# backplane.net
KiCad netlist of a schematic drawn in EAGLE
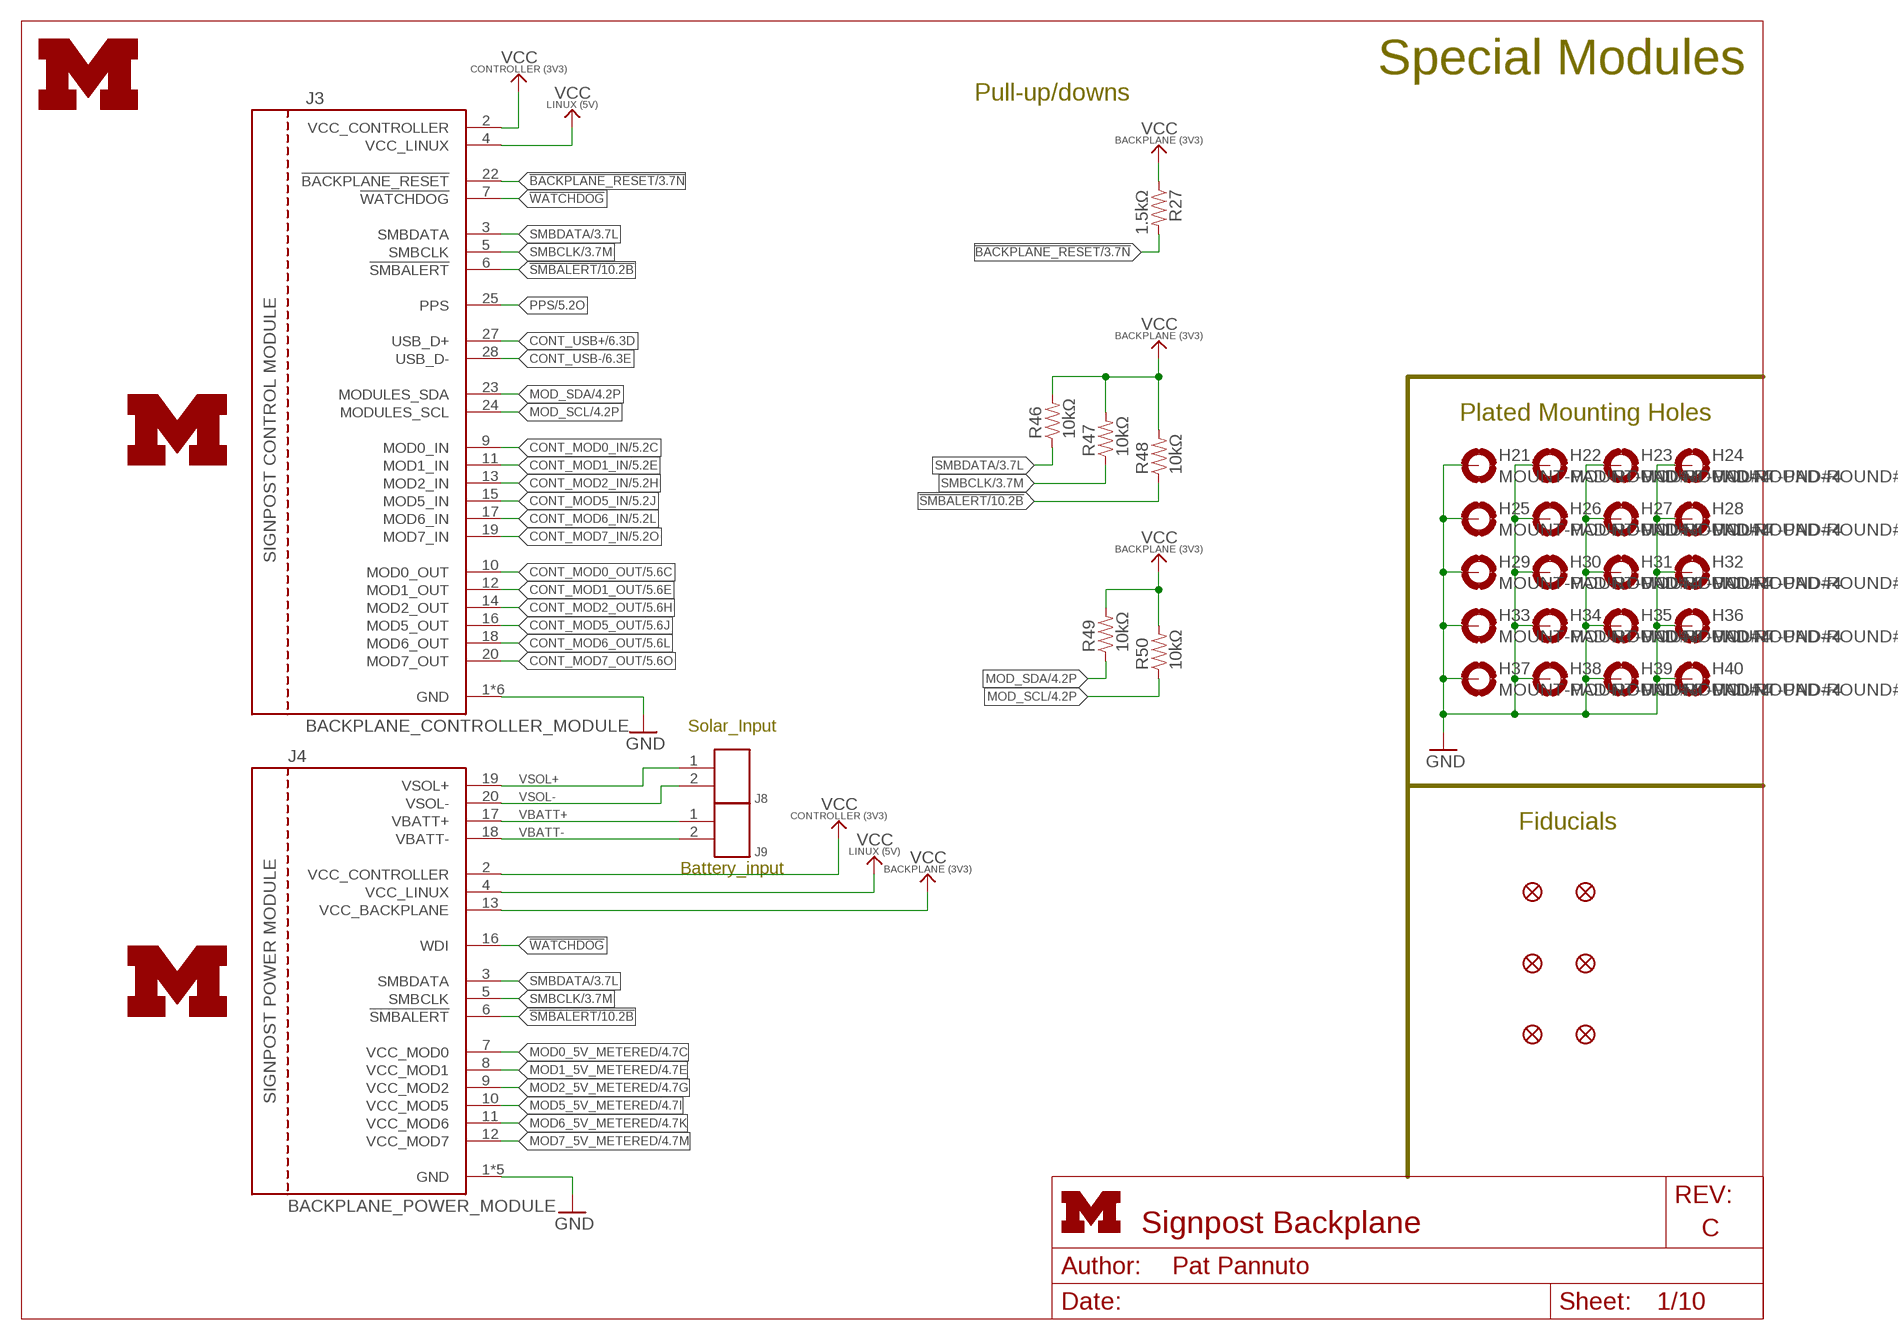
[diagram p0: schematic, sheet 1]
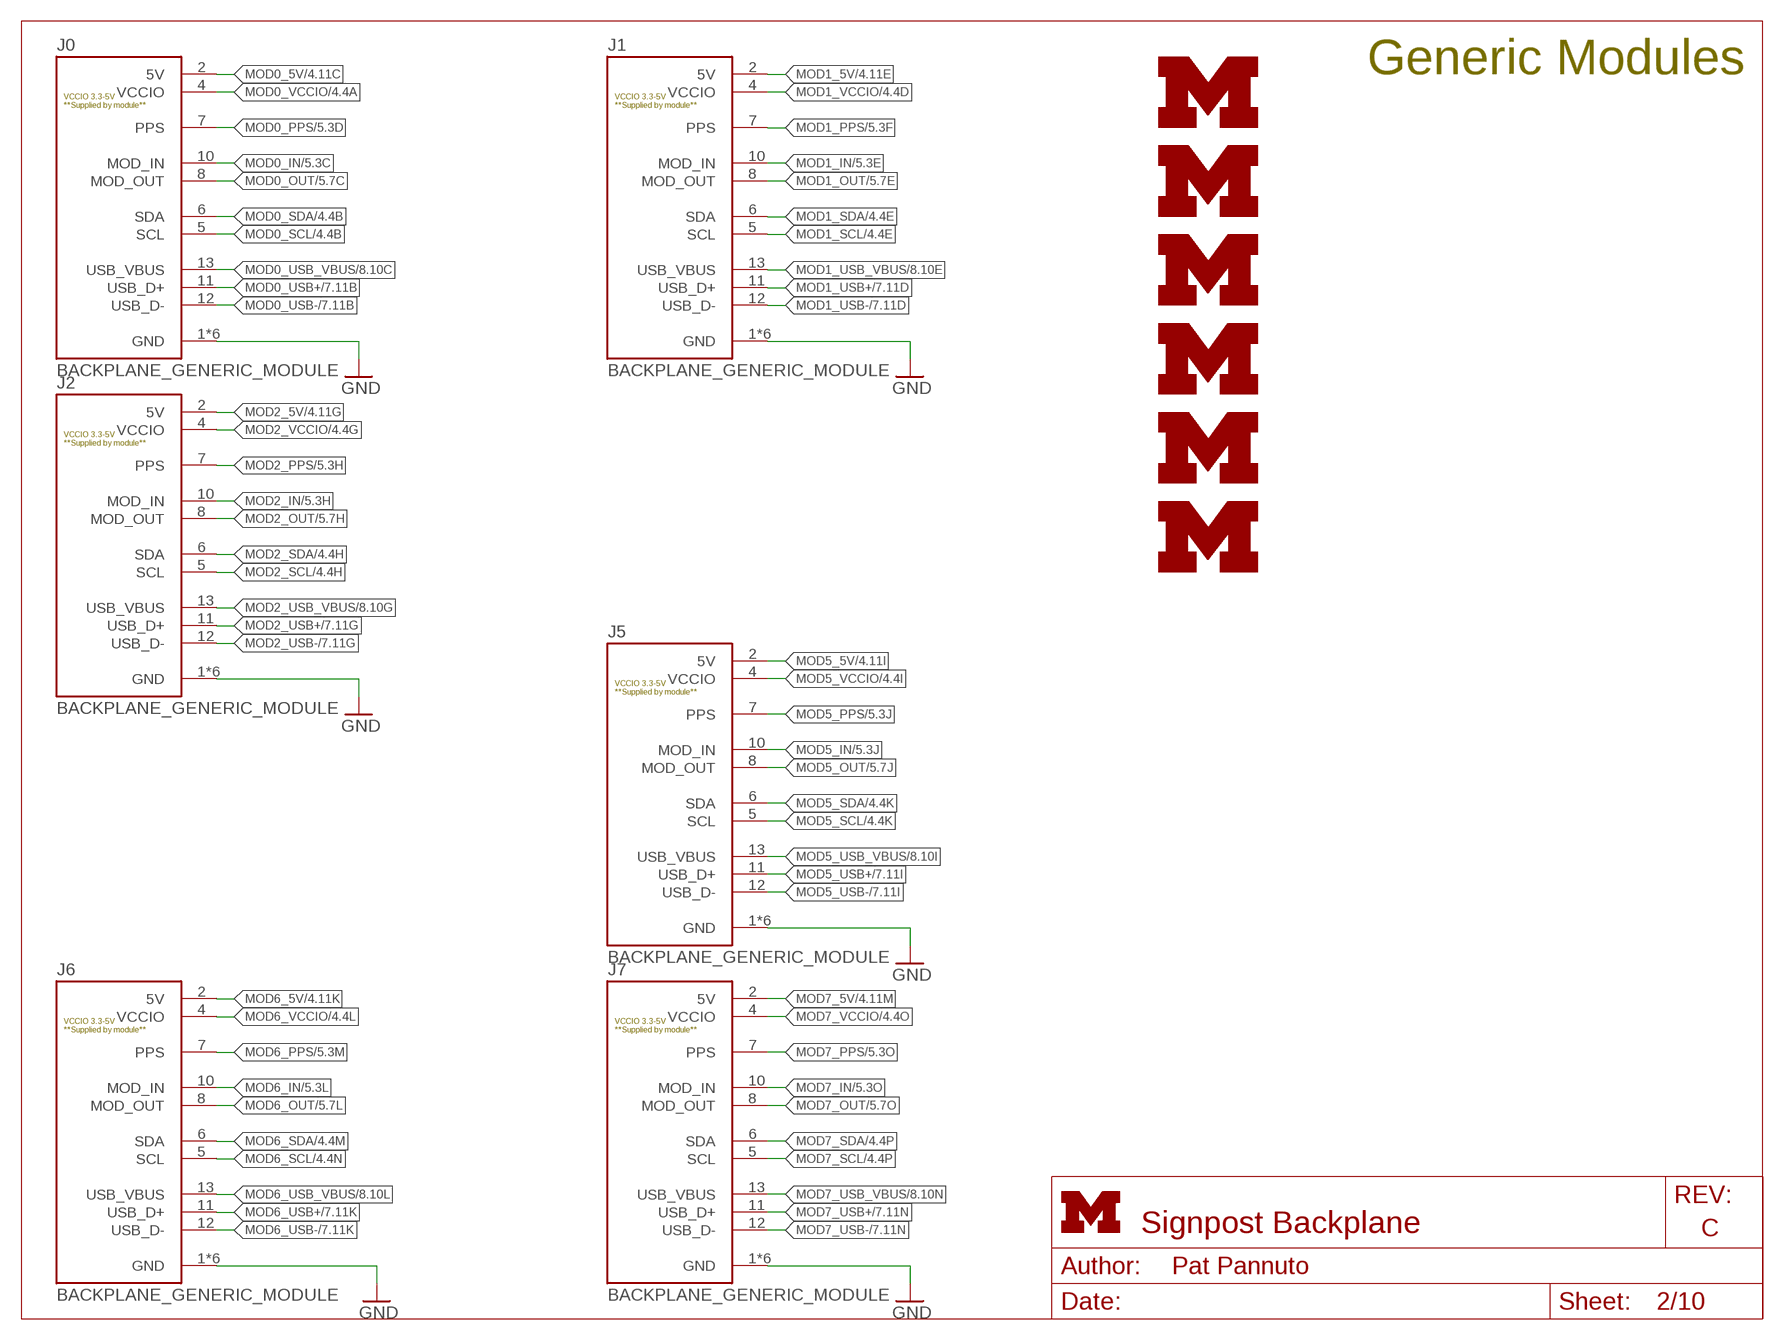
[diagram p1: schematic, sheet 2]
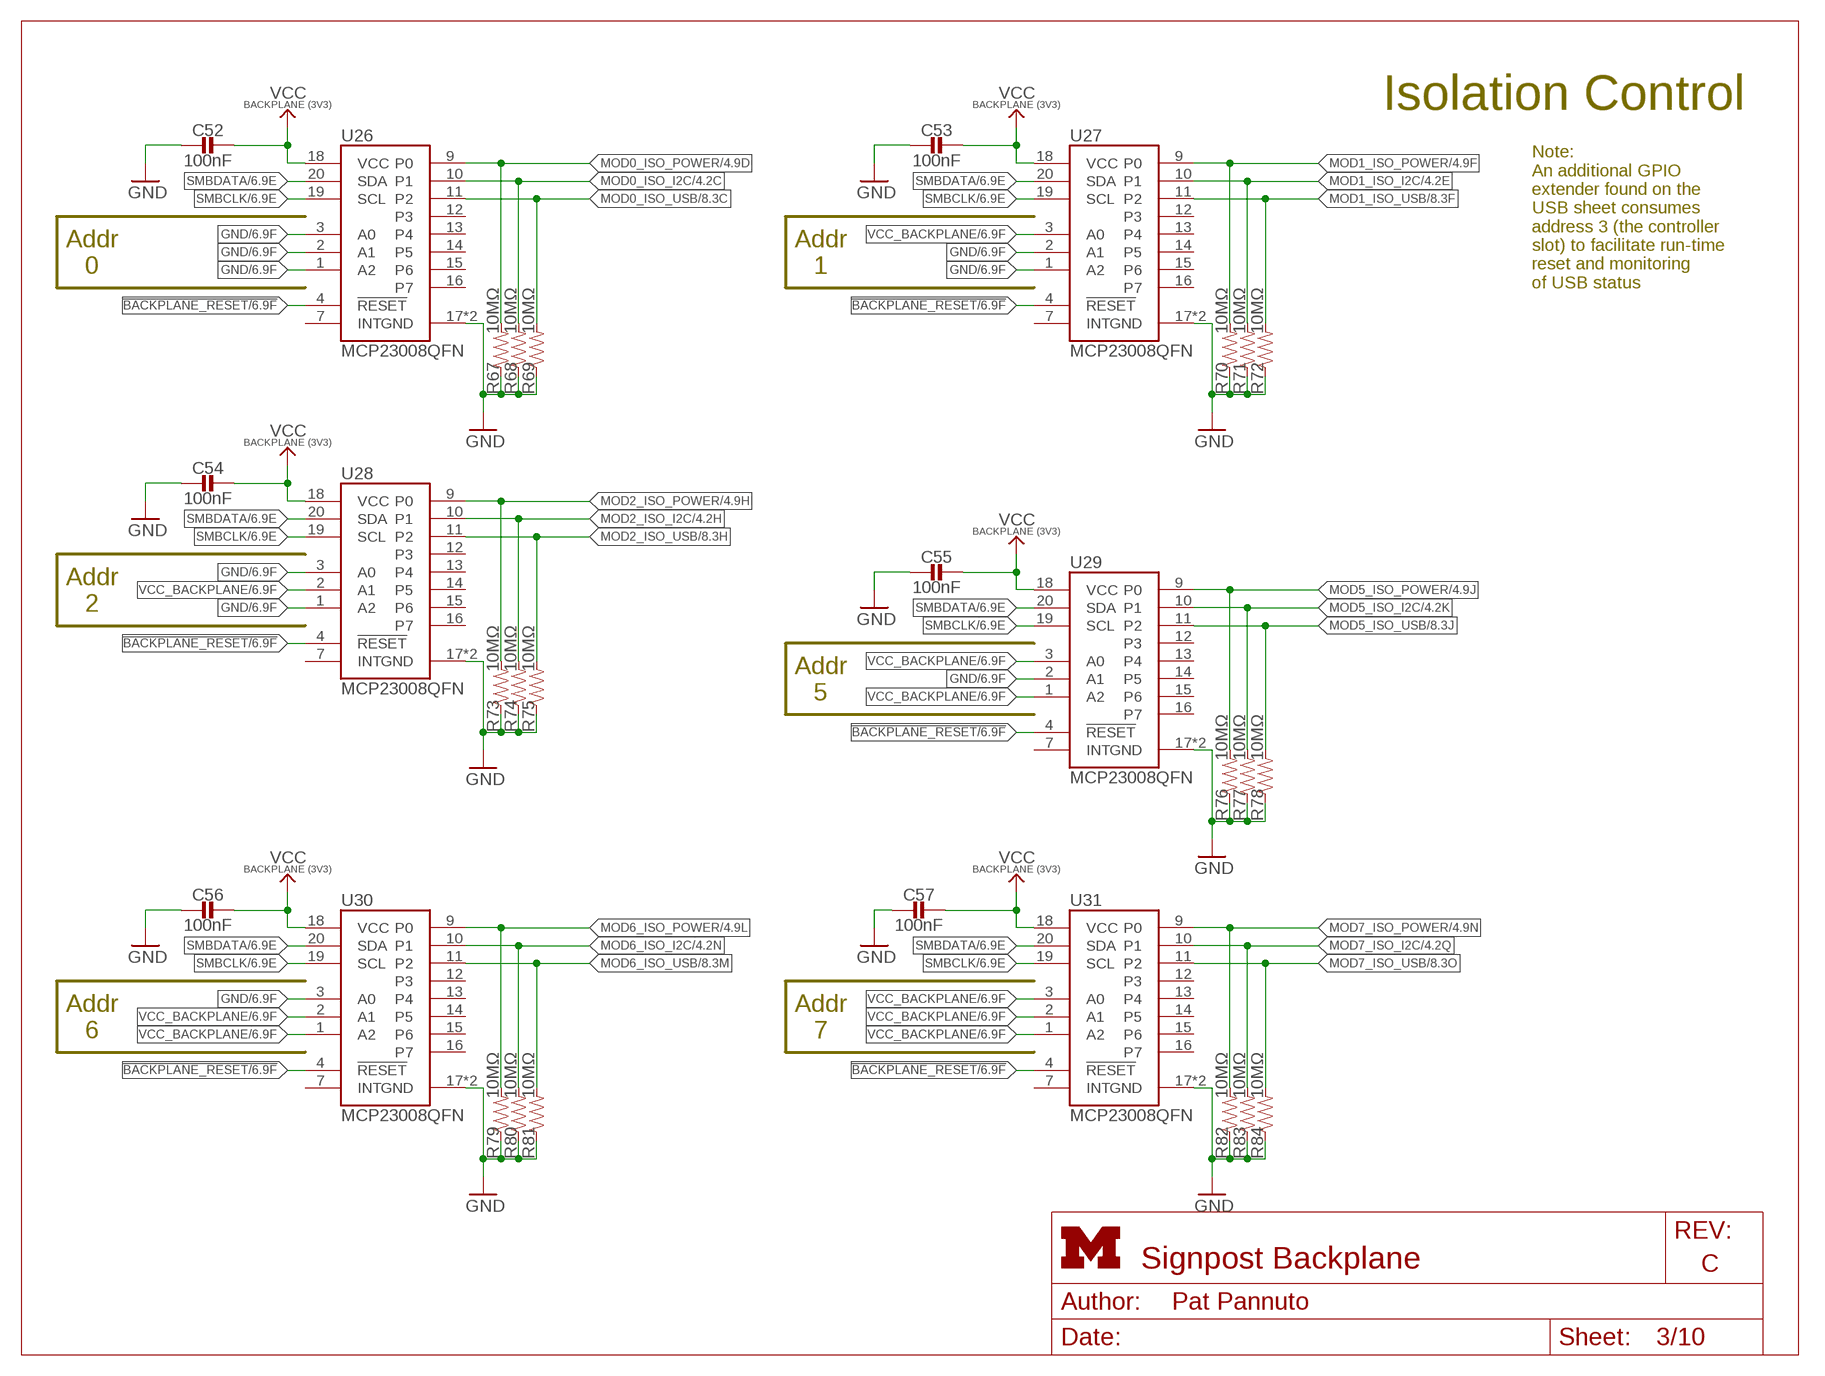
[diagram p2: schematic, sheet 3]
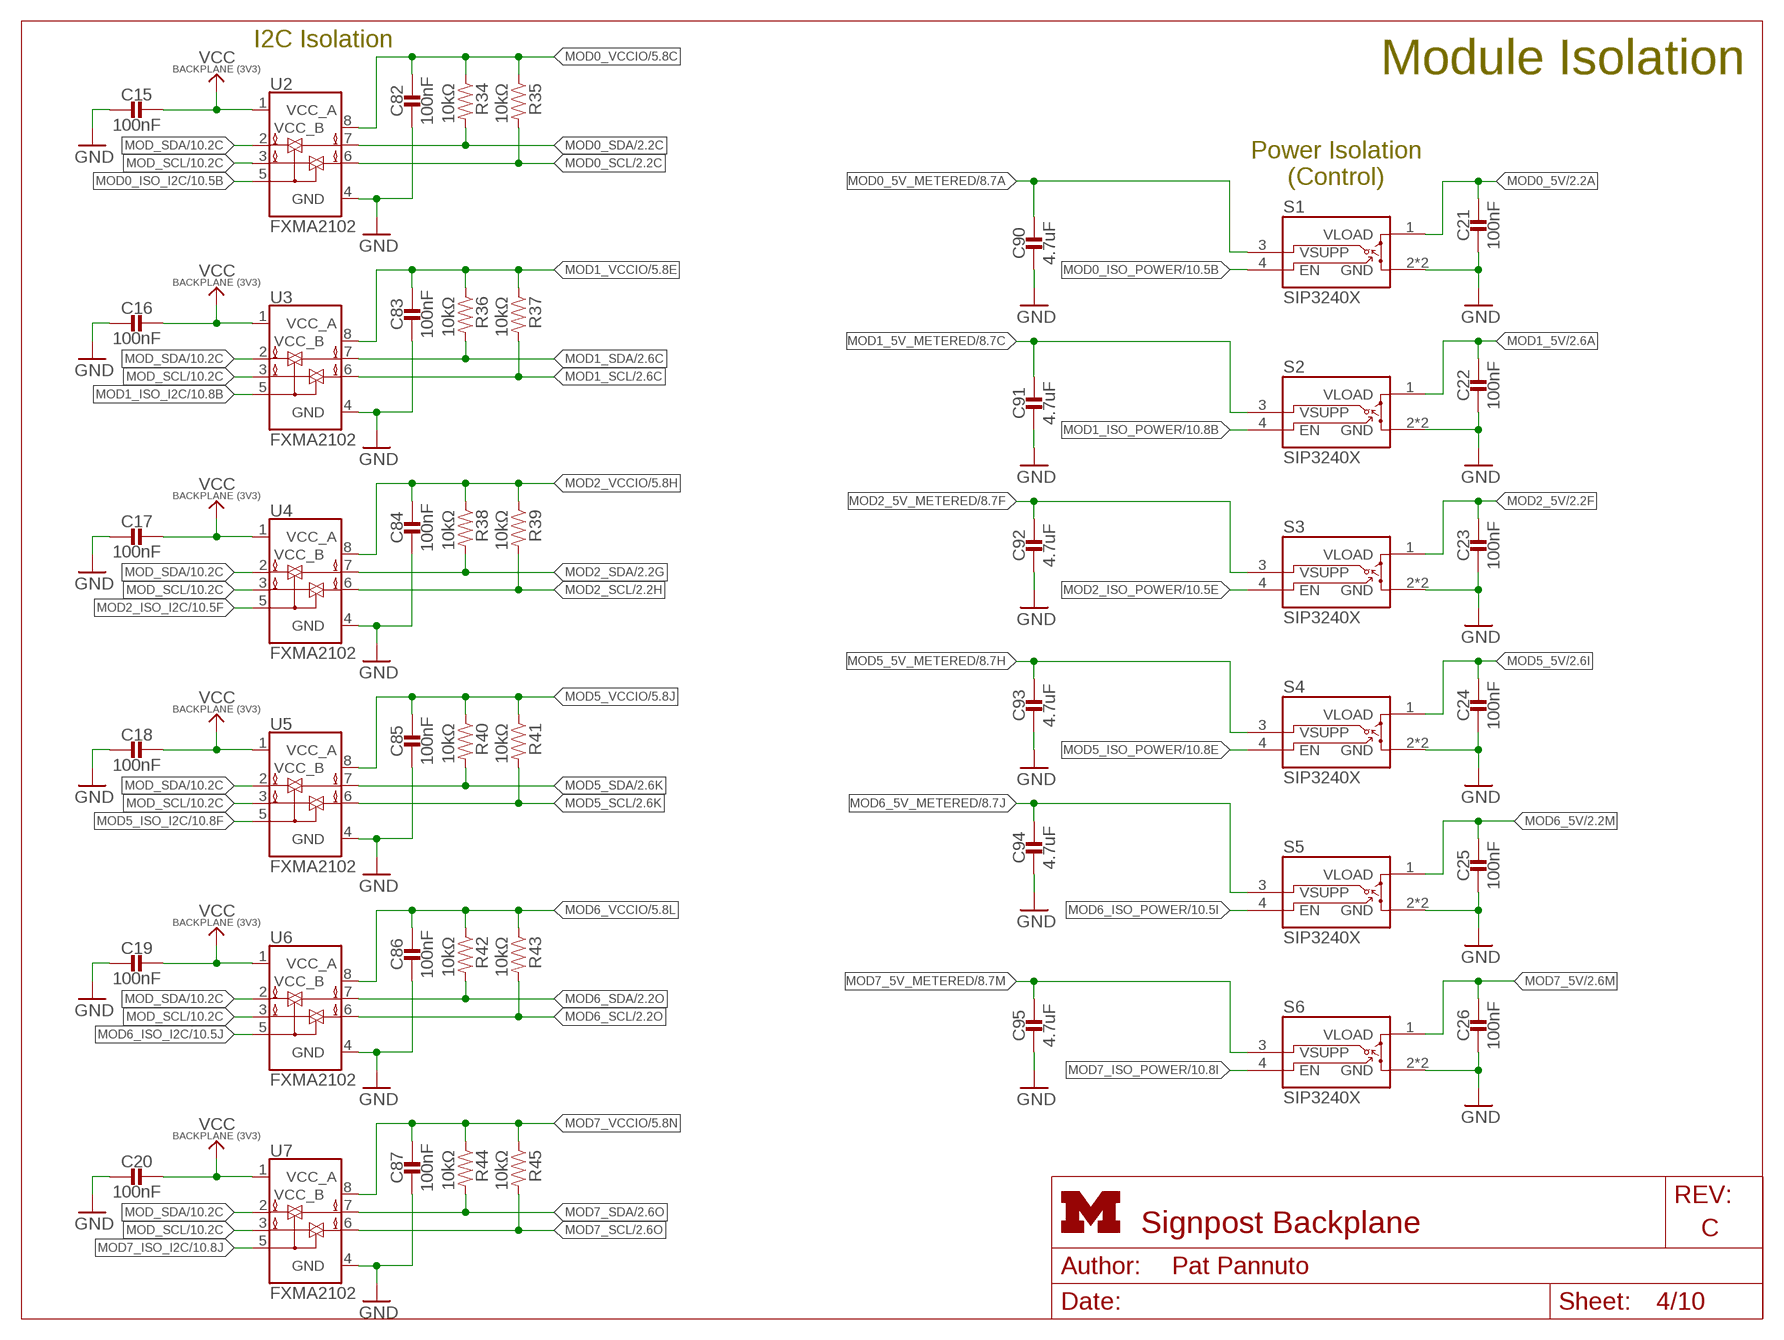
[diagram p3: schematic, sheet 4]
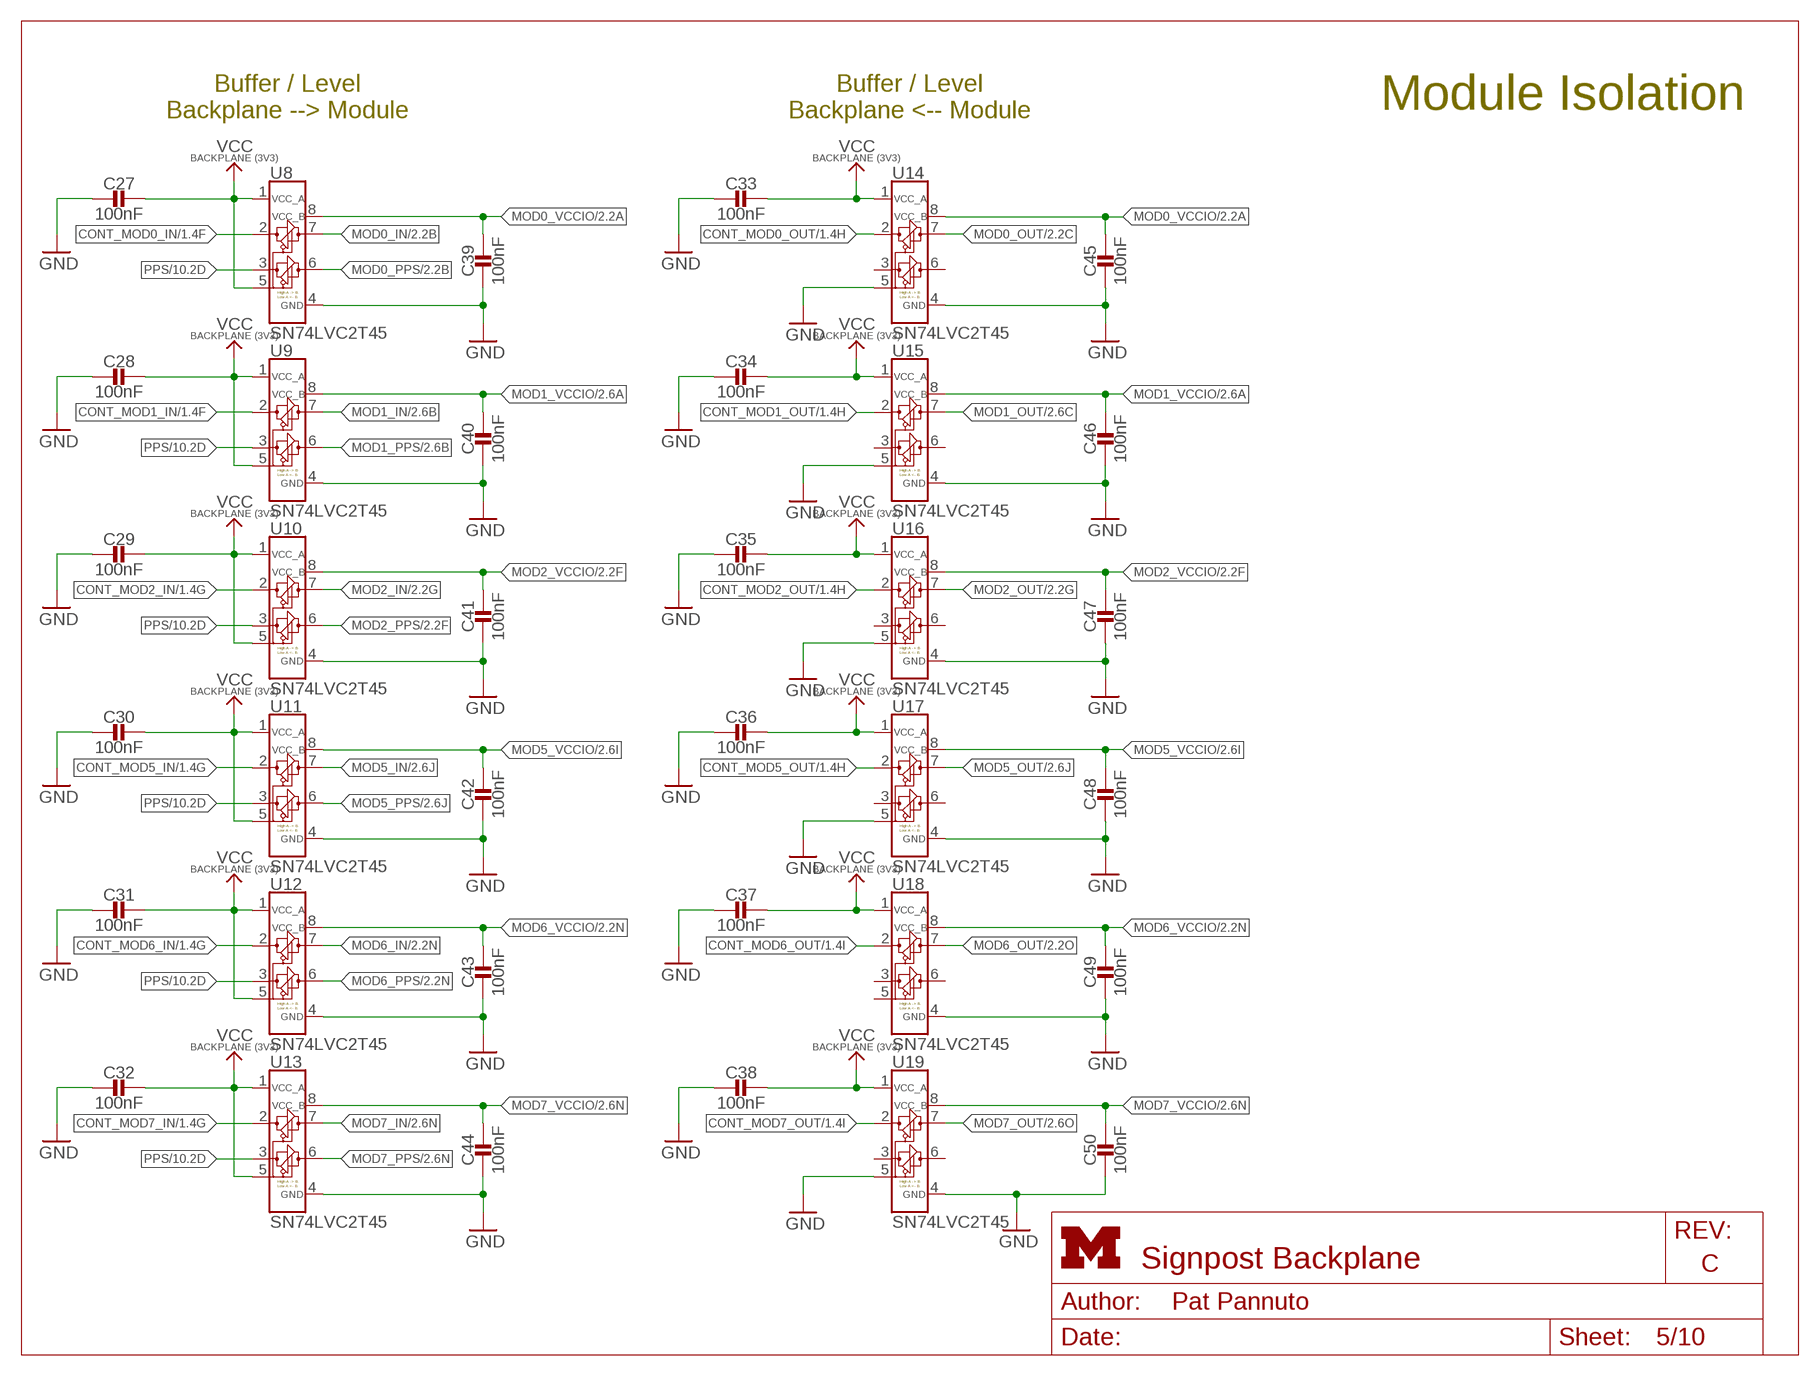
[diagram p4: schematic, sheet 5]
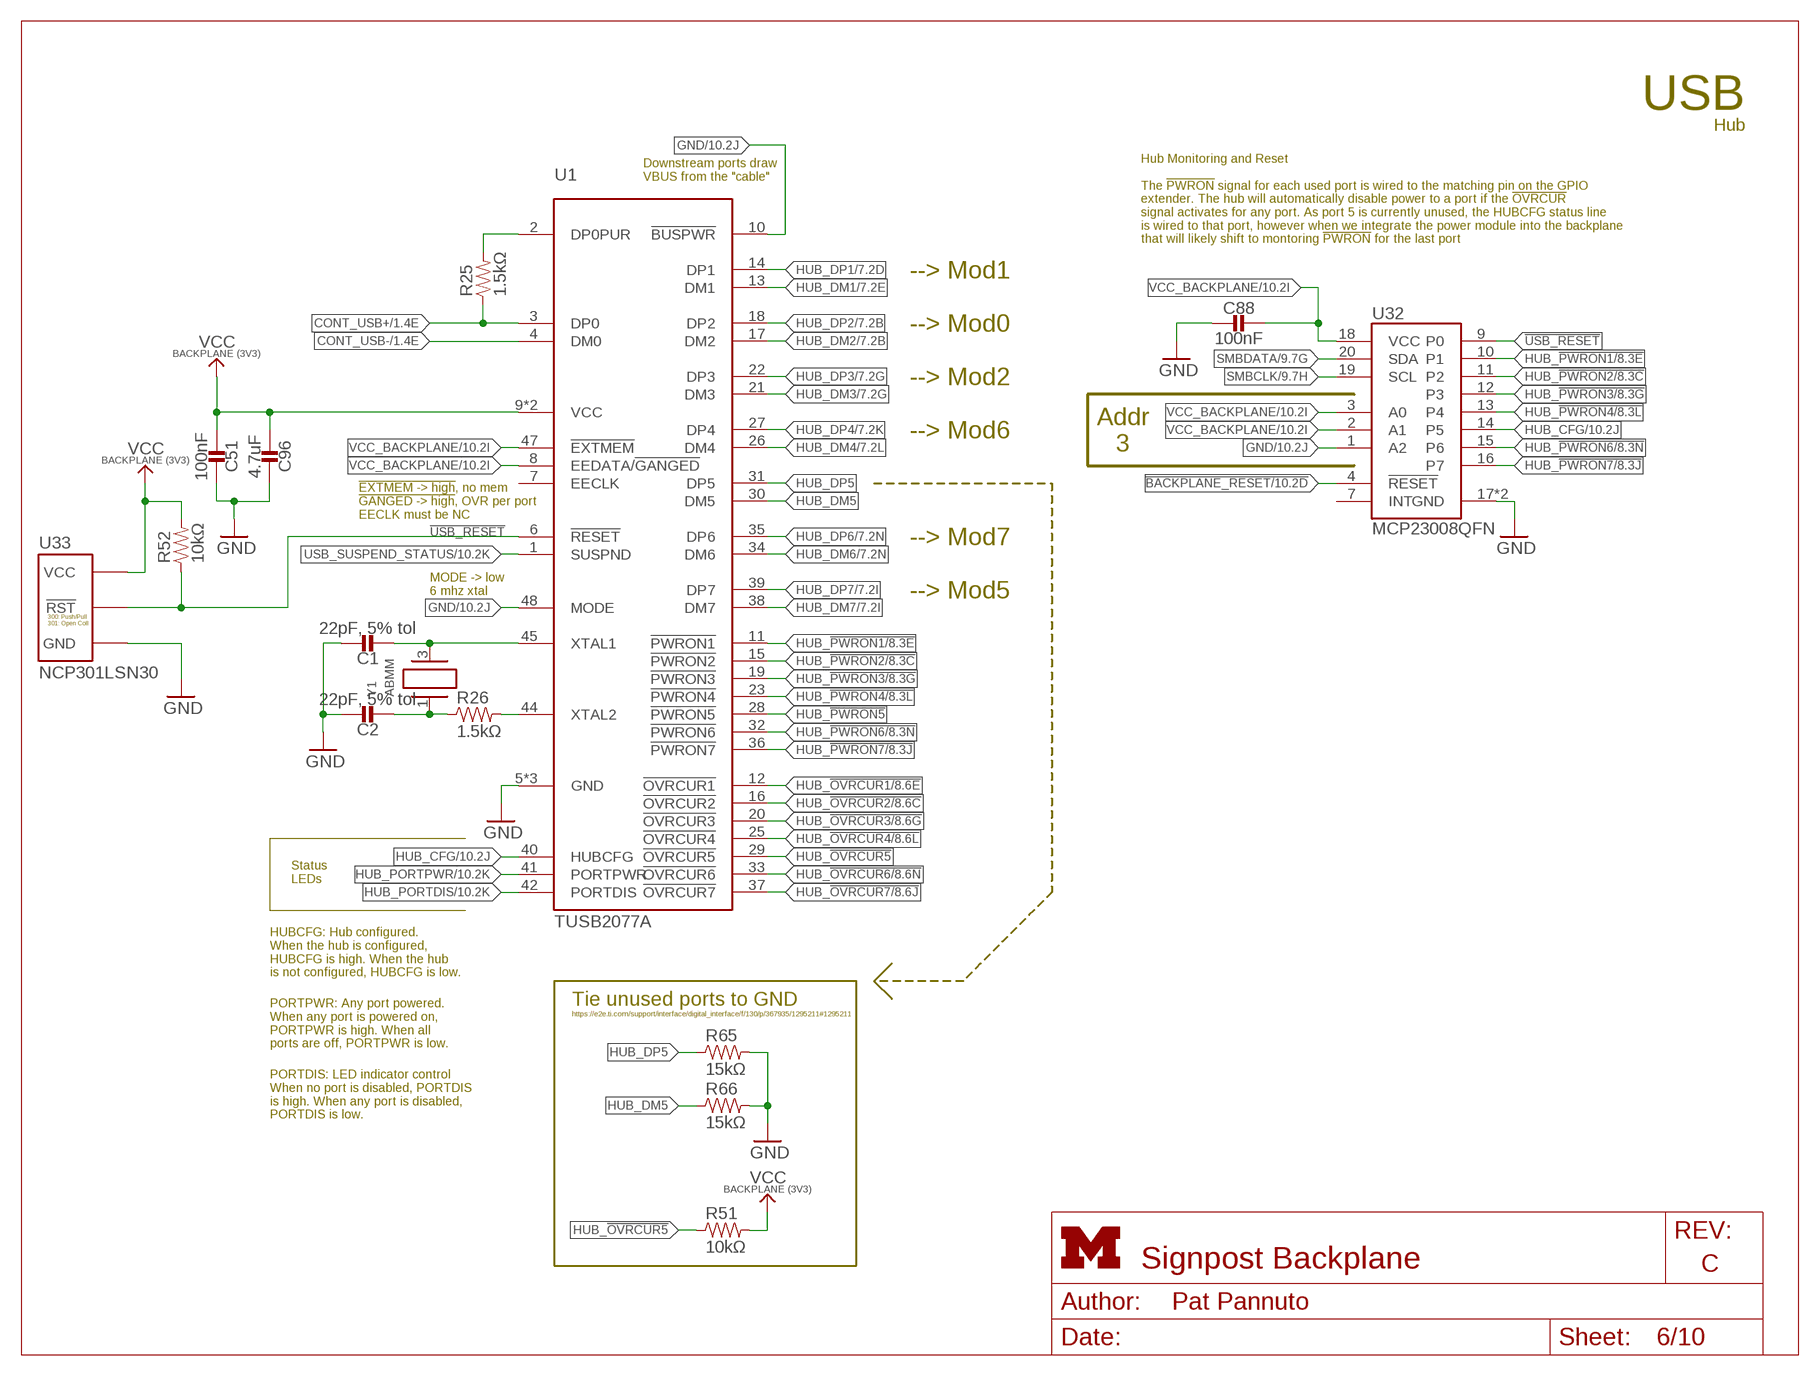
[diagram p5: schematic, sheet 6]
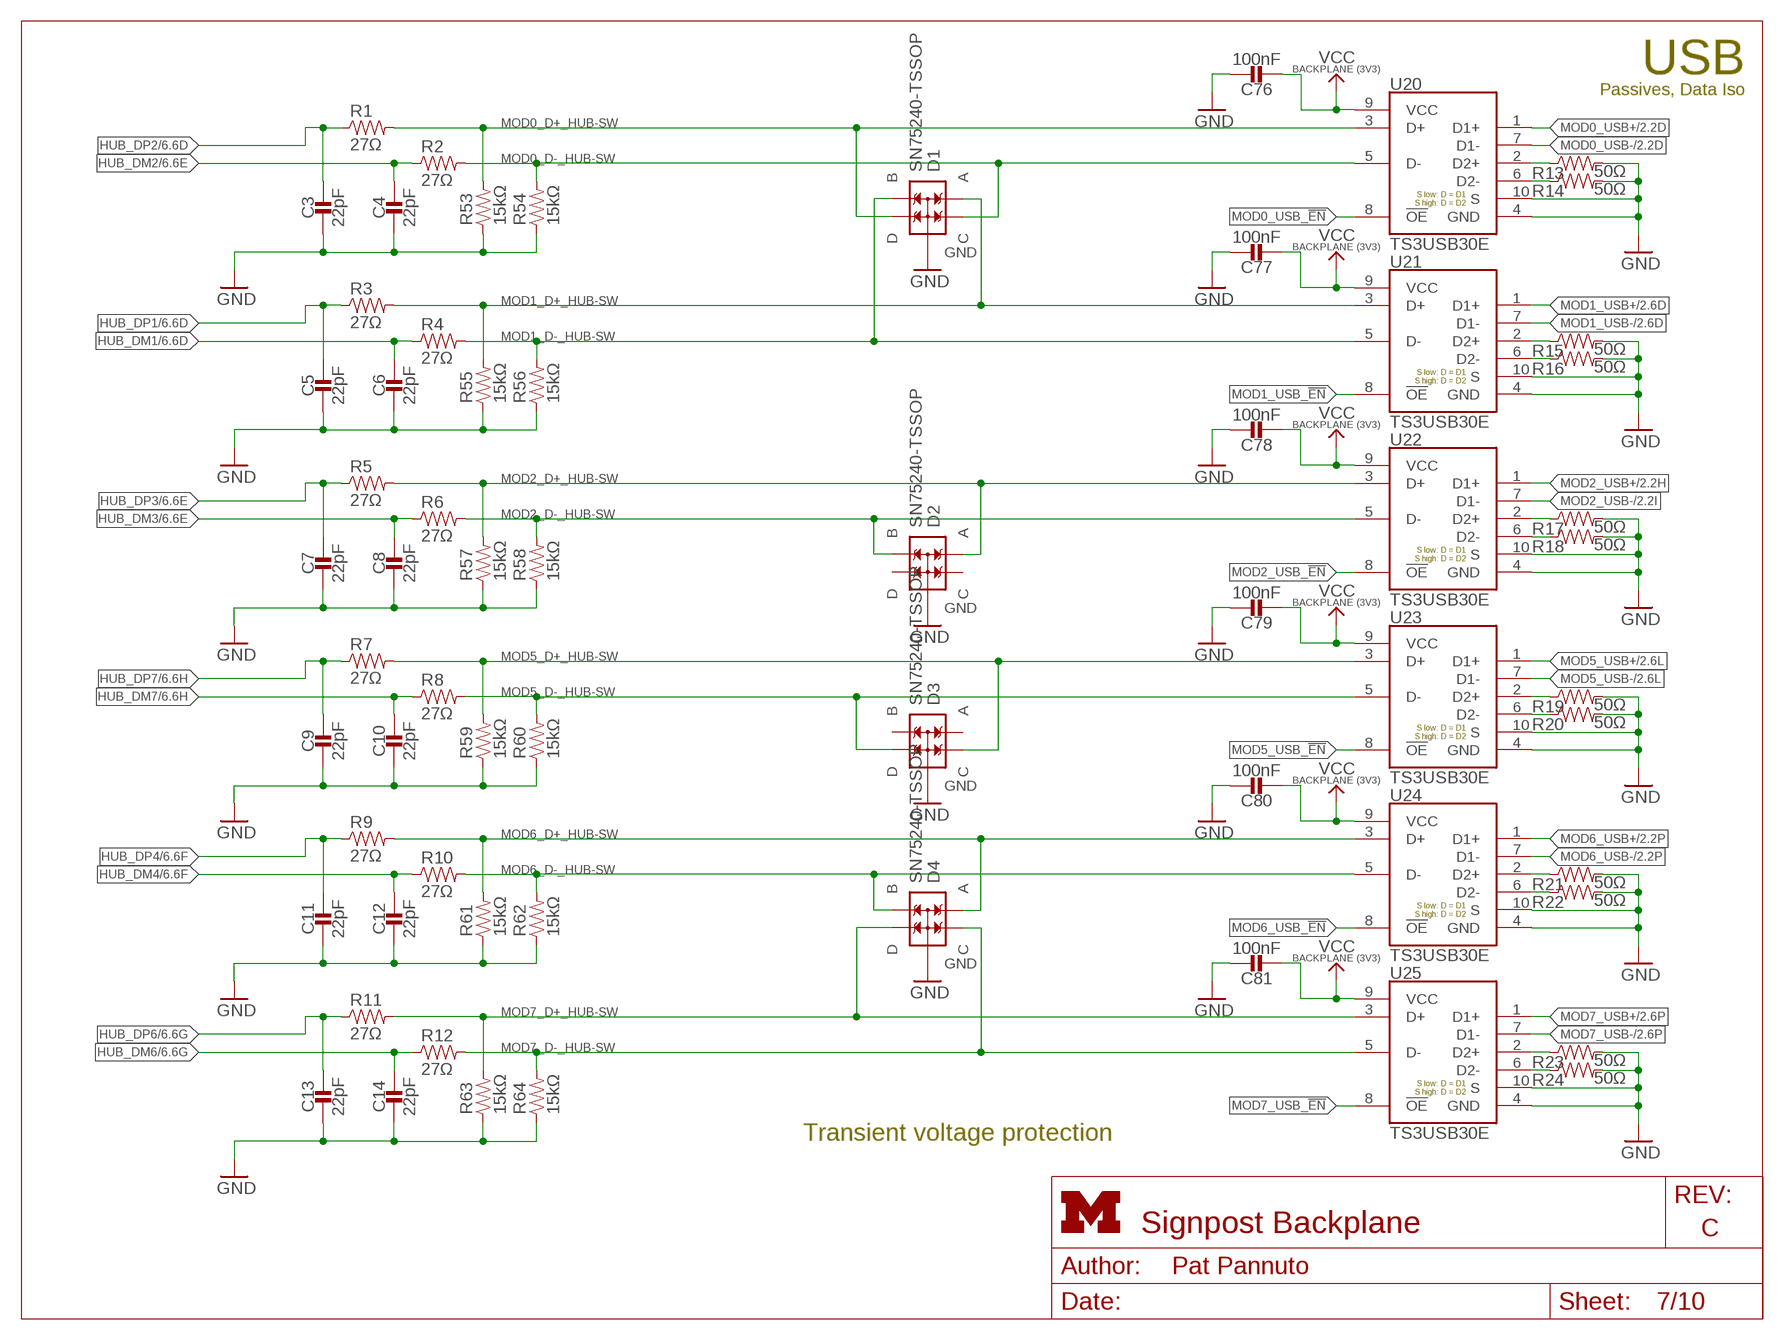
[diagram p6: schematic, sheet 7]
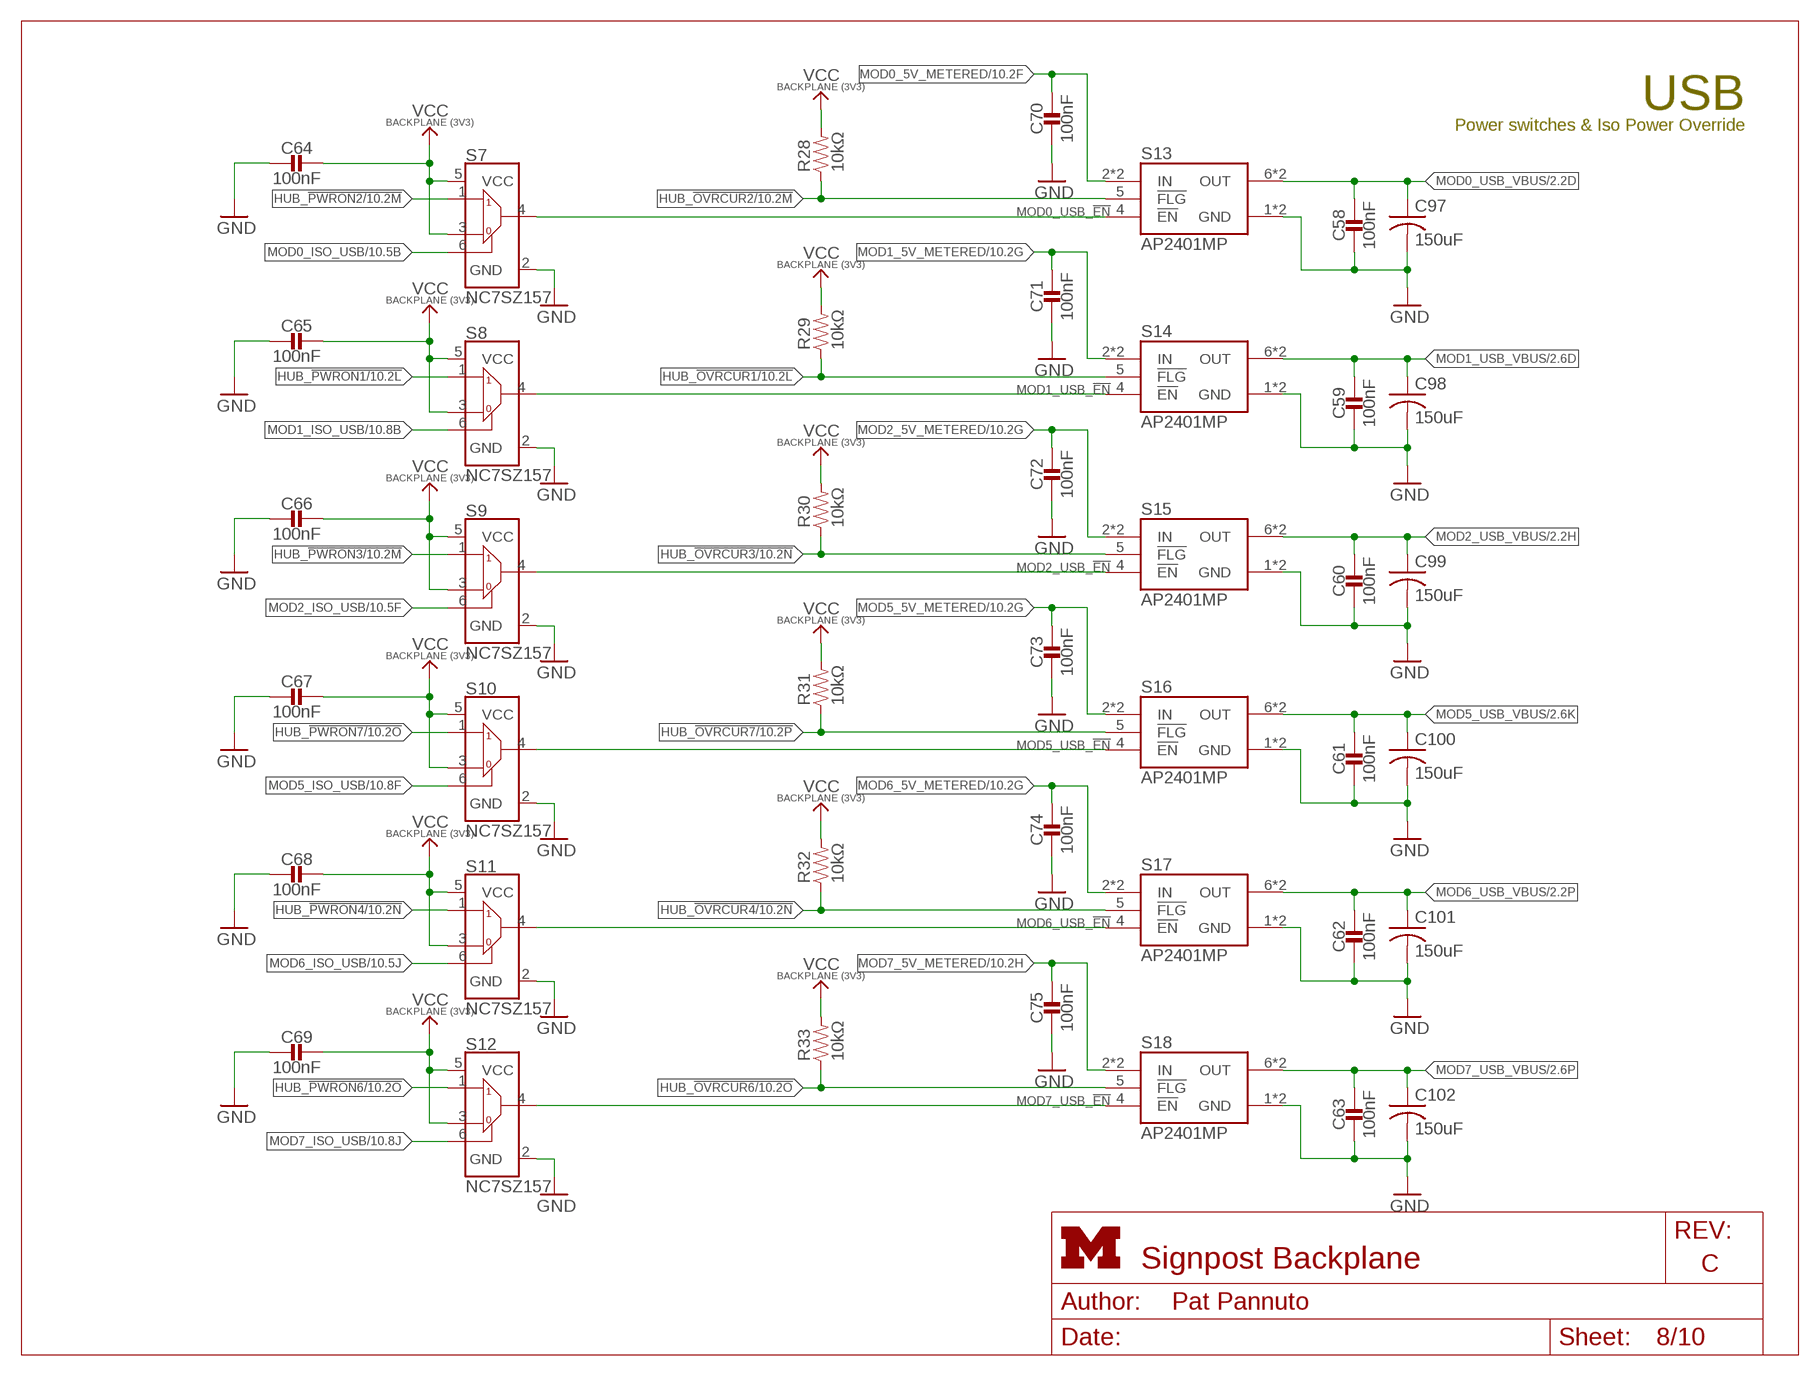
[diagram p7: schematic, sheet 8]
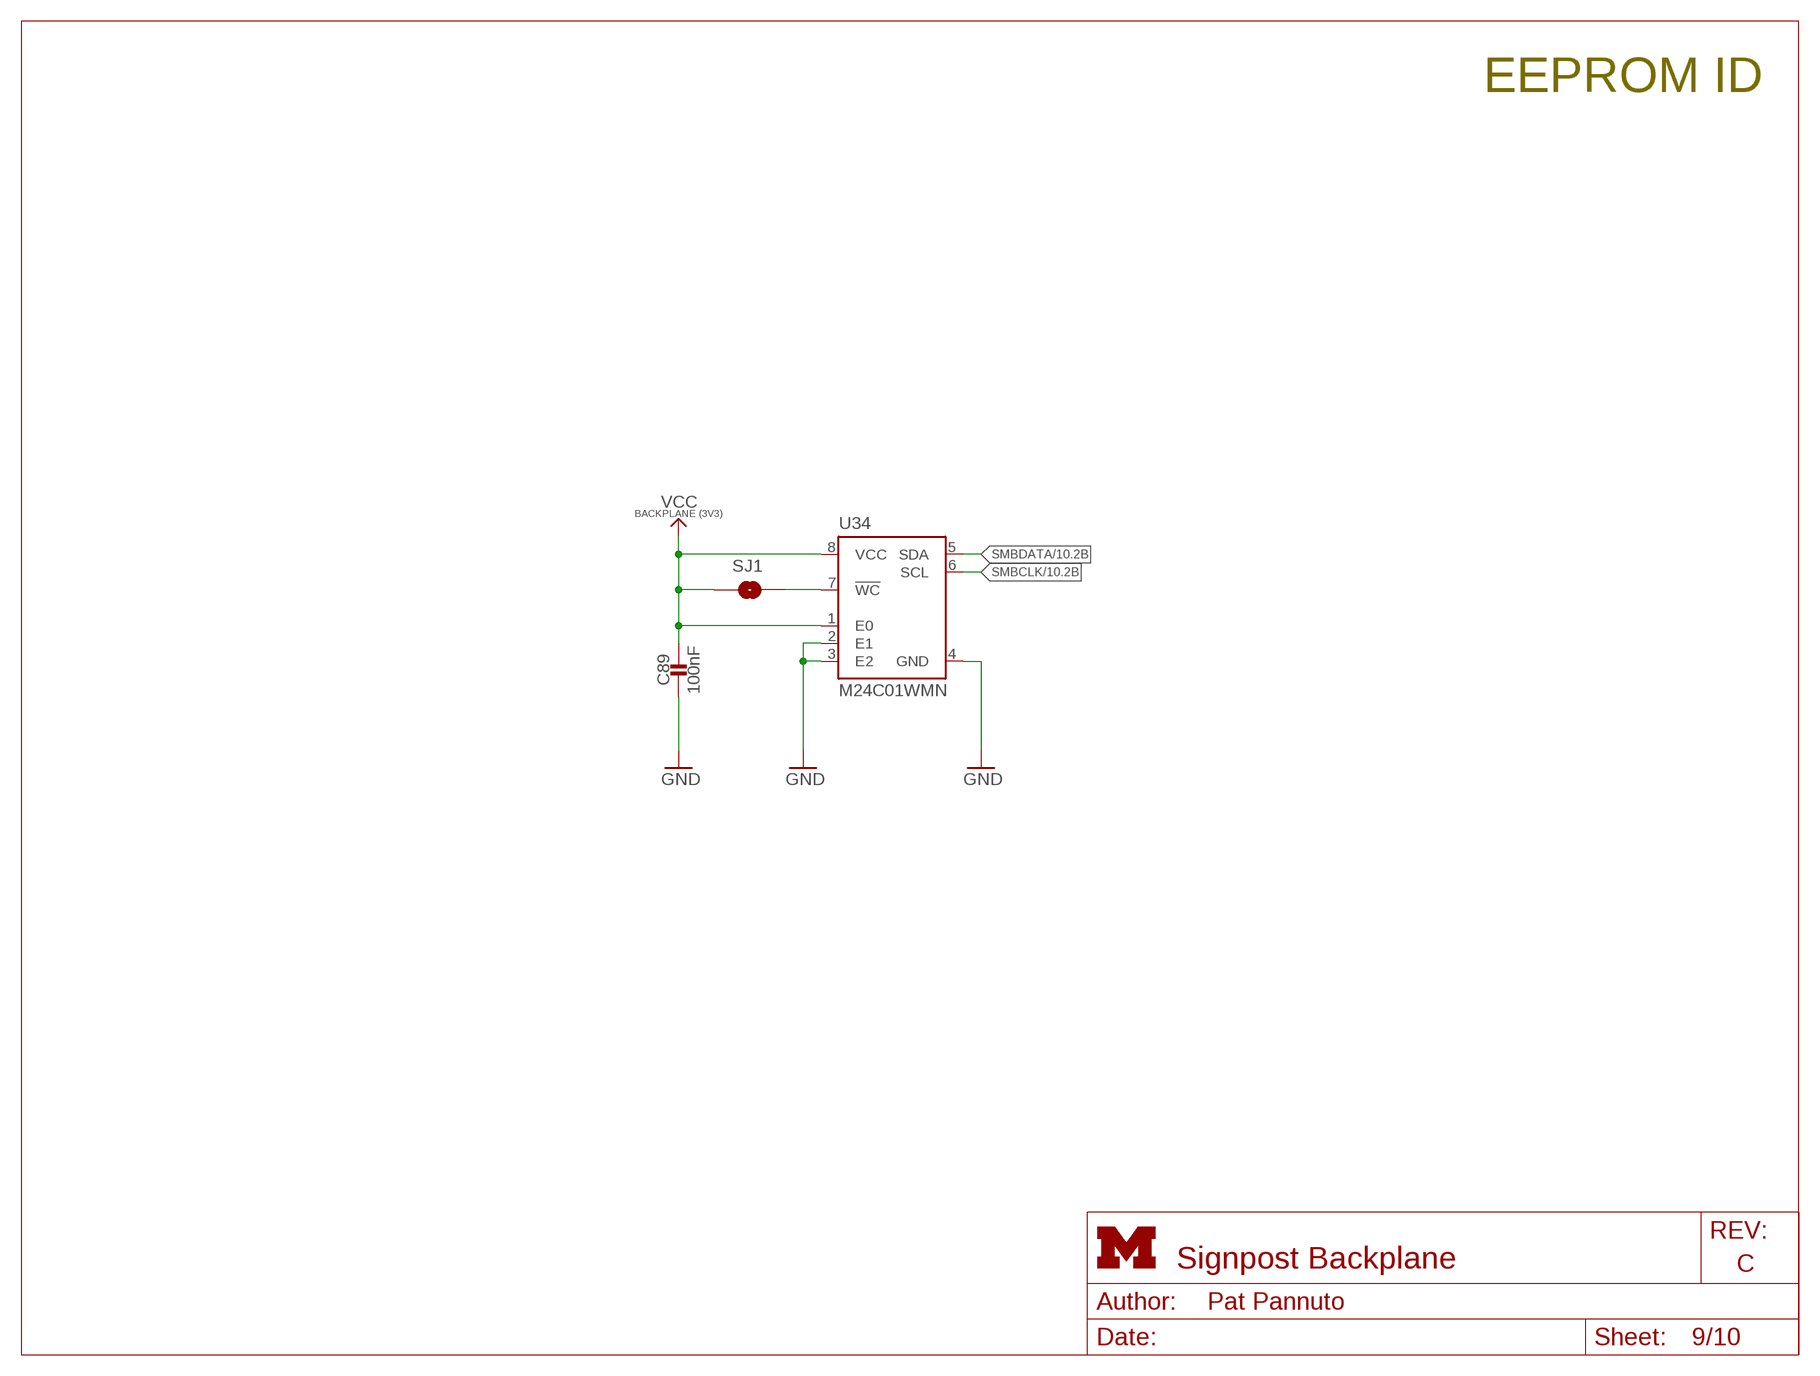
[diagram p8: schematic, sheet 9]
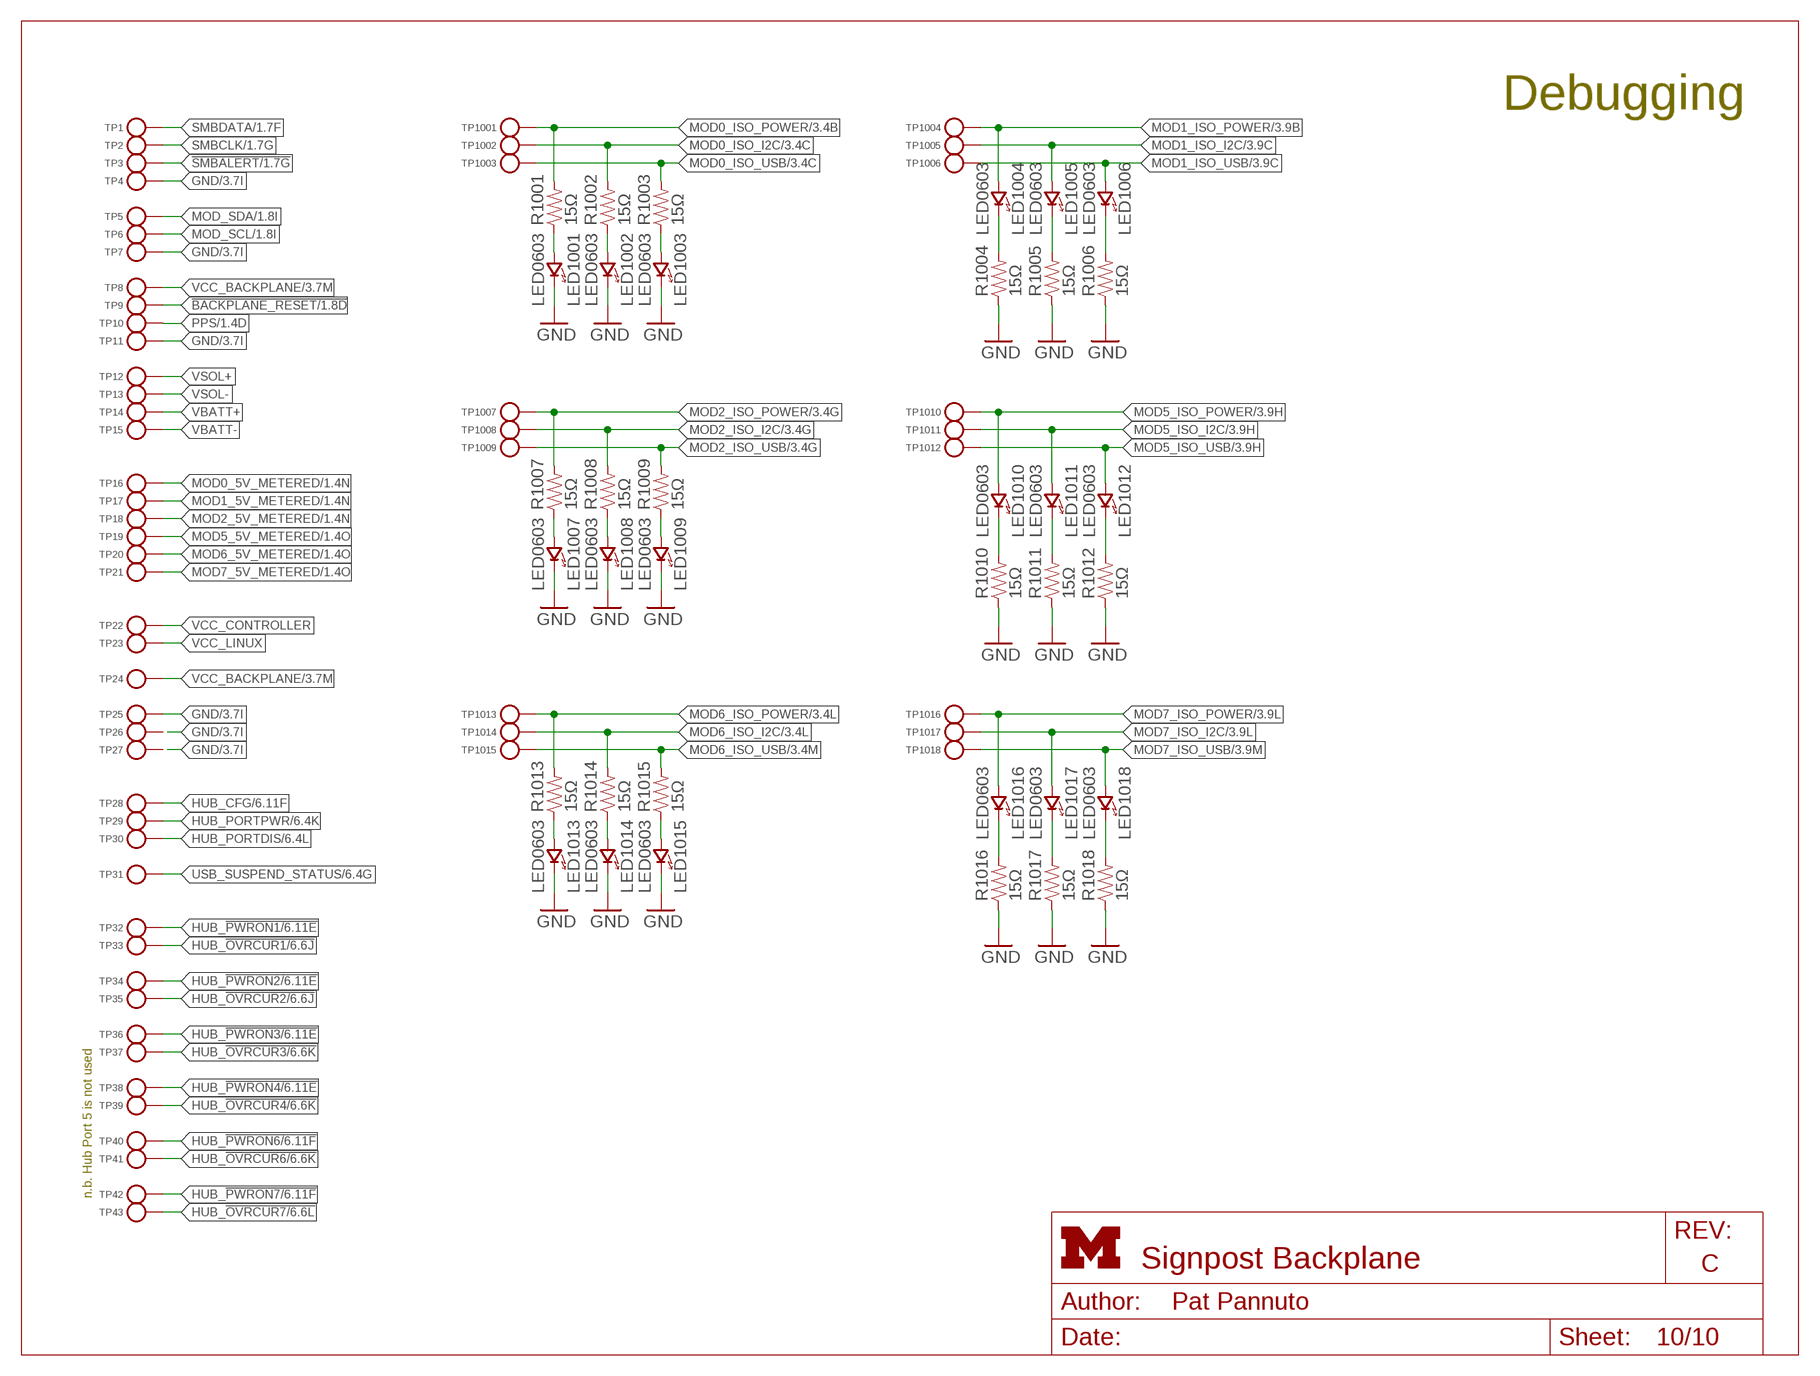
[diagram p9: schematic, sheet 10]

(export (version "E")
  (design (tool "Eeschema 10.0.6"))
  (components
    (comp (ref "C58")
      (value "100nF")
      (footprint "eagle-import:0603_CAP")
      (libsource (lib "eagle-import") (part "CAPACITOR0603_CAP"))
    )
    (comp (ref "C59")
      (value "100nF")
      (footprint "eagle-import:0603_CAP")
      (libsource (lib "eagle-import") (part "CAPACITOR0603_CAP"))
    )
    (comp (ref "C60")
      (value "100nF")
      (footprint "eagle-import:0603_CAP")
      (libsource (lib "eagle-import") (part "CAPACITOR0603_CAP"))
    )
    (comp (ref "C61")
      (value "100nF")
      (footprint "eagle-import:0603_CAP")
      (libsource (lib "eagle-import") (part "CAPACITOR0603_CAP"))
    )
    (comp (ref "C62")
      (value "100nF")
      (footprint "eagle-import:0603_CAP")
      (libsource (lib "eagle-import") (part "CAPACITOR0603_CAP"))
    )
    (comp (ref "C63")
      (value "100nF")
      (footprint "eagle-import:0603_CAP")
      (libsource (lib "eagle-import") (part "CAPACITOR0603_CAP"))
    )
    (comp (ref "C64")
      (value "100nF")
      (footprint "eagle-import:0603_CAP")
      (libsource (lib "eagle-import") (part "CAPACITOR0603_CAP"))
    )
    (comp (ref "C65")
      (value "100nF")
      (footprint "eagle-import:0603_CAP")
      (libsource (lib "eagle-import") (part "CAPACITOR0603_CAP"))
    )
    (comp (ref "C66")
      (value "100nF")
      (footprint "eagle-import:0603_CAP")
      (libsource (lib "eagle-import") (part "CAPACITOR0603_CAP"))
    )
    (comp (ref "C67")
      (value "100nF")
      (footprint "eagle-import:0603_CAP")
      (libsource (lib "eagle-import") (part "CAPACITOR0603_CAP"))
    )
    (comp (ref "C68")
      (value "100nF")
      (footprint "eagle-import:0603_CAP")
      (libsource (lib "eagle-import") (part "CAPACITOR0603_CAP"))
    )
    (comp (ref "C69")
      (value "100nF")
      (footprint "eagle-import:0603_CAP")
      (libsource (lib "eagle-import") (part "CAPACITOR0603_CAP"))
    )
    (comp (ref "C70")
      (value "100nF")
      (footprint "eagle-import:0603_CAP")
      (libsource (lib "eagle-import") (part "CAPACITOR0603_CAP"))
    )
    (comp (ref "C71")
      (value "100nF")
      (footprint "eagle-import:0603_CAP")
      (libsource (lib "eagle-import") (part "CAPACITOR0603_CAP"))
    )
    (comp (ref "C72")
      (value "100nF")
      (footprint "eagle-import:0603_CAP")
      (libsource (lib "eagle-import") (part "CAPACITOR0603_CAP"))
    )
    (comp (ref "C73")
      (value "100nF")
      (footprint "eagle-import:0603_CAP")
      (libsource (lib "eagle-import") (part "CAPACITOR0603_CAP"))
    )
    (comp (ref "C74")
      (value "100nF")
      (footprint "eagle-import:0603_CAP")
      (libsource (lib "eagle-import") (part "CAPACITOR0603_CAP"))
    )
    (comp (ref "C75")
      (value "100nF")
      (footprint "eagle-import:0603_CAP")
      (libsource (lib "eagle-import") (part "CAPACITOR0603_CAP"))
    )
    (comp (ref "C97")
      (value "150uF")
      (footprint "eagle-import:C1206")
      (libsource (lib "eagle-import") (part "C-USC1206"))
    )
    (comp (ref "C98")
      (value "150uF")
      (footprint "eagle-import:C1206")
      (libsource (lib "eagle-import") (part "C-USC1206"))
    )
    (comp (ref "C99")
      (value "150uF")
      (footprint "eagle-import:C1206")
      (libsource (lib "eagle-import") (part "C-USC1206"))
    )
    (comp (ref "C100")
      (value "150uF")
      (footprint "eagle-import:C1206")
      (libsource (lib "eagle-import") (part "C-USC1206"))
    )
    (comp (ref "C101")
      (value "150uF")
      (footprint "eagle-import:C1206")
      (libsource (lib "eagle-import") (part "C-USC1206"))
    )
    (comp (ref "C102")
      (value "150uF")
      (footprint "eagle-import:C1206")
      (libsource (lib "eagle-import") (part "C-USC1206"))
    )
    (comp (ref "R28")
      (value "10kΩ")
      (footprint "eagle-import:0603-RES")
      (libsource (lib "eagle-import") (part "RESISTOR0603_RES"))
    )
    (comp (ref "R29")
      (value "10kΩ")
      (footprint "eagle-import:0603-RES")
      (libsource (lib "eagle-import") (part "RESISTOR0603_RES"))
    )
    (comp (ref "R30")
      (value "10kΩ")
      (footprint "eagle-import:0603-RES")
      (libsource (lib "eagle-import") (part "RESISTOR0603_RES"))
    )
    (comp (ref "R31")
      (value "10kΩ")
      (footprint "eagle-import:0603-RES")
      (libsource (lib "eagle-import") (part "RESISTOR0603_RES"))
    )
    (comp (ref "R32")
      (value "10kΩ")
      (footprint "eagle-import:0603-RES")
      (libsource (lib "eagle-import") (part "RESISTOR0603_RES"))
    )
    (comp (ref "R33")
      (value "10kΩ")
      (footprint "eagle-import:0603-RES")
      (libsource (lib "eagle-import") (part "RESISTOR0603_RES"))
    )
    (comp (ref "S7")
      (value "NC7SZ157")
      (footprint "eagle-import:SC70-6")
      (libsource (lib "eagle-import") (part "NC7SZ157"))
    )
    (comp (ref "S8")
      (value "NC7SZ157")
      (footprint "eagle-import:SC70-6")
      (libsource (lib "eagle-import") (part "NC7SZ157"))
    )
    (comp (ref "S9")
      (value "NC7SZ157")
      (footprint "eagle-import:SC70-6")
      (libsource (lib "eagle-import") (part "NC7SZ157"))
    )
    (comp (ref "S10")
      (value "NC7SZ157")
      (footprint "eagle-import:SC70-6")
      (libsource (lib "eagle-import") (part "NC7SZ157"))
    )
    (comp (ref "S11")
      (value "NC7SZ157")
      (footprint "eagle-import:SC70-6")
      (libsource (lib "eagle-import") (part "NC7SZ157"))
    )
    (comp (ref "S12")
      (value "NC7SZ157")
      (footprint "eagle-import:SC70-6")
      (libsource (lib "eagle-import") (part "NC7SZ157"))
    )
    (comp (ref "S13")
      (value "AP2401MP")
      (footprint "eagle-import:MSOP-8EP")
      (libsource (lib "eagle-import") (part "AP2401MP"))
    )
    (comp (ref "S14")
      (value "AP2401MP")
      (footprint "eagle-import:MSOP-8EP")
      (libsource (lib "eagle-import") (part "AP2401MP"))
    )
    (comp (ref "S15")
      (value "AP2401MP")
      (footprint "eagle-import:MSOP-8EP")
      (libsource (lib "eagle-import") (part "AP2401MP"))
    )
    (comp (ref "S16")
      (value "AP2401MP")
      (footprint "eagle-import:MSOP-8EP")
      (libsource (lib "eagle-import") (part "AP2401MP"))
    )
    (comp (ref "S17")
      (value "AP2401MP")
      (footprint "eagle-import:MSOP-8EP")
      (libsource (lib "eagle-import") (part "AP2401MP"))
    )
    (comp (ref "S18")
      (value "AP2401MP")
      (footprint "eagle-import:MSOP-8EP")
      (libsource (lib "eagle-import") (part "AP2401MP"))
    )
    (comp (ref "C1")
      (value "22pF, 5% tol")
      (footprint "eagle-import:0603_CAP")
      (libsource (lib "eagle-import") (part "CAPACITOR0603_CAP"))
    )
    (comp (ref "C2")
      (value "22pF, 5% tol")
      (footprint "eagle-import:0603_CAP")
      (libsource (lib "eagle-import") (part "CAPACITOR0603_CAP"))
    )
    (comp (ref "C51")
      (value "100nF")
      (footprint "eagle-import:0603_CAP")
      (libsource (lib "eagle-import") (part "CAPACITOR0603_CAP"))
    )
    (comp (ref "C88")
      (value "100nF")
      (footprint "eagle-import:0603_CAP")
      (libsource (lib "eagle-import") (part "CAPACITOR0603_CAP"))
    )
    (comp (ref "C96")
      (value "4.7uF")
      (footprint "eagle-import:0603_CAP")
      (libsource (lib "eagle-import") (part "CAPACITOR0603_CAP"))
    )
    (comp (ref "R25")
      (value "1.5kΩ")
      (footprint "eagle-import:0603-RES")
      (libsource (lib "eagle-import") (part "RESISTOR0603_RES"))
    )
    (comp (ref "R26")
      (value "1.5kΩ")
      (footprint "eagle-import:0603-RES")
      (libsource (lib "eagle-import") (part "RESISTOR0603_RES"))
    )
    (comp (ref "R51")
      (value "10kΩ")
      (footprint "eagle-import:0603-RES")
      (libsource (lib "eagle-import") (part "RESISTOR0603_RES"))
    )
    (comp (ref "R52")
      (value "10kΩ")
      (footprint "eagle-import:0603-RES")
      (libsource (lib "eagle-import") (part "RESISTOR0603_RES"))
    )
    (comp (ref "R65")
      (value "15kΩ")
      (footprint "eagle-import:0603-RES")
      (libsource (lib "eagle-import") (part "RESISTOR0603_RES"))
    )
    (comp (ref "R66")
      (value "15kΩ")
      (footprint "eagle-import:0603-RES")
      (libsource (lib "eagle-import") (part "RESISTOR0603_RES"))
    )
    (comp (ref "U1")
      (value "TUSB2077A")
      (footprint "eagle-import:LQFP-48")
      (libsource (lib "eagle-import") (part "TUSB2077A"))
    )
    (comp (ref "U32")
      (value "MCP23008QFN")
      (footprint "eagle-import:QFN-20-4MM")
      (libsource (lib "eagle-import") (part "MCP23008QFN"))
    )
    (comp (ref "U33")
      (value "NCP301LSN30")
      (footprint "eagle-import:SOT23-5")
      (libsource (lib "eagle-import") (part "NCP301LSN30"))
    )
    (comp (ref "Y1")
      (value "ABMM")
      (footprint "eagle-import:ABMM")
      (libsource (lib "eagle-import") (part "ABMM"))
    )
    (comp (ref "H21")
      (value "MOUNT-PAD-ROUND#4")
      (footprint "eagle-import:#4-PAD")
      (libsource (lib "eagle-import") (part "MOUNT-PAD-ROUND#4"))
    )
    (comp (ref "H22")
      (value "MOUNT-PAD-ROUND#4")
      (footprint "eagle-import:#4-PAD")
      (libsource (lib "eagle-import") (part "MOUNT-PAD-ROUND#4"))
    )
    (comp (ref "H23")
      (value "MOUNT-PAD-ROUND#4")
      (footprint "eagle-import:#4-PAD")
      (libsource (lib "eagle-import") (part "MOUNT-PAD-ROUND#4"))
    )
    (comp (ref "H24")
      (value "MOUNT-PAD-ROUND#4")
      (footprint "eagle-import:#4-PAD")
      (libsource (lib "eagle-import") (part "MOUNT-PAD-ROUND#4"))
    )
    (comp (ref "H25")
      (value "MOUNT-PAD-ROUND#4")
      (footprint "eagle-import:#4-PAD")
      (libsource (lib "eagle-import") (part "MOUNT-PAD-ROUND#4"))
    )
    (comp (ref "H26")
      (value "MOUNT-PAD-ROUND#4")
      (footprint "eagle-import:#4-PAD")
      (libsource (lib "eagle-import") (part "MOUNT-PAD-ROUND#4"))
    )
    (comp (ref "H27")
      (value "MOUNT-PAD-ROUND#4")
      (footprint "eagle-import:#4-PAD")
      (libsource (lib "eagle-import") (part "MOUNT-PAD-ROUND#4"))
    )
    (comp (ref "H28")
      (value "MOUNT-PAD-ROUND#4")
      (footprint "eagle-import:#4-PAD")
      (libsource (lib "eagle-import") (part "MOUNT-PAD-ROUND#4"))
    )
    (comp (ref "H29")
      (value "MOUNT-PAD-ROUND#4")
      (footprint "eagle-import:#4-PAD")
      (libsource (lib "eagle-import") (part "MOUNT-PAD-ROUND#4"))
    )
    (comp (ref "H30")
      (value "MOUNT-PAD-ROUND#4")
      (footprint "eagle-import:#4-PAD")
      (libsource (lib "eagle-import") (part "MOUNT-PAD-ROUND#4"))
    )
    (comp (ref "H31")
      (value "MOUNT-PAD-ROUND#4")
      (footprint "eagle-import:#4-PAD")
      (libsource (lib "eagle-import") (part "MOUNT-PAD-ROUND#4"))
    )
    (comp (ref "H32")
      (value "MOUNT-PAD-ROUND#4")
      (footprint "eagle-import:#4-PAD")
      (libsource (lib "eagle-import") (part "MOUNT-PAD-ROUND#4"))
    )
    (comp (ref "H33")
      (value "MOUNT-PAD-ROUND#4")
      (footprint "eagle-import:#4-PAD")
      (libsource (lib "eagle-import") (part "MOUNT-PAD-ROUND#4"))
    )
    (comp (ref "H34")
      (value "MOUNT-PAD-ROUND#4")
      (footprint "eagle-import:#4-PAD")
      (libsource (lib "eagle-import") (part "MOUNT-PAD-ROUND#4"))
    )
    (comp (ref "H35")
      (value "MOUNT-PAD-ROUND#4")
      (footprint "eagle-import:#4-PAD")
      (libsource (lib "eagle-import") (part "MOUNT-PAD-ROUND#4"))
    )
    (comp (ref "H36")
      (value "MOUNT-PAD-ROUND#4")
      (footprint "eagle-import:#4-PAD")
      (libsource (lib "eagle-import") (part "MOUNT-PAD-ROUND#4"))
    )
    (comp (ref "H37")
      (value "MOUNT-PAD-ROUND#4")
      (footprint "eagle-import:#4-PAD")
      (libsource (lib "eagle-import") (part "MOUNT-PAD-ROUND#4"))
    )
    (comp (ref "H38")
      (value "MOUNT-PAD-ROUND#4")
      (footprint "eagle-import:#4-PAD")
      (libsource (lib "eagle-import") (part "MOUNT-PAD-ROUND#4"))
    )
    (comp (ref "H39")
      (value "MOUNT-PAD-ROUND#4")
      (footprint "eagle-import:#4-PAD")
      (libsource (lib "eagle-import") (part "MOUNT-PAD-ROUND#4"))
    )
    (comp (ref "H40")
      (value "MOUNT-PAD-ROUND#4")
      (footprint "eagle-import:#4-PAD")
      (libsource (lib "eagle-import") (part "MOUNT-PAD-ROUND#4"))
    )
    (comp (ref "J3")
      (value "BACKPLANE_CONTROLLER_MODULE")
      (footprint "eagle-import:BACKPLANE_MODULE_20PIN_10PIN")
      (libsource (lib "eagle-import") (part "BACKPLANE_CONTROLLER_MODULE"))
    )
    (comp (ref "J4")
      (value "BACKPLANE_POWER_MODULE")
      (footprint "eagle-import:BACKPLANE_MODULE_20PIN")
      (libsource (lib "eagle-import") (part "BACKPLANE_POWER_MODULE"))
    )
    (comp (ref "J8")
      (value "SCREW-TERMINAL_2_0.100")
      (footprint "eagle-import:CONN_BLOCK_2")
      (libsource (lib "eagle-import") (part "SCREW-TERMINAL_2_0.100"))
    )
    (comp (ref "J9")
      (value "SCREW-TERMINAL_2_0.100")
      (footprint "eagle-import:CONN_BLOCK_2")
      (libsource (lib "eagle-import") (part "SCREW-TERMINAL_2_0.100"))
    )
    (comp (ref "JP1")
      (value "FIDUCIAL1X2")
      (footprint "eagle-import:FIDUCIAL-1X2")
      (libsource (lib "eagle-import") (part "FIDUCIAL1X2"))
    )
    (comp (ref "JP2")
      (value "FIDUCIAL1X2")
      (footprint "eagle-import:FIDUCIAL-1X2")
      (libsource (lib "eagle-import") (part "FIDUCIAL1X2"))
    )
    (comp (ref "JP3")
      (value "FIDUCIAL1X2")
      (footprint "eagle-import:FIDUCIAL-1X2")
      (libsource (lib "eagle-import") (part "FIDUCIAL1X2"))
    )
    (comp (ref "JP4")
      (value "FIDUCIAL1X2")
      (footprint "eagle-import:FIDUCIAL-1X2")
      (libsource (lib "eagle-import") (part "FIDUCIAL1X2"))
    )
    (comp (ref "JP5")
      (value "FIDUCIAL1X2")
      (footprint "eagle-import:FIDUCIAL-1X2")
      (libsource (lib "eagle-import") (part "FIDUCIAL1X2"))
    )
    (comp (ref "JP6")
      (value "FIDUCIAL1X2")
      (footprint "eagle-import:FIDUCIAL-1X2")
      (libsource (lib "eagle-import") (part "FIDUCIAL1X2"))
    )
    (comp (ref "LOGO1")
      (value "UMICH_SOLID_GIANT")
      (footprint "eagle-import:UMICH_SOLID_1000MIL")
      (libsource (lib "eagle-import") (part "UMICH_SOLID_GIANT"))
    )
    (comp (ref "LOGO8")
      (value "UMICH_SOLID_MEDIUM")
      (footprint "eagle-import:UMICH_SOLID_200MIL")
      (libsource (lib "eagle-import") (part "UMICH_SOLID_MEDIUM"))
    )
    (comp (ref "LOGO9")
      (value "UMICH_SOLID_MEDIUM")
      (footprint "eagle-import:UMICH_SOLID_200MIL")
      (libsource (lib "eagle-import") (part "UMICH_SOLID_MEDIUM"))
    )
    (comp (ref "R27")
      (value "1.5kΩ")
      (footprint "eagle-import:0603-RES")
      (libsource (lib "eagle-import") (part "RESISTOR0603_RES"))
    )
    (comp (ref "R46")
      (value "10kΩ")
      (footprint "eagle-import:0603-RES")
      (libsource (lib "eagle-import") (part "RESISTOR0603_RES"))
    )
    (comp (ref "R47")
      (value "10kΩ")
      (footprint "eagle-import:0603-RES")
      (libsource (lib "eagle-import") (part "RESISTOR0603_RES"))
    )
    (comp (ref "R48")
      (value "10kΩ")
      (footprint "eagle-import:0603-RES")
      (libsource (lib "eagle-import") (part "RESISTOR0603_RES"))
    )
    (comp (ref "R49")
      (value "10kΩ")
      (footprint "eagle-import:0603-RES")
      (libsource (lib "eagle-import") (part "RESISTOR0603_RES"))
    )
    (comp (ref "R50")
      (value "10kΩ")
      (footprint "eagle-import:0603-RES")
      (libsource (lib "eagle-import") (part "RESISTOR0603_RES"))
    )
    (comp (ref "J0")
      (value "BACKPLANE_GENERIC_MODULE")
      (footprint "eagle-import:BACKPLANE_MODULE_14PIN")
      (libsource (lib "eagle-import") (part "BACKPLANE_GENERIC_MODULE"))
    )
    (comp (ref "J1")
      (value "BACKPLANE_GENERIC_MODULE")
      (footprint "eagle-import:BACKPLANE_MODULE_14PIN")
      (libsource (lib "eagle-import") (part "BACKPLANE_GENERIC_MODULE"))
    )
    (comp (ref "J2")
      (value "BACKPLANE_GENERIC_MODULE")
      (footprint "eagle-import:BACKPLANE_MODULE_14PIN")
      (libsource (lib "eagle-import") (part "BACKPLANE_GENERIC_MODULE"))
    )
    (comp (ref "J5")
      (value "BACKPLANE_GENERIC_MODULE")
      (footprint "eagle-import:BACKPLANE_MODULE_14PIN")
      (libsource (lib "eagle-import") (part "BACKPLANE_GENERIC_MODULE"))
    )
    (comp (ref "J6")
      (value "BACKPLANE_GENERIC_MODULE")
      (footprint "eagle-import:BACKPLANE_MODULE_14PIN")
      (libsource (lib "eagle-import") (part "BACKPLANE_GENERIC_MODULE"))
    )
    (comp (ref "J7")
      (value "BACKPLANE_GENERIC_MODULE")
      (footprint "eagle-import:BACKPLANE_MODULE_14PIN")
      (libsource (lib "eagle-import") (part "BACKPLANE_GENERIC_MODULE"))
    )
    (comp (ref "LOGO2")
      (value "UMICH_SOLID_MEDIUM")
      (footprint "eagle-import:UMICH_SOLID_200MIL")
      (libsource (lib "eagle-import") (part "UMICH_SOLID_MEDIUM"))
    )
    (comp (ref "LOGO3")
      (value "UMICH_SOLID_MEDIUM")
      (footprint "eagle-import:UMICH_SOLID_200MIL")
      (libsource (lib "eagle-import") (part "UMICH_SOLID_MEDIUM"))
    )
    (comp (ref "LOGO4")
      (value "UMICH_SOLID_MEDIUM")
      (footprint "eagle-import:UMICH_SOLID_200MIL")
      (libsource (lib "eagle-import") (part "UMICH_SOLID_MEDIUM"))
    )
    (comp (ref "LOGO5")
      (value "UMICH_SOLID_MEDIUM")
      (footprint "eagle-import:UMICH_SOLID_200MIL")
      (libsource (lib "eagle-import") (part "UMICH_SOLID_MEDIUM"))
    )
    (comp (ref "LOGO6")
      (value "UMICH_SOLID_MEDIUM")
      (footprint "eagle-import:UMICH_SOLID_200MIL")
      (libsource (lib "eagle-import") (part "UMICH_SOLID_MEDIUM"))
    )
    (comp (ref "LOGO7")
      (value "UMICH_SOLID_MEDIUM")
      (footprint "eagle-import:UMICH_SOLID_200MIL")
      (libsource (lib "eagle-import") (part "UMICH_SOLID_MEDIUM"))
    )
    (comp (ref "C15")
      (value "100nF")
      (footprint "eagle-import:0603_CAP")
      (libsource (lib "eagle-import") (part "CAPACITOR0603_CAP"))
    )
    (comp (ref "C16")
      (value "100nF")
      (footprint "eagle-import:0603_CAP")
      (libsource (lib "eagle-import") (part "CAPACITOR0603_CAP"))
    )
    (comp (ref "C17")
      (value "100nF")
      (footprint "eagle-import:0603_CAP")
      (libsource (lib "eagle-import") (part "CAPACITOR0603_CAP"))
    )
    (comp (ref "C18")
      (value "100nF")
      (footprint "eagle-import:0603_CAP")
      (libsource (lib "eagle-import") (part "CAPACITOR0603_CAP"))
    )
    (comp (ref "C19")
      (value "100nF")
      (footprint "eagle-import:0603_CAP")
      (libsource (lib "eagle-import") (part "CAPACITOR0603_CAP"))
    )
    (comp (ref "C20")
      (value "100nF")
      (footprint "eagle-import:0603_CAP")
      (libsource (lib "eagle-import") (part "CAPACITOR0603_CAP"))
    )
    (comp (ref "C21")
      (value "100nF")
      (footprint "eagle-import:0603_CAP")
      (libsource (lib "eagle-import") (part "CAPACITOR0603_CAP"))
    )
    (comp (ref "C22")
      (value "100nF")
      (footprint "eagle-import:0603_CAP")
      (libsource (lib "eagle-import") (part "CAPACITOR0603_CAP"))
    )
    (comp (ref "C23")
      (value "100nF")
      (footprint "eagle-import:0603_CAP")
      (libsource (lib "eagle-import") (part "CAPACITOR0603_CAP"))
    )
    (comp (ref "C24")
      (value "100nF")
      (footprint "eagle-import:0603_CAP")
      (libsource (lib "eagle-import") (part "CAPACITOR0603_CAP"))
    )
    (comp (ref "C25")
      (value "100nF")
      (footprint "eagle-import:0603_CAP")
      (libsource (lib "eagle-import") (part "CAPACITOR0603_CAP"))
    )
    (comp (ref "C26")
      (value "100nF")
      (footprint "eagle-import:0603_CAP")
      (libsource (lib "eagle-import") (part "CAPACITOR0603_CAP"))
    )
    (comp (ref "C82")
      (value "100nF")
      (footprint "eagle-import:0603_CAP")
      (libsource (lib "eagle-import") (part "CAPACITOR0603_CAP"))
    )
    (comp (ref "C83")
      (value "100nF")
      (footprint "eagle-import:0603_CAP")
      (libsource (lib "eagle-import") (part "CAPACITOR0603_CAP"))
    )
    (comp (ref "C84")
      (value "100nF")
      (footprint "eagle-import:0603_CAP")
      (libsource (lib "eagle-import") (part "CAPACITOR0603_CAP"))
    )
    (comp (ref "C85")
      (value "100nF")
      (footprint "eagle-import:0603_CAP")
      (libsource (lib "eagle-import") (part "CAPACITOR0603_CAP"))
    )
    (comp (ref "C86")
      (value "100nF")
      (footprint "eagle-import:0603_CAP")
      (libsource (lib "eagle-import") (part "CAPACITOR0603_CAP"))
    )
    (comp (ref "C87")
      (value "100nF")
      (footprint "eagle-import:0603_CAP")
      (libsource (lib "eagle-import") (part "CAPACITOR0603_CAP"))
    )
    (comp (ref "C90")
      (value "4.7uF")
      (footprint "eagle-import:0603_CAP")
      (libsource (lib "eagle-import") (part "CAPACITOR0603_CAP"))
    )
    (comp (ref "C91")
      (value "4.7uF")
      (footprint "eagle-import:0603_CAP")
      (libsource (lib "eagle-import") (part "CAPACITOR0603_CAP"))
    )
    (comp (ref "C92")
      (value "4.7uF")
      (footprint "eagle-import:0603_CAP")
      (libsource (lib "eagle-import") (part "CAPACITOR0603_CAP"))
    )
    (comp (ref "C93")
      (value "4.7uF")
      (footprint "eagle-import:0603_CAP")
      (libsource (lib "eagle-import") (part "CAPACITOR0603_CAP"))
    )
    (comp (ref "C94")
      (value "4.7uF")
      (footprint "eagle-import:0603_CAP")
      (libsource (lib "eagle-import") (part "CAPACITOR0603_CAP"))
    )
    (comp (ref "C95")
      (value "4.7uF")
      (footprint "eagle-import:0603_CAP")
      (libsource (lib "eagle-import") (part "CAPACITOR0603_CAP"))
    )
    (comp (ref "R34")
      (value "10kΩ")
      (footprint "eagle-import:0603-RES")
      (libsource (lib "eagle-import") (part "RESISTOR0603_RES"))
    )
    (comp (ref "R35")
      (value "10kΩ")
      (footprint "eagle-import:0603-RES")
      (libsource (lib "eagle-import") (part "RESISTOR0603_RES"))
    )
    (comp (ref "R36")
      (value "10kΩ")
      (footprint "eagle-import:0603-RES")
      (libsource (lib "eagle-import") (part "RESISTOR0603_RES"))
    )
    (comp (ref "R37")
      (value "10kΩ")
      (footprint "eagle-import:0603-RES")
      (libsource (lib "eagle-import") (part "RESISTOR0603_RES"))
    )
    (comp (ref "R38")
      (value "10kΩ")
      (footprint "eagle-import:0603-RES")
      (libsource (lib "eagle-import") (part "RESISTOR0603_RES"))
    )
    (comp (ref "R39")
      (value "10kΩ")
      (footprint "eagle-import:0603-RES")
      (libsource (lib "eagle-import") (part "RESISTOR0603_RES"))
    )
    (comp (ref "R40")
      (value "10kΩ")
      (footprint "eagle-import:0603-RES")
      (libsource (lib "eagle-import") (part "RESISTOR0603_RES"))
    )
    (comp (ref "R41")
      (value "10kΩ")
      (footprint "eagle-import:0603-RES")
      (libsource (lib "eagle-import") (part "RESISTOR0603_RES"))
    )
    (comp (ref "R42")
      (value "10kΩ")
      (footprint "eagle-import:0603-RES")
      (libsource (lib "eagle-import") (part "RESISTOR0603_RES"))
    )
    (comp (ref "R43")
      (value "10kΩ")
      (footprint "eagle-import:0603-RES")
      (libsource (lib "eagle-import") (part "RESISTOR0603_RES"))
    )
    (comp (ref "R44")
      (value "10kΩ")
      (footprint "eagle-import:0603-RES")
      (libsource (lib "eagle-import") (part "RESISTOR0603_RES"))
    )
    (comp (ref "R45")
      (value "10kΩ")
      (footprint "eagle-import:0603-RES")
      (libsource (lib "eagle-import") (part "RESISTOR0603_RES"))
    )
    (comp (ref "S1")
      (value "SIP3240X")
      (footprint "eagle-import:TDFN4")
      (libsource (lib "eagle-import") (part "SIP3240X"))
    )
    (comp (ref "S2")
      (value "SIP3240X")
      (footprint "eagle-import:TDFN4")
      (libsource (lib "eagle-import") (part "SIP3240X"))
    )
    (comp (ref "S3")
      (value "SIP3240X")
      (footprint "eagle-import:TDFN4")
      (libsource (lib "eagle-import") (part "SIP3240X"))
    )
    (comp (ref "S4")
      (value "SIP3240X")
      (footprint "eagle-import:TDFN4")
      (libsource (lib "eagle-import") (part "SIP3240X"))
    )
    (comp (ref "S5")
      (value "SIP3240X")
      (footprint "eagle-import:TDFN4")
      (libsource (lib "eagle-import") (part "SIP3240X"))
    )
    (comp (ref "S6")
      (value "SIP3240X")
      (footprint "eagle-import:TDFN4")
      (libsource (lib "eagle-import") (part "SIP3240X"))
    )
    (comp (ref "U2")
      (value "FXMA2102")
      (footprint "eagle-import:UMLP-8")
      (libsource (lib "eagle-import") (part "FXMA2102"))
    )
    (comp (ref "U3")
      (value "FXMA2102")
      (footprint "eagle-import:UMLP-8")
      (libsource (lib "eagle-import") (part "FXMA2102"))
    )
    (comp (ref "U4")
      (value "FXMA2102")
      (footprint "eagle-import:UMLP-8")
      (libsource (lib "eagle-import") (part "FXMA2102"))
    )
    (comp (ref "U5")
      (value "FXMA2102")
      (footprint "eagle-import:UMLP-8")
      (libsource (lib "eagle-import") (part "FXMA2102"))
    )
    (comp (ref "U6")
      (value "FXMA2102")
      (footprint "eagle-import:UMLP-8")
      (libsource (lib "eagle-import") (part "FXMA2102"))
    )
    (comp (ref "U7")
      (value "FXMA2102")
      (footprint "eagle-import:UMLP-8")
      (libsource (lib "eagle-import") (part "FXMA2102"))
    )
    (comp (ref "LED1001")
      (value "LED0603")
      (footprint "eagle-import:LED-0603")
      (libsource (lib "eagle-import") (part "LED0603"))
    )
    (comp (ref "LED1002")
      (value "LED0603")
      (footprint "eagle-import:LED-0603")
      (libsource (lib "eagle-import") (part "LED0603"))
    )
    (comp (ref "LED1003")
      (value "LED0603")
      (footprint "eagle-import:LED-0603")
      (libsource (lib "eagle-import") (part "LED0603"))
    )
    (comp (ref "LED1004")
      (value "LED0603")
      (footprint "eagle-import:LED-0603")
      (libsource (lib "eagle-import") (part "LED0603"))
    )
    (comp (ref "LED1005")
      (value "LED0603")
      (footprint "eagle-import:LED-0603")
      (libsource (lib "eagle-import") (part "LED0603"))
    )
    (comp (ref "LED1006")
      (value "LED0603")
      (footprint "eagle-import:LED-0603")
      (libsource (lib "eagle-import") (part "LED0603"))
    )
    (comp (ref "LED1007")
      (value "LED0603")
      (footprint "eagle-import:LED-0603")
      (libsource (lib "eagle-import") (part "LED0603"))
    )
    (comp (ref "LED1008")
      (value "LED0603")
      (footprint "eagle-import:LED-0603")
      (libsource (lib "eagle-import") (part "LED0603"))
    )
    (comp (ref "LED1009")
      (value "LED0603")
      (footprint "eagle-import:LED-0603")
      (libsource (lib "eagle-import") (part "LED0603"))
    )
    (comp (ref "LED1010")
      (value "LED0603")
      (footprint "eagle-import:LED-0603")
      (libsource (lib "eagle-import") (part "LED0603"))
    )
    (comp (ref "LED1011")
      (value "LED0603")
      (footprint "eagle-import:LED-0603")
      (libsource (lib "eagle-import") (part "LED0603"))
    )
    (comp (ref "LED1012")
      (value "LED0603")
      (footprint "eagle-import:LED-0603")
      (libsource (lib "eagle-import") (part "LED0603"))
    )
    (comp (ref "LED1013")
      (value "LED0603")
      (footprint "eagle-import:LED-0603")
      (libsource (lib "eagle-import") (part "LED0603"))
    )
    (comp (ref "LED1014")
      (value "LED0603")
      (footprint "eagle-import:LED-0603")
      (libsource (lib "eagle-import") (part "LED0603"))
    )
    (comp (ref "LED1015")
      (value "LED0603")
      (footprint "eagle-import:LED-0603")
      (libsource (lib "eagle-import") (part "LED0603"))
    )
    (comp (ref "LED1016")
      (value "LED0603")
      (footprint "eagle-import:LED-0603")
      (libsource (lib "eagle-import") (part "LED0603"))
    )
    (comp (ref "LED1017")
      (value "LED0603")
      (footprint "eagle-import:LED-0603")
      (libsource (lib "eagle-import") (part "LED0603"))
    )
    (comp (ref "LED1018")
      (value "LED0603")
      (footprint "eagle-import:LED-0603")
      (libsource (lib "eagle-import") (part "LED0603"))
    )
    (comp (ref "R1001")
      (value "15Ω")
      (footprint "eagle-import:0603-RES")
      (libsource (lib "eagle-import") (part "RESISTOR0603_RES"))
    )
    (comp (ref "R1002")
      (value "15Ω")
      (footprint "eagle-import:0603-RES")
      (libsource (lib "eagle-import") (part "RESISTOR0603_RES"))
    )
    (comp (ref "R1003")
      (value "15Ω")
      (footprint "eagle-import:0603-RES")
      (libsource (lib "eagle-import") (part "RESISTOR0603_RES"))
    )
    (comp (ref "R1004")
      (value "15Ω")
      (footprint "eagle-import:0603-RES")
      (libsource (lib "eagle-import") (part "RESISTOR0603_RES"))
    )
    (comp (ref "R1005")
      (value "15Ω")
      (footprint "eagle-import:0603-RES")
      (libsource (lib "eagle-import") (part "RESISTOR0603_RES"))
    )
    (comp (ref "R1006")
      (value "15Ω")
      (footprint "eagle-import:0603-RES")
      (libsource (lib "eagle-import") (part "RESISTOR0603_RES"))
    )
    (comp (ref "R1007")
      (value "15Ω")
      (footprint "eagle-import:0603-RES")
      (libsource (lib "eagle-import") (part "RESISTOR0603_RES"))
    )
    (comp (ref "R1008")
      (value "15Ω")
      (footprint "eagle-import:0603-RES")
      (libsource (lib "eagle-import") (part "RESISTOR0603_RES"))
    )
    (comp (ref "R1009")
      (value "15Ω")
      (footprint "eagle-import:0603-RES")
      (libsource (lib "eagle-import") (part "RESISTOR0603_RES"))
    )
    (comp (ref "R1010")
      (value "15Ω")
      (footprint "eagle-import:0603-RES")
      (libsource (lib "eagle-import") (part "RESISTOR0603_RES"))
    )
    (comp (ref "R1011")
      (value "15Ω")
      (footprint "eagle-import:0603-RES")
      (libsource (lib "eagle-import") (part "RESISTOR0603_RES"))
    )
    (comp (ref "R1012")
      (value "15Ω")
      (footprint "eagle-import:0603-RES")
      (libsource (lib "eagle-import") (part "RESISTOR0603_RES"))
    )
    (comp (ref "R1013")
      (value "15Ω")
      (footprint "eagle-import:0603-RES")
      (libsource (lib "eagle-import") (part "RESISTOR0603_RES"))
    )
    (comp (ref "R1014")
      (value "15Ω")
      (footprint "eagle-import:0603-RES")
      (libsource (lib "eagle-import") (part "RESISTOR0603_RES"))
    )
    (comp (ref "R1015")
      (value "15Ω")
      (footprint "eagle-import:0603-RES")
      (libsource (lib "eagle-import") (part "RESISTOR0603_RES"))
    )
    (comp (ref "R1016")
      (value "15Ω")
      (footprint "eagle-import:0603-RES")
      (libsource (lib "eagle-import") (part "RESISTOR0603_RES"))
    )
    (comp (ref "R1017")
      (value "15Ω")
      (footprint "eagle-import:0603-RES")
      (libsource (lib "eagle-import") (part "RESISTOR0603_RES"))
    )
    (comp (ref "R1018")
      (value "15Ω")
      (footprint "eagle-import:0603-RES")
      (libsource (lib "eagle-import") (part "RESISTOR0603_RES"))
    )
    (comp (ref "TP1")
      (value "TEST_POINT_0.040IN")
      (footprint "eagle-import:TESTPOINT_0.040IN")
      (libsource (lib "eagle-import") (part "TEST_POINT_0.040IN"))
    )
    (comp (ref "TP2")
      (value "TEST_POINT_0.040IN")
      (footprint "eagle-import:TESTPOINT_0.040IN")
      (libsource (lib "eagle-import") (part "TEST_POINT_0.040IN"))
    )
    (comp (ref "TP3")
      (value "TEST_POINT_0.040IN")
      (footprint "eagle-import:TESTPOINT_0.040IN")
      (libsource (lib "eagle-import") (part "TEST_POINT_0.040IN"))
    )
    (comp (ref "TP4")
      (value "TEST_POINT_0.040IN")
      (footprint "eagle-import:TESTPOINT_0.040IN")
      (libsource (lib "eagle-import") (part "TEST_POINT_0.040IN"))
    )
    (comp (ref "TP5")
      (value "TEST_POINT_0.040IN")
      (footprint "eagle-import:TESTPOINT_0.040IN")
      (libsource (lib "eagle-import") (part "TEST_POINT_0.040IN"))
    )
    (comp (ref "TP6")
      (value "TEST_POINT_0.040IN")
      (footprint "eagle-import:TESTPOINT_0.040IN")
      (libsource (lib "eagle-import") (part "TEST_POINT_0.040IN"))
    )
    (comp (ref "TP7")
      (value "TEST_POINT_0.040IN")
      (footprint "eagle-import:TESTPOINT_0.040IN")
      (libsource (lib "eagle-import") (part "TEST_POINT_0.040IN"))
    )
    (comp (ref "TP8")
      (value "TEST_POINT_0.040IN")
      (footprint "eagle-import:TESTPOINT_0.040IN")
      (libsource (lib "eagle-import") (part "TEST_POINT_0.040IN"))
    )
    (comp (ref "TP9")
      (value "TEST_POINT_0.040IN")
      (footprint "eagle-import:TESTPOINT_0.040IN")
      (libsource (lib "eagle-import") (part "TEST_POINT_0.040IN"))
    )
    (comp (ref "TP10")
      (value "TEST_POINT_0.040IN")
      (footprint "eagle-import:TESTPOINT_0.040IN")
      (libsource (lib "eagle-import") (part "TEST_POINT_0.040IN"))
    )
    (comp (ref "TP11")
      (value "TEST_POINT_0.040IN")
      (footprint "eagle-import:TESTPOINT_0.040IN")
      (libsource (lib "eagle-import") (part "TEST_POINT_0.040IN"))
    )
    (comp (ref "TP12")
      (value "TEST_POINT_0.040IN")
      (footprint "eagle-import:TESTPOINT_0.040IN")
      (libsource (lib "eagle-import") (part "TEST_POINT_0.040IN"))
    )
    (comp (ref "TP13")
      (value "TEST_POINT_0.040IN")
      (footprint "eagle-import:TESTPOINT_0.040IN")
      (libsource (lib "eagle-import") (part "TEST_POINT_0.040IN"))
    )
    (comp (ref "TP14")
      (value "TEST_POINT_0.040IN")
      (footprint "eagle-import:TESTPOINT_0.040IN")
      (libsource (lib "eagle-import") (part "TEST_POINT_0.040IN"))
    )
    (comp (ref "TP15")
      (value "TEST_POINT_0.040IN")
      (footprint "eagle-import:TESTPOINT_0.040IN")
      (libsource (lib "eagle-import") (part "TEST_POINT_0.040IN"))
    )
    (comp (ref "TP16")
      (value "TEST_POINT_0.040IN")
      (footprint "eagle-import:TESTPOINT_0.040IN")
      (libsource (lib "eagle-import") (part "TEST_POINT_0.040IN"))
    )
    (comp (ref "TP17")
      (value "TEST_POINT_0.040IN")
      (footprint "eagle-import:TESTPOINT_0.040IN")
      (libsource (lib "eagle-import") (part "TEST_POINT_0.040IN"))
    )
    (comp (ref "TP18")
      (value "TEST_POINT_0.040IN")
      (footprint "eagle-import:TESTPOINT_0.040IN")
      (libsource (lib "eagle-import") (part "TEST_POINT_0.040IN"))
    )
    (comp (ref "TP19")
      (value "TEST_POINT_0.040IN")
      (footprint "eagle-import:TESTPOINT_0.040IN")
      (libsource (lib "eagle-import") (part "TEST_POINT_0.040IN"))
    )
    (comp (ref "TP20")
      (value "TEST_POINT_0.040IN")
      (footprint "eagle-import:TESTPOINT_0.040IN")
      (libsource (lib "eagle-import") (part "TEST_POINT_0.040IN"))
    )
    (comp (ref "TP21")
      (value "TEST_POINT_0.040IN")
      (footprint "eagle-import:TESTPOINT_0.040IN")
      (libsource (lib "eagle-import") (part "TEST_POINT_0.040IN"))
    )
    (comp (ref "TP22")
      (value "TEST_POINT_0.040IN")
      (footprint "eagle-import:TESTPOINT_0.040IN")
      (libsource (lib "eagle-import") (part "TEST_POINT_0.040IN"))
    )
    (comp (ref "TP23")
      (value "TEST_POINT_0.040IN")
      (footprint "eagle-import:TESTPOINT_0.040IN")
      (libsource (lib "eagle-import") (part "TEST_POINT_0.040IN"))
    )
    (comp (ref "TP24")
      (value "TEST_POINT_0.040IN")
      (footprint "eagle-import:TESTPOINT_0.040IN")
      (libsource (lib "eagle-import") (part "TEST_POINT_0.040IN"))
    )
    (comp (ref "TP25")
      (value "TEST_POINT_0.040IN")
      (footprint "eagle-import:TESTPOINT_0.040IN")
      (libsource (lib "eagle-import") (part "TEST_POINT_0.040IN"))
    )
    (comp (ref "TP26")
      (value "TEST_POINT_0.040IN")
      (footprint "eagle-import:TESTPOINT_0.040IN")
      (libsource (lib "eagle-import") (part "TEST_POINT_0.040IN"))
    )
    (comp (ref "TP27")
      (value "TEST_POINT_0.040IN")
      (footprint "eagle-import:TESTPOINT_0.040IN")
      (libsource (lib "eagle-import") (part "TEST_POINT_0.040IN"))
    )
    (comp (ref "TP28")
      (value "TEST_POINT_0.040IN")
      (footprint "eagle-import:TESTPOINT_0.040IN")
      (libsource (lib "eagle-import") (part "TEST_POINT_0.040IN"))
    )
    (comp (ref "TP29")
      (value "TEST_POINT_0.040IN")
      (footprint "eagle-import:TESTPOINT_0.040IN")
      (libsource (lib "eagle-import") (part "TEST_POINT_0.040IN"))
    )
    (comp (ref "TP30")
      (value "TEST_POINT_0.040IN")
      (footprint "eagle-import:TESTPOINT_0.040IN")
      (libsource (lib "eagle-import") (part "TEST_POINT_0.040IN"))
    )
    (comp (ref "TP31")
      (value "TEST_POINT_0.040IN")
      (footprint "eagle-import:TESTPOINT_0.040IN")
      (libsource (lib "eagle-import") (part "TEST_POINT_0.040IN"))
    )
    (comp (ref "TP32")
      (value "TEST_POINT_0.040IN")
      (footprint "eagle-import:TESTPOINT_0.040IN")
      (libsource (lib "eagle-import") (part "TEST_POINT_0.040IN"))
    )
    (comp (ref "TP33")
      (value "TEST_POINT_0.040IN")
      (footprint "eagle-import:TESTPOINT_0.040IN")
      (libsource (lib "eagle-import") (part "TEST_POINT_0.040IN"))
    )
    (comp (ref "TP34")
      (value "TEST_POINT_0.040IN")
      (footprint "eagle-import:TESTPOINT_0.040IN")
      (libsource (lib "eagle-import") (part "TEST_POINT_0.040IN"))
    )
    (comp (ref "TP35")
      (value "TEST_POINT_0.040IN")
      (footprint "eagle-import:TESTPOINT_0.040IN")
      (libsource (lib "eagle-import") (part "TEST_POINT_0.040IN"))
    )
    (comp (ref "TP36")
      (value "TEST_POINT_0.040IN")
      (footprint "eagle-import:TESTPOINT_0.040IN")
      (libsource (lib "eagle-import") (part "TEST_POINT_0.040IN"))
    )
    (comp (ref "TP37")
      (value "TEST_POINT_0.040IN")
      (footprint "eagle-import:TESTPOINT_0.040IN")
      (libsource (lib "eagle-import") (part "TEST_POINT_0.040IN"))
    )
    (comp (ref "TP38")
      (value "TEST_POINT_0.040IN")
      (footprint "eagle-import:TESTPOINT_0.040IN")
      (libsource (lib "eagle-import") (part "TEST_POINT_0.040IN"))
    )
    (comp (ref "TP39")
      (value "TEST_POINT_0.040IN")
      (footprint "eagle-import:TESTPOINT_0.040IN")
      (libsource (lib "eagle-import") (part "TEST_POINT_0.040IN"))
    )
    (comp (ref "TP40")
      (value "TEST_POINT_0.040IN")
      (footprint "eagle-import:TESTPOINT_0.040IN")
      (libsource (lib "eagle-import") (part "TEST_POINT_0.040IN"))
    )
    (comp (ref "TP41")
      (value "TEST_POINT_0.040IN")
      (footprint "eagle-import:TESTPOINT_0.040IN")
      (libsource (lib "eagle-import") (part "TEST_POINT_0.040IN"))
    )
    (comp (ref "TP42")
      (value "TEST_POINT_0.040IN")
      (footprint "eagle-import:TESTPOINT_0.040IN")
      (libsource (lib "eagle-import") (part "TEST_POINT_0.040IN"))
    )
    (comp (ref "TP43")
      (value "TEST_POINT_0.040IN")
      (footprint "eagle-import:TESTPOINT_0.040IN")
      (libsource (lib "eagle-import") (part "TEST_POINT_0.040IN"))
    )
    (comp (ref "TP1001")
      (value "TEST_POINT_0.040IN")
      (footprint "eagle-import:TESTPOINT_0.040IN")
      (libsource (lib "eagle-import") (part "TEST_POINT_0.040IN"))
    )
    (comp (ref "TP1002")
      (value "TEST_POINT_0.040IN")
      (footprint "eagle-import:TESTPOINT_0.040IN")
      (libsource (lib "eagle-import") (part "TEST_POINT_0.040IN"))
    )
    (comp (ref "TP1003")
      (value "TEST_POINT_0.040IN")
      (footprint "eagle-import:TESTPOINT_0.040IN")
      (libsource (lib "eagle-import") (part "TEST_POINT_0.040IN"))
    )
    (comp (ref "TP1004")
      (value "TEST_POINT_0.040IN")
      (footprint "eagle-import:TESTPOINT_0.040IN")
      (libsource (lib "eagle-import") (part "TEST_POINT_0.040IN"))
    )
    (comp (ref "TP1005")
      (value "TEST_POINT_0.040IN")
      (footprint "eagle-import:TESTPOINT_0.040IN")
      (libsource (lib "eagle-import") (part "TEST_POINT_0.040IN"))
    )
    (comp (ref "TP1006")
      (value "TEST_POINT_0.040IN")
      (footprint "eagle-import:TESTPOINT_0.040IN")
      (libsource (lib "eagle-import") (part "TEST_POINT_0.040IN"))
    )
    (comp (ref "TP1007")
      (value "TEST_POINT_0.040IN")
      (footprint "eagle-import:TESTPOINT_0.040IN")
      (libsource (lib "eagle-import") (part "TEST_POINT_0.040IN"))
    )
    (comp (ref "TP1008")
      (value "TEST_POINT_0.040IN")
      (footprint "eagle-import:TESTPOINT_0.040IN")
      (libsource (lib "eagle-import") (part "TEST_POINT_0.040IN"))
    )
    (comp (ref "TP1009")
      (value "TEST_POINT_0.040IN")
      (footprint "eagle-import:TESTPOINT_0.040IN")
      (libsource (lib "eagle-import") (part "TEST_POINT_0.040IN"))
    )
    (comp (ref "TP1010")
      (value "TEST_POINT_0.040IN")
      (footprint "eagle-import:TESTPOINT_0.040IN")
      (libsource (lib "eagle-import") (part "TEST_POINT_0.040IN"))
    )
    (comp (ref "TP1011")
      (value "TEST_POINT_0.040IN")
      (footprint "eagle-import:TESTPOINT_0.040IN")
      (libsource (lib "eagle-import") (part "TEST_POINT_0.040IN"))
    )
    (comp (ref "TP1012")
      (value "TEST_POINT_0.040IN")
      (footprint "eagle-import:TESTPOINT_0.040IN")
      (libsource (lib "eagle-import") (part "TEST_POINT_0.040IN"))
    )
    (comp (ref "TP1013")
      (value "TEST_POINT_0.040IN")
      (footprint "eagle-import:TESTPOINT_0.040IN")
      (libsource (lib "eagle-import") (part "TEST_POINT_0.040IN"))
    )
    (comp (ref "TP1014")
      (value "TEST_POINT_0.040IN")
      (footprint "eagle-import:TESTPOINT_0.040IN")
      (libsource (lib "eagle-import") (part "TEST_POINT_0.040IN"))
    )
    (comp (ref "TP1015")
      (value "TEST_POINT_0.040IN")
      (footprint "eagle-import:TESTPOINT_0.040IN")
      (libsource (lib "eagle-import") (part "TEST_POINT_0.040IN"))
    )
    (comp (ref "TP1016")
      (value "TEST_POINT_0.040IN")
      (footprint "eagle-import:TESTPOINT_0.040IN")
      (libsource (lib "eagle-import") (part "TEST_POINT_0.040IN"))
    )
    (comp (ref "TP1017")
      (value "TEST_POINT_0.040IN")
      (footprint "eagle-import:TESTPOINT_0.040IN")
      (libsource (lib "eagle-import") (part "TEST_POINT_0.040IN"))
    )
    (comp (ref "TP1018")
      (value "TEST_POINT_0.040IN")
      (footprint "eagle-import:TESTPOINT_0.040IN")
      (libsource (lib "eagle-import") (part "TEST_POINT_0.040IN"))
    )
    (comp (ref "C3")
      (value "22pF")
      (footprint "eagle-import:0402_CAP")
      (libsource (lib "eagle-import") (part "CAPACITOR0402_CAP"))
    )
    (comp (ref "C4")
      (value "22pF")
      (footprint "eagle-import:0402_CAP")
      (libsource (lib "eagle-import") (part "CAPACITOR0402_CAP"))
    )
    (comp (ref "C5")
      (value "22pF")
      (footprint "eagle-import:0402_CAP")
      (libsource (lib "eagle-import") (part "CAPACITOR0402_CAP"))
    )
    (comp (ref "C6")
      (value "22pF")
      (footprint "eagle-import:0402_CAP")
      (libsource (lib "eagle-import") (part "CAPACITOR0402_CAP"))
    )
    (comp (ref "C7")
      (value "22pF")
      (footprint "eagle-import:0402_CAP")
      (libsource (lib "eagle-import") (part "CAPACITOR0402_CAP"))
    )
    (comp (ref "C8")
      (value "22pF")
      (footprint "eagle-import:0402_CAP")
      (libsource (lib "eagle-import") (part "CAPACITOR0402_CAP"))
    )
    (comp (ref "C9")
      (value "22pF")
      (footprint "eagle-import:0402_CAP")
      (libsource (lib "eagle-import") (part "CAPACITOR0402_CAP"))
    )
    (comp (ref "C10")
      (value "22pF")
      (footprint "eagle-import:0402_CAP")
      (libsource (lib "eagle-import") (part "CAPACITOR0402_CAP"))
    )
    (comp (ref "C11")
      (value "22pF")
      (footprint "eagle-import:0402_CAP")
      (libsource (lib "eagle-import") (part "CAPACITOR0402_CAP"))
    )
    (comp (ref "C12")
      (value "22pF")
      (footprint "eagle-import:0402_CAP")
      (libsource (lib "eagle-import") (part "CAPACITOR0402_CAP"))
    )
    (comp (ref "C13")
      (value "22pF")
      (footprint "eagle-import:0402_CAP")
      (libsource (lib "eagle-import") (part "CAPACITOR0402_CAP"))
    )
    (comp (ref "C14")
      (value "22pF")
      (footprint "eagle-import:0402_CAP")
      (libsource (lib "eagle-import") (part "CAPACITOR0402_CAP"))
    )
    (comp (ref "C76")
      (value "100nF")
      (footprint "eagle-import:0603_CAP")
      (libsource (lib "eagle-import") (part "CAPACITOR0603_CAP"))
    )
    (comp (ref "C77")
      (value "100nF")
      (footprint "eagle-import:0603_CAP")
      (libsource (lib "eagle-import") (part "CAPACITOR0603_CAP"))
    )
    (comp (ref "C78")
      (value "100nF")
      (footprint "eagle-import:0603_CAP")
      (libsource (lib "eagle-import") (part "CAPACITOR0603_CAP"))
    )
    (comp (ref "C79")
      (value "100nF")
      (footprint "eagle-import:0603_CAP")
      (libsource (lib "eagle-import") (part "CAPACITOR0603_CAP"))
    )
    (comp (ref "C80")
      (value "100nF")
      (footprint "eagle-import:0603_CAP")
      (libsource (lib "eagle-import") (part "CAPACITOR0603_CAP"))
    )
    (comp (ref "C81")
      (value "100nF")
      (footprint "eagle-import:0603_CAP")
      (libsource (lib "eagle-import") (part "CAPACITOR0603_CAP"))
    )
    (comp (ref "D1")
      (value "SN75240-TSSOP")
      (footprint "eagle-import:TSSOP-8")
      (libsource (lib "eagle-import") (part "SN75240-TSSOP"))
    )
    (comp (ref "D2")
      (value "SN75240-TSSOP")
      (footprint "eagle-import:TSSOP-8")
      (libsource (lib "eagle-import") (part "SN75240-TSSOP"))
    )
    (comp (ref "D3")
      (value "SN75240-TSSOP")
      (footprint "eagle-import:TSSOP-8")
      (libsource (lib "eagle-import") (part "SN75240-TSSOP"))
    )
    (comp (ref "D4")
      (value "SN75240-TSSOP")
      (footprint "eagle-import:TSSOP-8")
      (libsource (lib "eagle-import") (part "SN75240-TSSOP"))
    )
    (comp (ref "R1")
      (value "27Ω")
      (footprint "eagle-import:0402_RES-HIGH_SPEED")
      (libsource (lib "eagle-import") (part "RESISTOR0402_RES-HIGH_SPEED"))
    )
    (comp (ref "R2")
      (value "27Ω")
      (footprint "eagle-import:0402_RES-HIGH_SPEED")
      (libsource (lib "eagle-import") (part "RESISTOR0402_RES-HIGH_SPEED"))
    )
    (comp (ref "R3")
      (value "27Ω")
      (footprint "eagle-import:0402_RES-HIGH_SPEED")
      (libsource (lib "eagle-import") (part "RESISTOR0402_RES-HIGH_SPEED"))
    )
    (comp (ref "R4")
      (value "27Ω")
      (footprint "eagle-import:0402_RES-HIGH_SPEED")
      (libsource (lib "eagle-import") (part "RESISTOR0402_RES-HIGH_SPEED"))
    )
    (comp (ref "R5")
      (value "27Ω")
      (footprint "eagle-import:0402_RES-HIGH_SPEED")
      (libsource (lib "eagle-import") (part "RESISTOR0402_RES-HIGH_SPEED"))
    )
    (comp (ref "R6")
      (value "27Ω")
      (footprint "eagle-import:0402_RES-HIGH_SPEED")
      (libsource (lib "eagle-import") (part "RESISTOR0402_RES-HIGH_SPEED"))
    )
    (comp (ref "R7")
      (value "27Ω")
      (footprint "eagle-import:0402_RES-HIGH_SPEED")
      (libsource (lib "eagle-import") (part "RESISTOR0402_RES-HIGH_SPEED"))
    )
    (comp (ref "R8")
      (value "27Ω")
      (footprint "eagle-import:0402_RES-HIGH_SPEED")
      (libsource (lib "eagle-import") (part "RESISTOR0402_RES-HIGH_SPEED"))
    )
    (comp (ref "R9")
      (value "27Ω")
      (footprint "eagle-import:0402_RES-HIGH_SPEED")
      (libsource (lib "eagle-import") (part "RESISTOR0402_RES-HIGH_SPEED"))
    )
    (comp (ref "R10")
      (value "27Ω")
      (footprint "eagle-import:0402_RES-HIGH_SPEED")
      (libsource (lib "eagle-import") (part "RESISTOR0402_RES-HIGH_SPEED"))
    )
    (comp (ref "R11")
      (value "27Ω")
      (footprint "eagle-import:0402_RES-HIGH_SPEED")
      (libsource (lib "eagle-import") (part "RESISTOR0402_RES-HIGH_SPEED"))
    )
    (comp (ref "R12")
      (value "27Ω")
      (footprint "eagle-import:0402_RES-HIGH_SPEED")
      (libsource (lib "eagle-import") (part "RESISTOR0402_RES-HIGH_SPEED"))
    )
    (comp (ref "R13")
      (value "50Ω")
      (footprint "eagle-import:0603-RES")
      (libsource (lib "eagle-import") (part "RESISTOR0603_RES"))
    )
    (comp (ref "R14")
      (value "50Ω")
      (footprint "eagle-import:0603-RES")
      (libsource (lib "eagle-import") (part "RESISTOR0603_RES"))
    )
    (comp (ref "R15")
      (value "50Ω")
      (footprint "eagle-import:0603-RES")
      (libsource (lib "eagle-import") (part "RESISTOR0603_RES"))
    )
    (comp (ref "R16")
      (value "50Ω")
      (footprint "eagle-import:0603-RES")
      (libsource (lib "eagle-import") (part "RESISTOR0603_RES"))
    )
    (comp (ref "R17")
      (value "50Ω")
      (footprint "eagle-import:0603-RES")
      (libsource (lib "eagle-import") (part "RESISTOR0603_RES"))
    )
    (comp (ref "R18")
      (value "50Ω")
      (footprint "eagle-import:0603-RES")
      (libsource (lib "eagle-import") (part "RESISTOR0603_RES"))
    )
    (comp (ref "R19")
      (value "50Ω")
      (footprint "eagle-import:0603-RES")
      (libsource (lib "eagle-import") (part "RESISTOR0603_RES"))
    )
    (comp (ref "R20")
      (value "50Ω")
      (footprint "eagle-import:0603-RES")
      (libsource (lib "eagle-import") (part "RESISTOR0603_RES"))
    )
    (comp (ref "R21")
      (value "50Ω")
      (footprint "eagle-import:0603-RES")
      (libsource (lib "eagle-import") (part "RESISTOR0603_RES"))
    )
    (comp (ref "R22")
      (value "50Ω")
      (footprint "eagle-import:0603-RES")
      (libsource (lib "eagle-import") (part "RESISTOR0603_RES"))
    )
    (comp (ref "R23")
      (value "50Ω")
      (footprint "eagle-import:0603-RES")
      (libsource (lib "eagle-import") (part "RESISTOR0603_RES"))
    )
    (comp (ref "R24")
      (value "50Ω")
      (footprint "eagle-import:0603-RES")
      (libsource (lib "eagle-import") (part "RESISTOR0603_RES"))
    )
    (comp (ref "R53")
      (value "15kΩ")
      (footprint "eagle-import:0603-RES")
      (libsource (lib "eagle-import") (part "RESISTOR0603_RES"))
    )
    (comp (ref "R54")
      (value "15kΩ")
      (footprint "eagle-import:0603-RES")
      (libsource (lib "eagle-import") (part "RESISTOR0603_RES"))
    )
    (comp (ref "R55")
      (value "15kΩ")
      (footprint "eagle-import:0603-RES")
      (libsource (lib "eagle-import") (part "RESISTOR0603_RES"))
    )
    (comp (ref "R56")
      (value "15kΩ")
      (footprint "eagle-import:0603-RES")
      (libsource (lib "eagle-import") (part "RESISTOR0603_RES"))
    )
    (comp (ref "R57")
      (value "15kΩ")
      (footprint "eagle-import:0603-RES")
      (libsource (lib "eagle-import") (part "RESISTOR0603_RES"))
    )
    (comp (ref "R58")
      (value "15kΩ")
      (footprint "eagle-import:0603-RES")
      (libsource (lib "eagle-import") (part "RESISTOR0603_RES"))
    )
    (comp (ref "R59")
      (value "15kΩ")
      (footprint "eagle-import:0603-RES")
      (libsource (lib "eagle-import") (part "RESISTOR0603_RES"))
    )
    (comp (ref "R60")
      (value "15kΩ")
      (footprint "eagle-import:0603-RES")
      (libsource (lib "eagle-import") (part "RESISTOR0603_RES"))
    )
    (comp (ref "R61")
      (value "15kΩ")
      (footprint "eagle-import:0603-RES")
      (libsource (lib "eagle-import") (part "RESISTOR0603_RES"))
    )
    (comp (ref "R62")
      (value "15kΩ")
      (footprint "eagle-import:0603-RES")
      (libsource (lib "eagle-import") (part "RESISTOR0603_RES"))
    )
    (comp (ref "R63")
      (value "15kΩ")
      (footprint "eagle-import:0603-RES")
      (libsource (lib "eagle-import") (part "RESISTOR0603_RES"))
    )
    (comp (ref "R64")
      (value "15kΩ")
      (footprint "eagle-import:0603-RES")
      (libsource (lib "eagle-import") (part "RESISTOR0603_RES"))
    )
    (comp (ref "U20")
      (value "TS3USB30E")
      (footprint "eagle-import:UQFN-10")
      (libsource (lib "eagle-import") (part "TS3USB30E"))
    )
    (comp (ref "U21")
      (value "TS3USB30E")
      (footprint "eagle-import:UQFN-10")
      (libsource (lib "eagle-import") (part "TS3USB30E"))
    )
    (comp (ref "U22")
      (value "TS3USB30E")
      (footprint "eagle-import:UQFN-10")
      (libsource (lib "eagle-import") (part "TS3USB30E"))
    )
    (comp (ref "U23")
      (value "TS3USB30E")
      (footprint "eagle-import:UQFN-10")
      (libsource (lib "eagle-import") (part "TS3USB30E"))
    )
    (comp (ref "U24")
      (value "TS3USB30E")
      (footprint "eagle-import:UQFN-10")
      (libsource (lib "eagle-import") (part "TS3USB30E"))
    )
    (comp (ref "U25")
      (value "TS3USB30E")
      (footprint "eagle-import:UQFN-10")
      (libsource (lib "eagle-import") (part "TS3USB30E"))
    )
    (comp (ref "C52")
      (value "100nF")
      (footprint "eagle-import:0603_CAP")
      (libsource (lib "eagle-import") (part "CAPACITOR0603_CAP"))
    )
    (comp (ref "C53")
      (value "100nF")
      (footprint "eagle-import:0603_CAP")
      (libsource (lib "eagle-import") (part "CAPACITOR0603_CAP"))
    )
    (comp (ref "C54")
      (value "100nF")
      (footprint "eagle-import:0603_CAP")
      (libsource (lib "eagle-import") (part "CAPACITOR0603_CAP"))
    )
    (comp (ref "C55")
      (value "100nF")
      (footprint "eagle-import:0603_CAP")
      (libsource (lib "eagle-import") (part "CAPACITOR0603_CAP"))
    )
    (comp (ref "C56")
      (value "100nF")
      (footprint "eagle-import:0603_CAP")
      (libsource (lib "eagle-import") (part "CAPACITOR0603_CAP"))
    )
    (comp (ref "C57")
      (value "100nF")
      (footprint "eagle-import:0603_CAP")
      (libsource (lib "eagle-import") (part "CAPACITOR0603_CAP"))
    )
    (comp (ref "R67")
      (value "10MΩ")
      (footprint "eagle-import:0603-RES")
      (libsource (lib "eagle-import") (part "RESISTOR0603_RES"))
    )
    (comp (ref "R68")
      (value "10MΩ")
      (footprint "eagle-import:0603-RES")
      (libsource (lib "eagle-import") (part "RESISTOR0603_RES"))
    )
    (comp (ref "R69")
      (value "10MΩ")
      (footprint "eagle-import:0603-RES")
      (libsource (lib "eagle-import") (part "RESISTOR0603_RES"))
    )
    (comp (ref "R70")
      (value "10MΩ")
      (footprint "eagle-import:0603-RES")
      (libsource (lib "eagle-import") (part "RESISTOR0603_RES"))
    )
    (comp (ref "R71")
      (value "10MΩ")
      (footprint "eagle-import:0603-RES")
      (libsource (lib "eagle-import") (part "RESISTOR0603_RES"))
    )
    (comp (ref "R72")
      (value "10MΩ")
      (footprint "eagle-import:0603-RES")
      (libsource (lib "eagle-import") (part "RESISTOR0603_RES"))
    )
    (comp (ref "R73")
      (value "10MΩ")
      (footprint "eagle-import:0603-RES")
      (libsource (lib "eagle-import") (part "RESISTOR0603_RES"))
    )
    (comp (ref "R74")
      (value "10MΩ")
      (footprint "eagle-import:0603-RES")
      (libsource (lib "eagle-import") (part "RESISTOR0603_RES"))
    )
    (comp (ref "R75")
      (value "10MΩ")
      (footprint "eagle-import:0603-RES")
      (libsource (lib "eagle-import") (part "RESISTOR0603_RES"))
    )
    (comp (ref "R76")
      (value "10MΩ")
      (footprint "eagle-import:0603-RES")
      (libsource (lib "eagle-import") (part "RESISTOR0603_RES"))
    )
    (comp (ref "R77")
      (value "10MΩ")
      (footprint "eagle-import:0603-RES")
      (libsource (lib "eagle-import") (part "RESISTOR0603_RES"))
    )
    (comp (ref "R78")
      (value "10MΩ")
      (footprint "eagle-import:0603-RES")
      (libsource (lib "eagle-import") (part "RESISTOR0603_RES"))
    )
    (comp (ref "R79")
      (value "10MΩ")
      (footprint "eagle-import:0603-RES")
      (libsource (lib "eagle-import") (part "RESISTOR0603_RES"))
    )
    (comp (ref "R80")
      (value "10MΩ")
      (footprint "eagle-import:0603-RES")
      (libsource (lib "eagle-import") (part "RESISTOR0603_RES"))
    )
    (comp (ref "R81")
      (value "10MΩ")
      (footprint "eagle-import:0603-RES")
      (libsource (lib "eagle-import") (part "RESISTOR0603_RES"))
    )
    (comp (ref "R82")
      (value "10MΩ")
      (footprint "eagle-import:0603-RES")
      (libsource (lib "eagle-import") (part "RESISTOR0603_RES"))
    )
    (comp (ref "R83")
      (value "10MΩ")
      (footprint "eagle-import:0603-RES")
      (libsource (lib "eagle-import") (part "RESISTOR0603_RES"))
    )
    (comp (ref "R84")
      (value "10MΩ")
      (footprint "eagle-import:0603-RES")
      (libsource (lib "eagle-import") (part "RESISTOR0603_RES"))
    )
    (comp (ref "U26")
      (value "MCP23008QFN")
      (footprint "eagle-import:QFN-20-4MM")
      (libsource (lib "eagle-import") (part "MCP23008QFN"))
    )
    (comp (ref "U27")
      (value "MCP23008QFN")
      (footprint "eagle-import:QFN-20-4MM")
      (libsource (lib "eagle-import") (part "MCP23008QFN"))
    )
    (comp (ref "U28")
      (value "MCP23008QFN")
      (footprint "eagle-import:QFN-20-4MM")
      (libsource (lib "eagle-import") (part "MCP23008QFN"))
    )
    (comp (ref "U29")
      (value "MCP23008QFN")
      (footprint "eagle-import:QFN-20-4MM")
      (libsource (lib "eagle-import") (part "MCP23008QFN"))
    )
    (comp (ref "U30")
      (value "MCP23008QFN")
      (footprint "eagle-import:QFN-20-4MM")
      (libsource (lib "eagle-import") (part "MCP23008QFN"))
    )
    (comp (ref "U31")
      (value "MCP23008QFN")
      (footprint "eagle-import:QFN-20-4MM")
      (libsource (lib "eagle-import") (part "MCP23008QFN"))
    )
    (comp (ref "C27")
      (value "100nF")
      (footprint "eagle-import:0603_CAP")
      (libsource (lib "eagle-import") (part "CAPACITOR0603_CAP"))
    )
    (comp (ref "C28")
      (value "100nF")
      (footprint "eagle-import:0603_CAP")
      (libsource (lib "eagle-import") (part "CAPACITOR0603_CAP"))
    )
    (comp (ref "C29")
      (value "100nF")
      (footprint "eagle-import:0603_CAP")
      (libsource (lib "eagle-import") (part "CAPACITOR0603_CAP"))
    )
    (comp (ref "C30")
      (value "100nF")
      (footprint "eagle-import:0603_CAP")
      (libsource (lib "eagle-import") (part "CAPACITOR0603_CAP"))
    )
    (comp (ref "C31")
      (value "100nF")
      (footprint "eagle-import:0603_CAP")
      (libsource (lib "eagle-import") (part "CAPACITOR0603_CAP"))
    )
    (comp (ref "C32")
      (value "100nF")
      (footprint "eagle-import:0603_CAP")
      (libsource (lib "eagle-import") (part "CAPACITOR0603_CAP"))
    )
    (comp (ref "C33")
      (value "100nF")
      (footprint "eagle-import:0603_CAP")
      (libsource (lib "eagle-import") (part "CAPACITOR0603_CAP"))
    )
    (comp (ref "C34")
      (value "100nF")
      (footprint "eagle-import:0603_CAP")
      (libsource (lib "eagle-import") (part "CAPACITOR0603_CAP"))
    )
    (comp (ref "C35")
      (value "100nF")
      (footprint "eagle-import:0603_CAP")
      (libsource (lib "eagle-import") (part "CAPACITOR0603_CAP"))
    )
    (comp (ref "C36")
      (value "100nF")
      (footprint "eagle-import:0603_CAP")
      (libsource (lib "eagle-import") (part "CAPACITOR0603_CAP"))
    )
    (comp (ref "C37")
      (value "100nF")
      (footprint "eagle-import:0603_CAP")
      (libsource (lib "eagle-import") (part "CAPACITOR0603_CAP"))
    )
    (comp (ref "C38")
      (value "100nF")
      (footprint "eagle-import:0603_CAP")
      (libsource (lib "eagle-import") (part "CAPACITOR0603_CAP"))
    )
    (comp (ref "C39")
      (value "100nF")
      (footprint "eagle-import:0603_CAP")
      (libsource (lib "eagle-import") (part "CAPACITOR0603_CAP"))
    )
    (comp (ref "C40")
      (value "100nF")
      (footprint "eagle-import:0603_CAP")
      (libsource (lib "eagle-import") (part "CAPACITOR0603_CAP"))
    )
    (comp (ref "C41")
      (value "100nF")
      (footprint "eagle-import:0603_CAP")
      (libsource (lib "eagle-import") (part "CAPACITOR0603_CAP"))
    )
    (comp (ref "C42")
      (value "100nF")
      (footprint "eagle-import:0603_CAP")
      (libsource (lib "eagle-import") (part "CAPACITOR0603_CAP"))
    )
    (comp (ref "C43")
      (value "100nF")
      (footprint "eagle-import:0603_CAP")
      (libsource (lib "eagle-import") (part "CAPACITOR0603_CAP"))
    )
    (comp (ref "C44")
      (value "100nF")
      (footprint "eagle-import:0603_CAP")
      (libsource (lib "eagle-import") (part "CAPACITOR0603_CAP"))
    )
    (comp (ref "C45")
      (value "100nF")
      (footprint "eagle-import:0603_CAP")
      (libsource (lib "eagle-import") (part "CAPACITOR0603_CAP"))
    )
    (comp (ref "C46")
      (value "100nF")
      (footprint "eagle-import:0603_CAP")
      (libsource (lib "eagle-import") (part "CAPACITOR0603_CAP"))
    )
    (comp (ref "C47")
      (value "100nF")
      (footprint "eagle-import:0603_CAP")
      (libsource (lib "eagle-import") (part "CAPACITOR0603_CAP"))
    )
    (comp (ref "C48")
      (value "100nF")
      (footprint "eagle-import:0603_CAP")
      (libsource (lib "eagle-import") (part "CAPACITOR0603_CAP"))
    )
    (comp (ref "C49")
      (value "100nF")
      (footprint "eagle-import:0603_CAP")
      (libsource (lib "eagle-import") (part "CAPACITOR0603_CAP"))
    )
    (comp (ref "C50")
      (value "100nF")
      (footprint "eagle-import:0603_CAP")
      (libsource (lib "eagle-import") (part "CAPACITOR0603_CAP"))
    )
    (comp (ref "U8")
      (value "SN74LVC2T45")
      (footprint "eagle-import:VFSOP-8")
      (libsource (lib "eagle-import") (part "SN74LVC2T45"))
    )
    (comp (ref "U9")
      (value "SN74LVC2T45")
      (footprint "eagle-import:VFSOP-8")
      (libsource (lib "eagle-import") (part "SN74LVC2T45"))
    )
    (comp (ref "U10")
      (value "SN74LVC2T45")
      (footprint "eagle-import:VFSOP-8")
      (libsource (lib "eagle-import") (part "SN74LVC2T45"))
    )
    (comp (ref "U11")
      (value "SN74LVC2T45")
      (footprint "eagle-import:VFSOP-8")
      (libsource (lib "eagle-import") (part "SN74LVC2T45"))
    )
    (comp (ref "U12")
      (value "SN74LVC2T45")
      (footprint "eagle-import:VFSOP-8")
      (libsource (lib "eagle-import") (part "SN74LVC2T45"))
    )
    (comp (ref "U13")
      (value "SN74LVC2T45")
      (footprint "eagle-import:VFSOP-8")
      (libsource (lib "eagle-import") (part "SN74LVC2T45"))
    )
    (comp (ref "U14")
      (value "SN74LVC2T45")
      (footprint "eagle-import:VFSOP-8")
      (libsource (lib "eagle-import") (part "SN74LVC2T45"))
    )
    (comp (ref "U15")
      (value "SN74LVC2T45")
      (footprint "eagle-import:VFSOP-8")
      (libsource (lib "eagle-import") (part "SN74LVC2T45"))
    )
    (comp (ref "U16")
      (value "SN74LVC2T45")
      (footprint "eagle-import:VFSOP-8")
      (libsource (lib "eagle-import") (part "SN74LVC2T45"))
    )
    (comp (ref "U17")
      (value "SN74LVC2T45")
      (footprint "eagle-import:VFSOP-8")
      (libsource (lib "eagle-import") (part "SN74LVC2T45"))
    )
    (comp (ref "U18")
      (value "SN74LVC2T45")
      (footprint "eagle-import:VFSOP-8")
      (libsource (lib "eagle-import") (part "SN74LVC2T45"))
    )
    (comp (ref "U19")
      (value "SN74LVC2T45")
      (footprint "eagle-import:VFSOP-8")
      (libsource (lib "eagle-import") (part "SN74LVC2T45"))
    )
    (comp (ref "C89")
      (value "100nF")
      (footprint "eagle-import:0603_CAP")
      (libsource (lib "eagle-import") (part "CAPACITOR0603_CAP"))
    )
    (comp (ref "SJ1")
      (value "SOLDERJUMPERNO")
      (footprint "eagle-import:SJ_2S-NO")
      (libsource (lib "eagle-import") (part "SOLDERJUMPERNO"))
    )
    (comp (ref "U34")
      (value "M24C01WMN")
      (footprint "eagle-import:SOIC-8")
      (libsource (lib "eagle-import") (part "M24C01WMN"))
    )
  )
  (nets
    (net (code "1") (name "CONT_MOD0_IN") (class "Default")
      (node (ref "J3") (pin "9") (pinfunction "MOD0_IN_9") (pintype "bidirectional"))
      (node (ref "U8") (pin "2") (pinfunction "A1_2") (pintype "bidirectional"))
    )
    (net (code "2") (name "CONT_MOD0_OUT") (class "Default")
      (node (ref "J3") (pin "10") (pinfunction "MOD0_OUT_10") (pintype "bidirectional"))
      (node (ref "U14") (pin "2") (pinfunction "A1_2") (pintype "bidirectional"))
    )
    (net (code "3") (name "CONT_MOD1_IN") (class "Default")
      (node (ref "J3") (pin "11") (pinfunction "MOD1_IN_11") (pintype "bidirectional"))
      (node (ref "U9") (pin "2") (pinfunction "A1_2") (pintype "bidirectional"))
    )
    (net (code "4") (name "CONT_MOD1_OUT") (class "Default")
      (node (ref "J3") (pin "12") (pinfunction "MOD1_OUT_12") (pintype "bidirectional"))
      (node (ref "U15") (pin "2") (pinfunction "A1_2") (pintype "bidirectional"))
    )
    (net (code "5") (name "CONT_MOD2_IN") (class "Default")
      (node (ref "J3") (pin "13") (pinfunction "MOD2_IN_13") (pintype "bidirectional"))
      (node (ref "U10") (pin "2") (pinfunction "A1_2") (pintype "bidirectional"))
    )
    (net (code "6") (name "CONT_MOD2_OUT") (class "Default")
      (node (ref "J3") (pin "14") (pinfunction "MOD2_OUT_14") (pintype "bidirectional"))
      (node (ref "U16") (pin "2") (pinfunction "A1_2") (pintype "bidirectional"))
    )
    (net (code "7") (name "CONT_MOD5_IN") (class "Default")
      (node (ref "J3") (pin "15") (pinfunction "MOD5_IN_15") (pintype "bidirectional"))
      (node (ref "U11") (pin "2") (pinfunction "A1_2") (pintype "bidirectional"))
    )
    (net (code "8") (name "CONT_MOD5_OUT") (class "Default")
      (node (ref "J3") (pin "16") (pinfunction "MOD5_OUT_16") (pintype "bidirectional"))
      (node (ref "U17") (pin "2") (pinfunction "A1_2") (pintype "bidirectional"))
    )
    (net (code "9") (name "CONT_MOD6_IN") (class "Default")
      (node (ref "J3") (pin "17") (pinfunction "MOD6_IN_17") (pintype "bidirectional"))
      (node (ref "U12") (pin "2") (pinfunction "A1_2") (pintype "bidirectional"))
    )
    (net (code "10") (name "CONT_MOD6_OUT") (class "Default")
      (node (ref "J3") (pin "18") (pinfunction "MOD6_OUT_18") (pintype "bidirectional"))
      (node (ref "U18") (pin "2") (pinfunction "A1_2") (pintype "bidirectional"))
    )
    (net (code "11") (name "CONT_MOD7_IN") (class "Default")
      (node (ref "J3") (pin "19") (pinfunction "MOD7_IN_19") (pintype "bidirectional"))
      (node (ref "U13") (pin "2") (pinfunction "A1_2") (pintype "bidirectional"))
    )
    (net (code "12") (name "CONT_MOD7_OUT") (class "Default")
      (node (ref "J3") (pin "20") (pinfunction "MOD7_OUT_20") (pintype "bidirectional"))
      (node (ref "U19") (pin "2") (pinfunction "A1_2") (pintype "bidirectional"))
    )
    (net (code "13") (name "CONT_USB+") (class "Default")
      (node (ref "J3") (pin "27") (pinfunction "USB_D+_27") (pintype "bidirectional"))
      (node (ref "R25") (pin "1") (pinfunction "1_1") (pintype "passive"))
      (node (ref "U1") (pin "3") (pinfunction "DP0_3") (pintype "bidirectional"))
    )
    (net (code "14") (name "CONT_USB-") (class "Default")
      (node (ref "J3") (pin "28") (pinfunction "USB_D-_28") (pintype "bidirectional"))
      (node (ref "U1") (pin "4") (pinfunction "DM0_4") (pintype "bidirectional"))
    )
    (net (code "15") (name "GND") (class "Default")
      (node (ref "C1") (pin "1") (pinfunction "1_1") (pintype "bidirectional"))
      (node (ref "C10") (pin "2") (pinfunction "2_2") (pintype "bidirectional"))
      (node (ref "C100") (pin "2") (pinfunction "2_2") (pintype "passive"))
      (node (ref "C101") (pin "2") (pinfunction "2_2") (pintype "passive"))
      (node (ref "C102") (pin "2") (pinfunction "2_2") (pintype "passive"))
      (node (ref "C11") (pin "2") (pinfunction "2_2") (pintype "bidirectional"))
      (node (ref "C12") (pin "2") (pinfunction "2_2") (pintype "bidirectional"))
      (node (ref "C13") (pin "2") (pinfunction "2_2") (pintype "bidirectional"))
      (node (ref "C14") (pin "2") (pinfunction "2_2") (pintype "bidirectional"))
      (node (ref "C15") (pin "2") (pinfunction "2_2") (pintype "bidirectional"))
      (node (ref "C16") (pin "2") (pinfunction "2_2") (pintype "bidirectional"))
      (node (ref "C17") (pin "2") (pinfunction "2_2") (pintype "bidirectional"))
      (node (ref "C18") (pin "2") (pinfunction "2_2") (pintype "bidirectional"))
      (node (ref "C19") (pin "2") (pinfunction "2_2") (pintype "bidirectional"))
      (node (ref "C2") (pin "1") (pinfunction "1_1") (pintype "bidirectional"))
      (node (ref "C20") (pin "2") (pinfunction "2_2") (pintype "bidirectional"))
      (node (ref "C21") (pin "2") (pinfunction "2_2") (pintype "bidirectional"))
      (node (ref "C22") (pin "2") (pinfunction "2_2") (pintype "bidirectional"))
      (node (ref "C23") (pin "2") (pinfunction "2_2") (pintype "bidirectional"))
      (node (ref "C24") (pin "2") (pinfunction "2_2") (pintype "bidirectional"))
      (node (ref "C25") (pin "2") (pinfunction "2_2") (pintype "bidirectional"))
      (node (ref "C26") (pin "2") (pinfunction "2_2") (pintype "bidirectional"))
      (node (ref "C27") (pin "2") (pinfunction "2_2") (pintype "bidirectional"))
      (node (ref "C28") (pin "2") (pinfunction "2_2") (pintype "bidirectional"))
      (node (ref "C29") (pin "2") (pinfunction "2_2") (pintype "bidirectional"))
      (node (ref "C3") (pin "2") (pinfunction "2_2") (pintype "bidirectional"))
      (node (ref "C30") (pin "2") (pinfunction "2_2") (pintype "bidirectional"))
      (node (ref "C31") (pin "2") (pinfunction "2_2") (pintype "bidirectional"))
      (node (ref "C32") (pin "2") (pinfunction "2_2") (pintype "bidirectional"))
      (node (ref "C33") (pin "2") (pinfunction "2_2") (pintype "bidirectional"))
      (node (ref "C34") (pin "2") (pinfunction "2_2") (pintype "bidirectional"))
      (node (ref "C35") (pin "2") (pinfunction "2_2") (pintype "bidirectional"))
      (node (ref "C36") (pin "2") (pinfunction "2_2") (pintype "bidirectional"))
      (node (ref "C37") (pin "2") (pinfunction "2_2") (pintype "bidirectional"))
      (node (ref "C38") (pin "2") (pinfunction "2_2") (pintype "bidirectional"))
      (node (ref "C39") (pin "2") (pinfunction "2_2") (pintype "bidirectional"))
      (node (ref "C4") (pin "2") (pinfunction "2_2") (pintype "bidirectional"))
      (node (ref "C40") (pin "2") (pinfunction "2_2") (pintype "bidirectional"))
      (node (ref "C41") (pin "2") (pinfunction "2_2") (pintype "bidirectional"))
      (node (ref "C42") (pin "2") (pinfunction "2_2") (pintype "bidirectional"))
      (node (ref "C43") (pin "2") (pinfunction "2_2") (pintype "bidirectional"))
      (node (ref "C44") (pin "2") (pinfunction "2_2") (pintype "bidirectional"))
      (node (ref "C45") (pin "2") (pinfunction "2_2") (pintype "bidirectional"))
      (node (ref "C46") (pin "2") (pinfunction "2_2") (pintype "bidirectional"))
      (node (ref "C47") (pin "2") (pinfunction "2_2") (pintype "bidirectional"))
      (node (ref "C48") (pin "2") (pinfunction "2_2") (pintype "bidirectional"))
      (node (ref "C49") (pin "2") (pinfunction "2_2") (pintype "bidirectional"))
      (node (ref "C5") (pin "2") (pinfunction "2_2") (pintype "bidirectional"))
      (node (ref "C50") (pin "2") (pinfunction "2_2") (pintype "bidirectional"))
      (node (ref "C51") (pin "1") (pinfunction "1_1") (pintype "bidirectional"))
      (node (ref "C52") (pin "2") (pinfunction "2_2") (pintype "bidirectional"))
      (node (ref "C53") (pin "2") (pinfunction "2_2") (pintype "bidirectional"))
      (node (ref "C54") (pin "2") (pinfunction "2_2") (pintype "bidirectional"))
      (node (ref "C55") (pin "2") (pinfunction "2_2") (pintype "bidirectional"))
      (node (ref "C56") (pin "2") (pinfunction "2_2") (pintype "bidirectional"))
      (node (ref "C57") (pin "2") (pinfunction "2_2") (pintype "bidirectional"))
      (node (ref "C58") (pin "2") (pinfunction "2_2") (pintype "bidirectional"))
      (node (ref "C59") (pin "2") (pinfunction "2_2") (pintype "bidirectional"))
      (node (ref "C6") (pin "2") (pinfunction "2_2") (pintype "bidirectional"))
      (node (ref "C60") (pin "2") (pinfunction "2_2") (pintype "bidirectional"))
      (node (ref "C61") (pin "2") (pinfunction "2_2") (pintype "bidirectional"))
      (node (ref "C62") (pin "2") (pinfunction "2_2") (pintype "bidirectional"))
      (node (ref "C63") (pin "2") (pinfunction "2_2") (pintype "bidirectional"))
      (node (ref "C64") (pin "2") (pinfunction "2_2") (pintype "bidirectional"))
      (node (ref "C65") (pin "2") (pinfunction "2_2") (pintype "bidirectional"))
      (node (ref "C66") (pin "2") (pinfunction "2_2") (pintype "bidirectional"))
      (node (ref "C67") (pin "2") (pinfunction "2_2") (pintype "bidirectional"))
      (node (ref "C68") (pin "2") (pinfunction "2_2") (pintype "bidirectional"))
      (node (ref "C69") (pin "2") (pinfunction "2_2") (pintype "bidirectional"))
      (node (ref "C7") (pin "2") (pinfunction "2_2") (pintype "bidirectional"))
      (node (ref "C70") (pin "2") (pinfunction "2_2") (pintype "bidirectional"))
      (node (ref "C71") (pin "2") (pinfunction "2_2") (pintype "bidirectional"))
      (node (ref "C72") (pin "2") (pinfunction "2_2") (pintype "bidirectional"))
      (node (ref "C73") (pin "2") (pinfunction "2_2") (pintype "bidirectional"))
      (node (ref "C74") (pin "2") (pinfunction "2_2") (pintype "bidirectional"))
      (node (ref "C75") (pin "2") (pinfunction "2_2") (pintype "bidirectional"))
      (node (ref "C76") (pin "1") (pinfunction "1_1") (pintype "bidirectional"))
      (node (ref "C77") (pin "1") (pinfunction "1_1") (pintype "bidirectional"))
      (node (ref "C78") (pin "1") (pinfunction "1_1") (pintype "bidirectional"))
      (node (ref "C79") (pin "1") (pinfunction "1_1") (pintype "bidirectional"))
      (node (ref "C8") (pin "2") (pinfunction "2_2") (pintype "bidirectional"))
      (node (ref "C80") (pin "1") (pinfunction "1_1") (pintype "bidirectional"))
      (node (ref "C81") (pin "1") (pinfunction "1_1") (pintype "bidirectional"))
      (node (ref "C82") (pin "2") (pinfunction "2_2") (pintype "bidirectional"))
      (node (ref "C83") (pin "2") (pinfunction "2_2") (pintype "bidirectional"))
      (node (ref "C84") (pin "2") (pinfunction "2_2") (pintype "bidirectional"))
      (node (ref "C85") (pin "2") (pinfunction "2_2") (pintype "bidirectional"))
      (node (ref "C86") (pin "2") (pinfunction "2_2") (pintype "bidirectional"))
      (node (ref "C87") (pin "2") (pinfunction "2_2") (pintype "bidirectional"))
      (node (ref "C88") (pin "2") (pinfunction "2_2") (pintype "bidirectional"))
      (node (ref "C89") (pin "2") (pinfunction "2_2") (pintype "bidirectional"))
      (node (ref "C9") (pin "2") (pinfunction "2_2") (pintype "bidirectional"))
      (node (ref "C90") (pin "2") (pinfunction "2_2") (pintype "bidirectional"))
      (node (ref "C91") (pin "2") (pinfunction "2_2") (pintype "bidirectional"))
      (node (ref "C92") (pin "2") (pinfunction "2_2") (pintype "bidirectional"))
      (node (ref "C93") (pin "2") (pinfunction "2_2") (pintype "bidirectional"))
      (node (ref "C94") (pin "2") (pinfunction "2_2") (pintype "bidirectional"))
      (node (ref "C95") (pin "2") (pinfunction "2_2") (pintype "bidirectional"))
      (node (ref "C96") (pin "1") (pinfunction "1_1") (pintype "bidirectional"))
      (node (ref "C97") (pin "2") (pinfunction "2_2") (pintype "passive"))
      (node (ref "C98") (pin "2") (pinfunction "2_2") (pintype "passive"))
      (node (ref "C99") (pin "2") (pinfunction "2_2") (pintype "passive"))
      (node (ref "D1") (pin "1") (pinfunction "GND_1") (pintype "bidirectional"))
      (node (ref "D1") (pin "3") (pinfunction "GND_3") (pintype "bidirectional"))
      (node (ref "D1") (pin "5") (pinfunction "GND_5") (pintype "bidirectional"))
      (node (ref "D1") (pin "7") (pinfunction "GND_7") (pintype "bidirectional"))
      (node (ref "D2") (pin "1") (pinfunction "GND_1") (pintype "bidirectional"))
      (node (ref "D2") (pin "3") (pinfunction "GND_3") (pintype "bidirectional"))
      (node (ref "D2") (pin "5") (pinfunction "GND_5") (pintype "bidirectional"))
      (node (ref "D2") (pin "7") (pinfunction "GND_7") (pintype "bidirectional"))
      (node (ref "D3") (pin "1") (pinfunction "GND_1") (pintype "bidirectional"))
      (node (ref "D3") (pin "3") (pinfunction "GND_3") (pintype "bidirectional"))
      (node (ref "D3") (pin "5") (pinfunction "GND_5") (pintype "bidirectional"))
      (node (ref "D3") (pin "7") (pinfunction "GND_7") (pintype "bidirectional"))
      (node (ref "D4") (pin "1") (pinfunction "GND_1") (pintype "bidirectional"))
      (node (ref "D4") (pin "3") (pinfunction "GND_3") (pintype "bidirectional"))
      (node (ref "D4") (pin "5") (pinfunction "GND_5") (pintype "bidirectional"))
      (node (ref "D4") (pin "7") (pinfunction "GND_7") (pintype "bidirectional"))
      (node (ref "H21") (pin "B#4") (pinfunction "MOUNT_B#4") (pintype "passive"))
      (node (ref "H22") (pin "B#4") (pinfunction "MOUNT_B#4") (pintype "passive"))
      (node (ref "H23") (pin "B#4") (pinfunction "MOUNT_B#4") (pintype "passive"))
      (node (ref "H24") (pin "B#4") (pinfunction "MOUNT_B#4") (pintype "passive"))
      (node (ref "H25") (pin "B#4") (pinfunction "MOUNT_B#4") (pintype "passive"))
      (node (ref "H26") (pin "B#4") (pinfunction "MOUNT_B#4") (pintype "passive"))
      (node (ref "H27") (pin "B#4") (pinfunction "MOUNT_B#4") (pintype "passive"))
      (node (ref "H28") (pin "B#4") (pinfunction "MOUNT_B#4") (pintype "passive"))
      (node (ref "H29") (pin "B#4") (pinfunction "MOUNT_B#4") (pintype "passive"))
      (node (ref "H30") (pin "B#4") (pinfunction "MOUNT_B#4") (pintype "passive"))
      (node (ref "H31") (pin "B#4") (pinfunction "MOUNT_B#4") (pintype "passive"))
      (node (ref "H32") (pin "B#4") (pinfunction "MOUNT_B#4") (pintype "passive"))
      (node (ref "H33") (pin "B#4") (pinfunction "MOUNT_B#4") (pintype "passive"))
      (node (ref "H34") (pin "B#4") (pinfunction "MOUNT_B#4") (pintype "passive"))
      (node (ref "H35") (pin "B#4") (pinfunction "MOUNT_B#4") (pintype "passive"))
      (node (ref "H36") (pin "B#4") (pinfunction "MOUNT_B#4") (pintype "passive"))
      (node (ref "H37") (pin "B#4") (pinfunction "MOUNT_B#4") (pintype "passive"))
      (node (ref "H38") (pin "B#4") (pinfunction "MOUNT_B#4") (pintype "passive"))
      (node (ref "H39") (pin "B#4") (pinfunction "MOUNT_B#4") (pintype "passive"))
      (node (ref "H40") (pin "B#4") (pinfunction "MOUNT_B#4") (pintype "passive"))
      (node (ref "J0") (pin "1") (pinfunction "GND_1") (pintype "bidirectional"))
      (node (ref "J0") (pin "14") (pinfunction "GND_14") (pintype "bidirectional"))
      (node (ref "J0") (pin "MNT1") (pinfunction "GND_MNT1") (pintype "bidirectional"))
      (node (ref "J0") (pin "MNT2") (pinfunction "GND_MNT2") (pintype "bidirectional"))
      (node (ref "J0") (pin "MNT3") (pinfunction "GND_MNT3") (pintype "bidirectional"))
      (node (ref "J0") (pin "MNT4") (pinfunction "GND_MNT4") (pintype "bidirectional"))
      (node (ref "J1") (pin "1") (pinfunction "GND_1") (pintype "bidirectional"))
      (node (ref "J1") (pin "14") (pinfunction "GND_14") (pintype "bidirectional"))
      (node (ref "J1") (pin "MNT1") (pinfunction "GND_MNT1") (pintype "bidirectional"))
      (node (ref "J1") (pin "MNT2") (pinfunction "GND_MNT2") (pintype "bidirectional"))
      (node (ref "J1") (pin "MNT3") (pinfunction "GND_MNT3") (pintype "bidirectional"))
      (node (ref "J1") (pin "MNT4") (pinfunction "GND_MNT4") (pintype "bidirectional"))
      (node (ref "J2") (pin "1") (pinfunction "GND_1") (pintype "bidirectional"))
      (node (ref "J2") (pin "14") (pinfunction "GND_14") (pintype "bidirectional"))
      (node (ref "J2") (pin "MNT1") (pinfunction "GND_MNT1") (pintype "bidirectional"))
      (node (ref "J2") (pin "MNT2") (pinfunction "GND_MNT2") (pintype "bidirectional"))
      (node (ref "J2") (pin "MNT3") (pinfunction "GND_MNT3") (pintype "bidirectional"))
      (node (ref "J2") (pin "MNT4") (pinfunction "GND_MNT4") (pintype "bidirectional"))
      (node (ref "J3") (pin "1") (pinfunction "GND_1") (pintype "bidirectional"))
      (node (ref "J3") (pin "21") (pinfunction "GND_21") (pintype "bidirectional"))
      (node (ref "J3") (pin "MNT1") (pinfunction "GND_MNT1") (pintype "bidirectional"))
      (node (ref "J3") (pin "MNT2") (pinfunction "GND_MNT2") (pintype "bidirectional"))
      (node (ref "J3") (pin "MNT3") (pinfunction "GND_MNT3") (pintype "bidirectional"))
      (node (ref "J3") (pin "MNT4") (pinfunction "GND_MNT4") (pintype "bidirectional"))
      (node (ref "J4") (pin "1") (pinfunction "GND_1") (pintype "power_in"))
      (node (ref "J4") (pin "MNT1") (pinfunction "GND_MNT1") (pintype "power_in"))
      (node (ref "J4") (pin "MNT2") (pinfunction "GND_MNT2") (pintype "power_in"))
      (node (ref "J4") (pin "MNT3") (pinfunction "GND_MNT3") (pintype "power_in"))
      (node (ref "J4") (pin "MNT4") (pinfunction "GND_MNT4") (pintype "power_in"))
      (node (ref "J5") (pin "1") (pinfunction "GND_1") (pintype "bidirectional"))
      (node (ref "J5") (pin "14") (pinfunction "GND_14") (pintype "bidirectional"))
      (node (ref "J5") (pin "MNT1") (pinfunction "GND_MNT1") (pintype "bidirectional"))
      (node (ref "J5") (pin "MNT2") (pinfunction "GND_MNT2") (pintype "bidirectional"))
      (node (ref "J5") (pin "MNT3") (pinfunction "GND_MNT3") (pintype "bidirectional"))
      (node (ref "J5") (pin "MNT4") (pinfunction "GND_MNT4") (pintype "bidirectional"))
      (node (ref "J6") (pin "1") (pinfunction "GND_1") (pintype "bidirectional"))
      (node (ref "J6") (pin "14") (pinfunction "GND_14") (pintype "bidirectional"))
      (node (ref "J6") (pin "MNT1") (pinfunction "GND_MNT1") (pintype "bidirectional"))
      (node (ref "J6") (pin "MNT2") (pinfunction "GND_MNT2") (pintype "bidirectional"))
      (node (ref "J6") (pin "MNT3") (pinfunction "GND_MNT3") (pintype "bidirectional"))
      (node (ref "J6") (pin "MNT4") (pinfunction "GND_MNT4") (pintype "bidirectional"))
      (node (ref "J7") (pin "1") (pinfunction "GND_1") (pintype "bidirectional"))
      (node (ref "J7") (pin "14") (pinfunction "GND_14") (pintype "bidirectional"))
      (node (ref "J7") (pin "MNT1") (pinfunction "GND_MNT1") (pintype "bidirectional"))
      (node (ref "J7") (pin "MNT2") (pinfunction "GND_MNT2") (pintype "bidirectional"))
      (node (ref "J7") (pin "MNT3") (pinfunction "GND_MNT3") (pintype "bidirectional"))
      (node (ref "J7") (pin "MNT4") (pinfunction "GND_MNT4") (pintype "bidirectional"))
      (node (ref "LED1001") (pin "C") (pinfunction "CATHODE_C") (pintype "bidirectional"))
      (node (ref "LED1002") (pin "C") (pinfunction "CATHODE_C") (pintype "bidirectional"))
      (node (ref "LED1003") (pin "C") (pinfunction "CATHODE_C") (pintype "bidirectional"))
      (node (ref "LED1007") (pin "C") (pinfunction "CATHODE_C") (pintype "bidirectional"))
      (node (ref "LED1008") (pin "C") (pinfunction "CATHODE_C") (pintype "bidirectional"))
      (node (ref "LED1009") (pin "C") (pinfunction "CATHODE_C") (pintype "bidirectional"))
      (node (ref "LED1013") (pin "C") (pinfunction "CATHODE_C") (pintype "bidirectional"))
      (node (ref "LED1014") (pin "C") (pinfunction "CATHODE_C") (pintype "bidirectional"))
      (node (ref "LED1015") (pin "C") (pinfunction "CATHODE_C") (pintype "bidirectional"))
      (node (ref "R1004") (pin "1") (pinfunction "1_1") (pintype "passive"))
      (node (ref "R1005") (pin "1") (pinfunction "1_1") (pintype "passive"))
      (node (ref "R1006") (pin "1") (pinfunction "1_1") (pintype "passive"))
      (node (ref "R1010") (pin "1") (pinfunction "1_1") (pintype "passive"))
      (node (ref "R1011") (pin "1") (pinfunction "1_1") (pintype "passive"))
      (node (ref "R1012") (pin "1") (pinfunction "1_1") (pintype "passive"))
      (node (ref "R1016") (pin "1") (pinfunction "1_1") (pintype "passive"))
      (node (ref "R1017") (pin "1") (pinfunction "1_1") (pintype "passive"))
      (node (ref "R1018") (pin "1") (pinfunction "1_1") (pintype "passive"))
      (node (ref "R13") (pin "2") (pinfunction "2_2") (pintype "passive"))
      (node (ref "R14") (pin "2") (pinfunction "2_2") (pintype "passive"))
      (node (ref "R15") (pin "2") (pinfunction "2_2") (pintype "passive"))
      (node (ref "R16") (pin "2") (pinfunction "2_2") (pintype "passive"))
      (node (ref "R17") (pin "2") (pinfunction "2_2") (pintype "passive"))
      (node (ref "R18") (pin "2") (pinfunction "2_2") (pintype "passive"))
      (node (ref "R19") (pin "2") (pinfunction "2_2") (pintype "passive"))
      (node (ref "R20") (pin "2") (pinfunction "2_2") (pintype "passive"))
      (node (ref "R21") (pin "2") (pinfunction "2_2") (pintype "passive"))
      (node (ref "R22") (pin "2") (pinfunction "2_2") (pintype "passive"))
      (node (ref "R23") (pin "2") (pinfunction "2_2") (pintype "passive"))
      (node (ref "R24") (pin "2") (pinfunction "2_2") (pintype "passive"))
      (node (ref "R53") (pin "1") (pinfunction "1_1") (pintype "passive"))
      (node (ref "R54") (pin "1") (pinfunction "1_1") (pintype "passive"))
      (node (ref "R55") (pin "1") (pinfunction "1_1") (pintype "passive"))
      (node (ref "R56") (pin "1") (pinfunction "1_1") (pintype "passive"))
      (node (ref "R57") (pin "1") (pinfunction "1_1") (pintype "passive"))
      (node (ref "R58") (pin "1") (pinfunction "1_1") (pintype "passive"))
      (node (ref "R59") (pin "1") (pinfunction "1_1") (pintype "passive"))
      (node (ref "R60") (pin "1") (pinfunction "1_1") (pintype "passive"))
      (node (ref "R61") (pin "1") (pinfunction "1_1") (pintype "passive"))
      (node (ref "R62") (pin "1") (pinfunction "1_1") (pintype "passive"))
      (node (ref "R63") (pin "1") (pinfunction "1_1") (pintype "passive"))
      (node (ref "R64") (pin "1") (pinfunction "1_1") (pintype "passive"))
      (node (ref "R65") (pin "2") (pinfunction "2_2") (pintype "passive"))
      (node (ref "R66") (pin "2") (pinfunction "2_2") (pintype "passive"))
      (node (ref "R67") (pin "1") (pinfunction "1_1") (pintype "passive"))
      (node (ref "R68") (pin "1") (pinfunction "1_1") (pintype "passive"))
      (node (ref "R69") (pin "1") (pinfunction "1_1") (pintype "passive"))
      (node (ref "R70") (pin "1") (pinfunction "1_1") (pintype "passive"))
      (node (ref "R71") (pin "1") (pinfunction "1_1") (pintype "passive"))
      (node (ref "R72") (pin "1") (pinfunction "1_1") (pintype "passive"))
      (node (ref "R73") (pin "1") (pinfunction "1_1") (pintype "passive"))
      (node (ref "R74") (pin "1") (pinfunction "1_1") (pintype "passive"))
      (node (ref "R75") (pin "1") (pinfunction "1_1") (pintype "passive"))
      (node (ref "R76") (pin "1") (pinfunction "1_1") (pintype "passive"))
      (node (ref "R77") (pin "1") (pinfunction "1_1") (pintype "passive"))
      (node (ref "R78") (pin "1") (pinfunction "1_1") (pintype "passive"))
      (node (ref "R79") (pin "1") (pinfunction "1_1") (pintype "passive"))
      (node (ref "R80") (pin "1") (pinfunction "1_1") (pintype "passive"))
      (node (ref "R81") (pin "1") (pinfunction "1_1") (pintype "passive"))
      (node (ref "R82") (pin "1") (pinfunction "1_1") (pintype "passive"))
      (node (ref "R83") (pin "1") (pinfunction "1_1") (pintype "passive"))
      (node (ref "R84") (pin "1") (pinfunction "1_1") (pintype "passive"))
      (node (ref "S1") (pin "2") (pinfunction "GND_2") (pintype "bidirectional"))
      (node (ref "S1") (pin "PAD") (pinfunction "GND_PAD") (pintype "bidirectional"))
      (node (ref "S10") (pin "2") (pinfunction "GND_2") (pintype "bidirectional"))
      (node (ref "S11") (pin "2") (pinfunction "GND_2") (pintype "bidirectional"))
      (node (ref "S12") (pin "2") (pinfunction "GND_2") (pintype "bidirectional"))
      (node (ref "S13") (pin "1") (pinfunction "GND_1") (pintype "bidirectional"))
      (node (ref "S13") (pin "PAD") (pinfunction "GND_PAD") (pintype "bidirectional"))
      (node (ref "S14") (pin "1") (pinfunction "GND_1") (pintype "bidirectional"))
      (node (ref "S14") (pin "PAD") (pinfunction "GND_PAD") (pintype "bidirectional"))
      (node (ref "S15") (pin "1") (pinfunction "GND_1") (pintype "bidirectional"))
      (node (ref "S15") (pin "PAD") (pinfunction "GND_PAD") (pintype "bidirectional"))
      (node (ref "S16") (pin "1") (pinfunction "GND_1") (pintype "bidirectional"))
      (node (ref "S16") (pin "PAD") (pinfunction "GND_PAD") (pintype "bidirectional"))
      (node (ref "S17") (pin "1") (pinfunction "GND_1") (pintype "bidirectional"))
      (node (ref "S17") (pin "PAD") (pinfunction "GND_PAD") (pintype "bidirectional"))
      (node (ref "S18") (pin "1") (pinfunction "GND_1") (pintype "bidirectional"))
      (node (ref "S18") (pin "PAD") (pinfunction "GND_PAD") (pintype "bidirectional"))
      (node (ref "S2") (pin "2") (pinfunction "GND_2") (pintype "bidirectional"))
      (node (ref "S2") (pin "PAD") (pinfunction "GND_PAD") (pintype "bidirectional"))
      (node (ref "S3") (pin "2") (pinfunction "GND_2") (pintype "bidirectional"))
      (node (ref "S3") (pin "PAD") (pinfunction "GND_PAD") (pintype "bidirectional"))
      (node (ref "S4") (pin "2") (pinfunction "GND_2") (pintype "bidirectional"))
      (node (ref "S4") (pin "PAD") (pinfunction "GND_PAD") (pintype "bidirectional"))
      (node (ref "S5") (pin "2") (pinfunction "GND_2") (pintype "bidirectional"))
      (node (ref "S5") (pin "PAD") (pinfunction "GND_PAD") (pintype "bidirectional"))
      (node (ref "S6") (pin "2") (pinfunction "GND_2") (pintype "bidirectional"))
      (node (ref "S6") (pin "PAD") (pinfunction "GND_PAD") (pintype "bidirectional"))
      (node (ref "S7") (pin "2") (pinfunction "GND_2") (pintype "bidirectional"))
      (node (ref "S8") (pin "2") (pinfunction "GND_2") (pintype "bidirectional"))
      (node (ref "S9") (pin "2") (pinfunction "GND_2") (pintype "bidirectional"))
      (node (ref "TP11") (pin "TESTPOINT") (pinfunction "TESTPOINT_TESTPOINT") (pintype "bidirectional"))
      (node (ref "TP25") (pin "TESTPOINT") (pinfunction "TESTPOINT_TESTPOINT") (pintype "bidirectional"))
      (node (ref "TP26") (pin "TESTPOINT") (pinfunction "TESTPOINT_TESTPOINT") (pintype "bidirectional"))
      (node (ref "TP27") (pin "TESTPOINT") (pinfunction "TESTPOINT_TESTPOINT") (pintype "bidirectional"))
      (node (ref "TP4") (pin "TESTPOINT") (pinfunction "TESTPOINT_TESTPOINT") (pintype "bidirectional"))
      (node (ref "TP7") (pin "TESTPOINT") (pinfunction "TESTPOINT_TESTPOINT") (pintype "bidirectional"))
      (node (ref "U1") (pin "10") (pinfunction "~{BUSPWR}_10") (pintype "bidirectional"))
      (node (ref "U1") (pin "24") (pinfunction "GND_24") (pintype "bidirectional"))
      (node (ref "U1") (pin "43") (pinfunction "GND_43") (pintype "bidirectional"))
      (node (ref "U1") (pin "48") (pinfunction "MODE_48") (pintype "bidirectional"))
      (node (ref "U1") (pin "5") (pinfunction "GND_5") (pintype "bidirectional"))
      (node (ref "U10") (pin "4") (pinfunction "GND_4") (pintype "bidirectional"))
      (node (ref "U11") (pin "4") (pinfunction "GND_4") (pintype "bidirectional"))
      (node (ref "U12") (pin "4") (pinfunction "GND_4") (pintype "bidirectional"))
      (node (ref "U13") (pin "4") (pinfunction "GND_4") (pintype "bidirectional"))
      (node (ref "U14") (pin "4") (pinfunction "GND_4") (pintype "bidirectional"))
      (node (ref "U14") (pin "5") (pinfunction "DIR_5") (pintype "bidirectional"))
      (node (ref "U15") (pin "4") (pinfunction "GND_4") (pintype "bidirectional"))
      (node (ref "U15") (pin "5") (pinfunction "DIR_5") (pintype "bidirectional"))
      (node (ref "U16") (pin "4") (pinfunction "GND_4") (pintype "bidirectional"))
      (node (ref "U16") (pin "5") (pinfunction "DIR_5") (pintype "bidirectional"))
      (node (ref "U17") (pin "4") (pinfunction "GND_4") (pintype "bidirectional"))
      (node (ref "U17") (pin "5") (pinfunction "DIR_5") (pintype "bidirectional"))
      (node (ref "U18") (pin "4") (pinfunction "GND_4") (pintype "bidirectional"))
      (node (ref "U19") (pin "4") (pinfunction "GND_4") (pintype "bidirectional"))
      (node (ref "U19") (pin "5") (pinfunction "DIR_5") (pintype "bidirectional"))
      (node (ref "U2") (pin "4") (pinfunction "GND_4") (pintype "bidirectional"))
      (node (ref "U20") (pin "10") (pinfunction "S_10") (pintype "bidirectional"))
      (node (ref "U20") (pin "4") (pinfunction "GND_4") (pintype "bidirectional"))
      (node (ref "U21") (pin "10") (pinfunction "S_10") (pintype "bidirectional"))
      (node (ref "U21") (pin "4") (pinfunction "GND_4") (pintype "bidirectional"))
      (node (ref "U22") (pin "10") (pinfunction "S_10") (pintype "bidirectional"))
      (node (ref "U22") (pin "4") (pinfunction "GND_4") (pintype "bidirectional"))
      (node (ref "U23") (pin "10") (pinfunction "S_10") (pintype "bidirectional"))
      (node (ref "U23") (pin "4") (pinfunction "GND_4") (pintype "bidirectional"))
      (node (ref "U24") (pin "10") (pinfunction "S_10") (pintype "bidirectional"))
      (node (ref "U24") (pin "4") (pinfunction "GND_4") (pintype "bidirectional"))
      (node (ref "U25") (pin "10") (pinfunction "S_10") (pintype "bidirectional"))
      (node (ref "U25") (pin "4") (pinfunction "GND_4") (pintype "bidirectional"))
      (node (ref "U26") (pin "1") (pinfunction "A2_1") (pintype "bidirectional"))
      (node (ref "U26") (pin "17") (pinfunction "GND_17") (pintype "bidirectional"))
      (node (ref "U26") (pin "2") (pinfunction "A1_2") (pintype "bidirectional"))
      (node (ref "U26") (pin "3") (pinfunction "A0_3") (pintype "bidirectional"))
      (node (ref "U26") (pin "GND") (pinfunction "GND_GND") (pintype "bidirectional"))
      (node (ref "U27") (pin "1") (pinfunction "A2_1") (pintype "bidirectional"))
      (node (ref "U27") (pin "17") (pinfunction "GND_17") (pintype "bidirectional"))
      (node (ref "U27") (pin "2") (pinfunction "A1_2") (pintype "bidirectional"))
      (node (ref "U27") (pin "GND") (pinfunction "GND_GND") (pintype "bidirectional"))
      (node (ref "U28") (pin "1") (pinfunction "A2_1") (pintype "bidirectional"))
      (node (ref "U28") (pin "17") (pinfunction "GND_17") (pintype "bidirectional"))
      (node (ref "U28") (pin "3") (pinfunction "A0_3") (pintype "bidirectional"))
      (node (ref "U28") (pin "GND") (pinfunction "GND_GND") (pintype "bidirectional"))
      (node (ref "U29") (pin "17") (pinfunction "GND_17") (pintype "bidirectional"))
      (node (ref "U29") (pin "2") (pinfunction "A1_2") (pintype "bidirectional"))
      (node (ref "U29") (pin "GND") (pinfunction "GND_GND") (pintype "bidirectional"))
      (node (ref "U3") (pin "4") (pinfunction "GND_4") (pintype "bidirectional"))
      (node (ref "U30") (pin "17") (pinfunction "GND_17") (pintype "bidirectional"))
      (node (ref "U30") (pin "3") (pinfunction "A0_3") (pintype "bidirectional"))
      (node (ref "U30") (pin "GND") (pinfunction "GND_GND") (pintype "bidirectional"))
      (node (ref "U31") (pin "17") (pinfunction "GND_17") (pintype "bidirectional"))
      (node (ref "U31") (pin "GND") (pinfunction "GND_GND") (pintype "bidirectional"))
      (node (ref "U32") (pin "1") (pinfunction "A2_1") (pintype "bidirectional"))
      (node (ref "U32") (pin "17") (pinfunction "GND_17") (pintype "bidirectional"))
      (node (ref "U32") (pin "GND") (pinfunction "GND_GND") (pintype "bidirectional"))
      (node (ref "U33") (pin "3") (pinfunction "GND_3") (pintype "bidirectional"))
      (node (ref "U34") (pin "2") (pinfunction "E1_2") (pintype "bidirectional"))
      (node (ref "U34") (pin "3") (pinfunction "E2_3") (pintype "bidirectional"))
      (node (ref "U34") (pin "4") (pinfunction "GND_4") (pintype "bidirectional"))
      (node (ref "U4") (pin "4") (pinfunction "GND_4") (pintype "bidirectional"))
      (node (ref "U5") (pin "4") (pinfunction "GND_4") (pintype "bidirectional"))
      (node (ref "U6") (pin "4") (pinfunction "GND_4") (pintype "bidirectional"))
      (node (ref "U7") (pin "4") (pinfunction "GND_4") (pintype "bidirectional"))
      (node (ref "U8") (pin "4") (pinfunction "GND_4") (pintype "bidirectional"))
      (node (ref "U9") (pin "4") (pinfunction "GND_4") (pintype "bidirectional"))
    )
    (net (code "16") (name "HUB_CFG") (class "Default")
      (node (ref "TP28") (pin "TESTPOINT") (pinfunction "TESTPOINT_TESTPOINT") (pintype "bidirectional"))
      (node (ref "U1") (pin "40") (pinfunction "HUBCFG_40") (pintype "bidirectional"))
      (node (ref "U32") (pin "14") (pinfunction "P5_14") (pintype "bidirectional"))
    )
    (net (code "17") (name "HUB_DM1") (class "Default")
      (node (ref "C6") (pin "1") (pinfunction "1_1") (pintype "bidirectional"))
      (node (ref "R4") (pin "1") (pinfunction "1_1") (pintype "passive"))
      (node (ref "U1") (pin "13") (pinfunction "DM1_13") (pintype "bidirectional"))
    )
    (net (code "18") (name "HUB_DM2") (class "Default")
      (node (ref "C4") (pin "1") (pinfunction "1_1") (pintype "bidirectional"))
      (node (ref "R2") (pin "1") (pinfunction "1_1") (pintype "passive"))
      (node (ref "U1") (pin "17") (pinfunction "DM2_17") (pintype "bidirectional"))
    )
    (net (code "19") (name "HUB_DM3") (class "Default")
      (node (ref "C8") (pin "1") (pinfunction "1_1") (pintype "bidirectional"))
      (node (ref "R6") (pin "1") (pinfunction "1_1") (pintype "passive"))
      (node (ref "U1") (pin "21") (pinfunction "DM3_21") (pintype "bidirectional"))
    )
    (net (code "20") (name "HUB_DM4") (class "Default")
      (node (ref "C12") (pin "1") (pinfunction "1_1") (pintype "bidirectional"))
      (node (ref "R10") (pin "1") (pinfunction "1_1") (pintype "passive"))
      (node (ref "U1") (pin "26") (pinfunction "DM4_26") (pintype "bidirectional"))
    )
    (net (code "21") (name "HUB_DM5") (class "Default")
      (node (ref "R66") (pin "1") (pinfunction "1_1") (pintype "passive"))
      (node (ref "U1") (pin "30") (pinfunction "DM5_30") (pintype "bidirectional"))
    )
    (net (code "22") (name "HUB_DM6") (class "Default")
      (node (ref "C14") (pin "1") (pinfunction "1_1") (pintype "bidirectional"))
      (node (ref "R12") (pin "1") (pinfunction "1_1") (pintype "passive"))
      (node (ref "U1") (pin "34") (pinfunction "DM6_34") (pintype "bidirectional"))
    )
    (net (code "23") (name "HUB_DM7") (class "Default")
      (node (ref "C10") (pin "1") (pinfunction "1_1") (pintype "bidirectional"))
      (node (ref "R8") (pin "1") (pinfunction "1_1") (pintype "passive"))
      (node (ref "U1") (pin "38") (pinfunction "DM7_38") (pintype "bidirectional"))
    )
    (net (code "24") (name "HUB_DP1") (class "Default")
      (node (ref "C5") (pin "1") (pinfunction "1_1") (pintype "bidirectional"))
      (node (ref "R3") (pin "1") (pinfunction "1_1") (pintype "passive"))
      (node (ref "U1") (pin "14") (pinfunction "DP1_14") (pintype "bidirectional"))
    )
    (net (code "25") (name "HUB_DP2") (class "Default")
      (node (ref "C3") (pin "1") (pinfunction "1_1") (pintype "bidirectional"))
      (node (ref "R1") (pin "1") (pinfunction "1_1") (pintype "passive"))
      (node (ref "U1") (pin "18") (pinfunction "DP2_18") (pintype "bidirectional"))
    )
    (net (code "26") (name "HUB_DP3") (class "Default")
      (node (ref "C7") (pin "1") (pinfunction "1_1") (pintype "bidirectional"))
      (node (ref "R5") (pin "1") (pinfunction "1_1") (pintype "passive"))
      (node (ref "U1") (pin "22") (pinfunction "DP3_22") (pintype "bidirectional"))
    )
    (net (code "27") (name "HUB_DP4") (class "Default")
      (node (ref "C11") (pin "1") (pinfunction "1_1") (pintype "bidirectional"))
      (node (ref "R9") (pin "1") (pinfunction "1_1") (pintype "passive"))
      (node (ref "U1") (pin "27") (pinfunction "DP4_27") (pintype "bidirectional"))
    )
    (net (code "28") (name "HUB_DP5") (class "Default")
      (node (ref "R65") (pin "1") (pinfunction "1_1") (pintype "passive"))
      (node (ref "U1") (pin "31") (pinfunction "DP5_31") (pintype "bidirectional"))
    )
    (net (code "29") (name "HUB_DP6") (class "Default")
      (node (ref "C13") (pin "1") (pinfunction "1_1") (pintype "bidirectional"))
      (node (ref "R11") (pin "1") (pinfunction "1_1") (pintype "passive"))
      (node (ref "U1") (pin "35") (pinfunction "DP6_35") (pintype "bidirectional"))
    )
    (net (code "30") (name "HUB_DP7") (class "Default")
      (node (ref "C9") (pin "1") (pinfunction "1_1") (pintype "bidirectional"))
      (node (ref "R7") (pin "1") (pinfunction "1_1") (pintype "passive"))
      (node (ref "U1") (pin "39") (pinfunction "DP7_39") (pintype "bidirectional"))
    )
    (net (code "31") (name "HUB_PORTDIS") (class "Default")
      (node (ref "TP30") (pin "TESTPOINT") (pinfunction "TESTPOINT_TESTPOINT") (pintype "bidirectional"))
      (node (ref "U1") (pin "42") (pinfunction "PORTDIS_42") (pintype "bidirectional"))
    )
    (net (code "32") (name "HUB_PORTPWR") (class "Default")
      (node (ref "TP29") (pin "TESTPOINT") (pinfunction "TESTPOINT_TESTPOINT") (pintype "bidirectional"))
      (node (ref "U1") (pin "41") (pinfunction "PORTPWR_41") (pintype "bidirectional"))
    )
    (net (code "33") (name "HUB_~{OVRCUR1}") (class "Default")
      (node (ref "R29") (pin "1") (pinfunction "1_1") (pintype "passive"))
      (node (ref "S14") (pin "5") (pinfunction "~{FLG}_5") (pintype "bidirectional"))
      (node (ref "TP33") (pin "TESTPOINT") (pinfunction "TESTPOINT_TESTPOINT") (pintype "bidirectional"))
      (node (ref "U1") (pin "12") (pinfunction "~{OVRCUR1}_12") (pintype "bidirectional"))
    )
    (net (code "34") (name "HUB_~{OVRCUR2}") (class "Default")
      (node (ref "R28") (pin "1") (pinfunction "1_1") (pintype "passive"))
      (node (ref "S13") (pin "5") (pinfunction "~{FLG}_5") (pintype "bidirectional"))
      (node (ref "TP35") (pin "TESTPOINT") (pinfunction "TESTPOINT_TESTPOINT") (pintype "bidirectional"))
      (node (ref "U1") (pin "16") (pinfunction "~{OVRCUR2}_16") (pintype "bidirectional"))
    )
    (net (code "35") (name "HUB_~{OVRCUR3}") (class "Default")
      (node (ref "R30") (pin "1") (pinfunction "1_1") (pintype "passive"))
      (node (ref "S15") (pin "5") (pinfunction "~{FLG}_5") (pintype "bidirectional"))
      (node (ref "TP37") (pin "TESTPOINT") (pinfunction "TESTPOINT_TESTPOINT") (pintype "bidirectional"))
      (node (ref "U1") (pin "20") (pinfunction "~{OVRCUR3}_20") (pintype "bidirectional"))
    )
    (net (code "36") (name "HUB_~{OVRCUR4}") (class "Default")
      (node (ref "R32") (pin "1") (pinfunction "1_1") (pintype "passive"))
      (node (ref "S17") (pin "5") (pinfunction "~{FLG}_5") (pintype "bidirectional"))
      (node (ref "TP39") (pin "TESTPOINT") (pinfunction "TESTPOINT_TESTPOINT") (pintype "bidirectional"))
      (node (ref "U1") (pin "25") (pinfunction "~{OVRCUR4}_25") (pintype "bidirectional"))
    )
    (net (code "37") (name "HUB_~{OVRCUR5}") (class "Default")
      (node (ref "R51") (pin "1") (pinfunction "1_1") (pintype "passive"))
      (node (ref "U1") (pin "29") (pinfunction "~{OVRCUR5}_29") (pintype "bidirectional"))
    )
    (net (code "38") (name "HUB_~{OVRCUR6}") (class "Default")
      (node (ref "R33") (pin "1") (pinfunction "1_1") (pintype "passive"))
      (node (ref "S18") (pin "5") (pinfunction "~{FLG}_5") (pintype "bidirectional"))
      (node (ref "TP41") (pin "TESTPOINT") (pinfunction "TESTPOINT_TESTPOINT") (pintype "bidirectional"))
      (node (ref "U1") (pin "33") (pinfunction "~{OVRCUR6}_33") (pintype "bidirectional"))
    )
    (net (code "39") (name "HUB_~{OVRCUR7}") (class "Default")
      (node (ref "R31") (pin "1") (pinfunction "1_1") (pintype "passive"))
      (node (ref "S16") (pin "5") (pinfunction "~{FLG}_5") (pintype "bidirectional"))
      (node (ref "TP43") (pin "TESTPOINT") (pinfunction "TESTPOINT_TESTPOINT") (pintype "bidirectional"))
      (node (ref "U1") (pin "37") (pinfunction "~{OVRCUR7}_37") (pintype "bidirectional"))
    )
    (net (code "40") (name "HUB_~{PWRON1}") (class "Default")
      (node (ref "S8") (pin "1") (pinfunction "I1_1") (pintype "bidirectional"))
      (node (ref "TP32") (pin "TESTPOINT") (pinfunction "TESTPOINT_TESTPOINT") (pintype "bidirectional"))
      (node (ref "U1") (pin "11") (pinfunction "~{PWRON1}_11") (pintype "bidirectional"))
      (node (ref "U32") (pin "10") (pinfunction "P1_10") (pintype "bidirectional"))
    )
    (net (code "41") (name "HUB_~{PWRON2}") (class "Default")
      (node (ref "S7") (pin "1") (pinfunction "I1_1") (pintype "bidirectional"))
      (node (ref "TP34") (pin "TESTPOINT") (pinfunction "TESTPOINT_TESTPOINT") (pintype "bidirectional"))
      (node (ref "U1") (pin "15") (pinfunction "~{PWRON2}_15") (pintype "bidirectional"))
      (node (ref "U32") (pin "11") (pinfunction "P2_11") (pintype "bidirectional"))
    )
    (net (code "42") (name "HUB_~{PWRON3}") (class "Default")
      (node (ref "S9") (pin "1") (pinfunction "I1_1") (pintype "bidirectional"))
      (node (ref "TP36") (pin "TESTPOINT") (pinfunction "TESTPOINT_TESTPOINT") (pintype "bidirectional"))
      (node (ref "U1") (pin "19") (pinfunction "~{PWRON3}_19") (pintype "bidirectional"))
      (node (ref "U32") (pin "12") (pinfunction "P3_12") (pintype "bidirectional"))
    )
    (net (code "43") (name "HUB_~{PWRON4}") (class "Default")
      (node (ref "S11") (pin "1") (pinfunction "I1_1") (pintype "bidirectional"))
      (node (ref "TP38") (pin "TESTPOINT") (pinfunction "TESTPOINT_TESTPOINT") (pintype "bidirectional"))
      (node (ref "U1") (pin "23") (pinfunction "~{PWRON4}_23") (pintype "bidirectional"))
      (node (ref "U32") (pin "13") (pinfunction "P4_13") (pintype "bidirectional"))
    )
    (net (code "44") (name "HUB_~{PWRON5}") (class "Default")
      (node (ref "U1") (pin "28") (pinfunction "~{PWRON5}_28") (pintype "bidirectional"))
    )
    (net (code "45") (name "HUB_~{PWRON6}") (class "Default")
      (node (ref "S12") (pin "1") (pinfunction "I1_1") (pintype "bidirectional"))
      (node (ref "TP40") (pin "TESTPOINT") (pinfunction "TESTPOINT_TESTPOINT") (pintype "bidirectional"))
      (node (ref "U1") (pin "32") (pinfunction "~{PWRON6}_32") (pintype "bidirectional"))
      (node (ref "U32") (pin "15") (pinfunction "P6_15") (pintype "bidirectional"))
    )
    (net (code "46") (name "HUB_~{PWRON7}") (class "Default")
      (node (ref "S10") (pin "1") (pinfunction "I1_1") (pintype "bidirectional"))
      (node (ref "TP42") (pin "TESTPOINT") (pinfunction "TESTPOINT_TESTPOINT") (pintype "bidirectional"))
      (node (ref "U1") (pin "36") (pinfunction "~{PWRON7}_36") (pintype "bidirectional"))
      (node (ref "U32") (pin "16") (pinfunction "P7_16") (pintype "bidirectional"))
    )
    (net (code "47") (name "MOD0_5V") (class "Default")
      (node (ref "C21") (pin "1") (pinfunction "1_1") (pintype "bidirectional"))
      (node (ref "J0") (pin "2") (pinfunction "5V_2") (pintype "bidirectional"))
      (node (ref "S1") (pin "1") (pinfunction "VLOAD_1") (pintype "bidirectional"))
    )
    (net (code "48") (name "MOD0_5V_METERED") (class "Default")
      (node (ref "C70") (pin "1") (pinfunction "1_1") (pintype "bidirectional"))
      (node (ref "C90") (pin "1") (pinfunction "1_1") (pintype "bidirectional"))
      (node (ref "J4") (pin "7") (pinfunction "VCC_MOD0_7") (pintype "power_in"))
      (node (ref "S1") (pin "3") (pinfunction "VSUPP_3") (pintype "bidirectional"))
      (node (ref "S13") (pin "2") (pinfunction "IN_2") (pintype "bidirectional"))
      (node (ref "S13") (pin "3") (pinfunction "IN_3") (pintype "bidirectional"))
      (node (ref "TP16") (pin "TESTPOINT") (pinfunction "TESTPOINT_TESTPOINT") (pintype "bidirectional"))
    )
    (net (code "49") (name "MOD0_D+_HUB-SW") (class "Default")
      (node (ref "D1") (pin "4") (pinfunction "D_4") (pintype "bidirectional"))
      (node (ref "R1") (pin "2") (pinfunction "2_2") (pintype "passive"))
      (node (ref "R53") (pin "2") (pinfunction "2_2") (pintype "passive"))
      (node (ref "U20") (pin "3") (pinfunction "D+_3") (pintype "bidirectional"))
    )
    (net (code "50") (name "MOD0_D-_HUB-SW") (class "Default")
      (node (ref "D1") (pin "2") (pinfunction "C_2") (pintype "bidirectional"))
      (node (ref "R2") (pin "2") (pinfunction "2_2") (pintype "passive"))
      (node (ref "R54") (pin "2") (pinfunction "2_2") (pintype "passive"))
      (node (ref "U20") (pin "5") (pinfunction "D-_5") (pintype "bidirectional"))
    )
    (net (code "51") (name "MOD0_IN") (class "Default")
      (node (ref "J0") (pin "10") (pinfunction "MOD_IN_10") (pintype "bidirectional"))
      (node (ref "U8") (pin "7") (pinfunction "B1_7") (pintype "bidirectional"))
    )
    (net (code "52") (name "MOD0_ISO_I2C") (class "Default")
      (node (ref "R1002") (pin "2") (pinfunction "2_2") (pintype "passive"))
      (node (ref "R68") (pin "2") (pinfunction "2_2") (pintype "passive"))
      (node (ref "TP1002") (pin "TESTPOINT") (pinfunction "TESTPOINT_TESTPOINT") (pintype "bidirectional"))
      (node (ref "U2") (pin "5") (pinfunction "OE_5") (pintype "bidirectional"))
      (node (ref "U26") (pin "10") (pinfunction "P1_10") (pintype "bidirectional"))
    )
    (net (code "53") (name "MOD0_ISO_POWER") (class "Default")
      (node (ref "R1001") (pin "2") (pinfunction "2_2") (pintype "passive"))
      (node (ref "R67") (pin "2") (pinfunction "2_2") (pintype "passive"))
      (node (ref "S1") (pin "4") (pinfunction "EN_4") (pintype "bidirectional"))
      (node (ref "TP1001") (pin "TESTPOINT") (pinfunction "TESTPOINT_TESTPOINT") (pintype "bidirectional"))
      (node (ref "U26") (pin "9") (pinfunction "P0_9") (pintype "bidirectional"))
    )
    (net (code "54") (name "MOD0_ISO_USB") (class "Default")
      (node (ref "R1003") (pin "2") (pinfunction "2_2") (pintype "passive"))
      (node (ref "R69") (pin "2") (pinfunction "2_2") (pintype "passive"))
      (node (ref "S7") (pin "6") (pinfunction "S_6") (pintype "bidirectional"))
      (node (ref "TP1003") (pin "TESTPOINT") (pinfunction "TESTPOINT_TESTPOINT") (pintype "bidirectional"))
      (node (ref "U26") (pin "11") (pinfunction "P2_11") (pintype "bidirectional"))
    )
    (net (code "55") (name "MOD0_OUT") (class "Default")
      (node (ref "J0") (pin "8") (pinfunction "MOD_OUT_8") (pintype "bidirectional"))
      (node (ref "U14") (pin "7") (pinfunction "B1_7") (pintype "bidirectional"))
    )
    (net (code "56") (name "MOD0_PPS") (class "Default")
      (node (ref "J0") (pin "7") (pinfunction "PPS_7") (pintype "bidirectional"))
      (node (ref "U8") (pin "6") (pinfunction "B2_6") (pintype "bidirectional"))
    )
    (net (code "57") (name "MOD0_SCL") (class "Default")
      (node (ref "J0") (pin "5") (pinfunction "SCL_5") (pintype "bidirectional"))
      (node (ref "R35") (pin "2") (pinfunction "2_2") (pintype "passive"))
      (node (ref "U2") (pin "6") (pinfunction "B1_6") (pintype "bidirectional"))
    )
    (net (code "58") (name "MOD0_SDA") (class "Default")
      (node (ref "J0") (pin "6") (pinfunction "SDA_6") (pintype "bidirectional"))
      (node (ref "R34") (pin "2") (pinfunction "2_2") (pintype "passive"))
      (node (ref "U2") (pin "7") (pinfunction "B0_7") (pintype "bidirectional"))
    )
    (net (code "59") (name "MOD0_USB+") (class "Default")
      (node (ref "J0") (pin "11") (pinfunction "USB_D+_11") (pintype "bidirectional"))
      (node (ref "U20") (pin "1") (pinfunction "D1+_1") (pintype "bidirectional"))
    )
    (net (code "60") (name "MOD0_USB-") (class "Default")
      (node (ref "J0") (pin "12") (pinfunction "USB_D-_12") (pintype "bidirectional"))
      (node (ref "U20") (pin "7") (pinfunction "D1-_7") (pintype "bidirectional"))
    )
    (net (code "61") (name "MOD0_USB_VBUS") (class "Default")
      (node (ref "C58") (pin "1") (pinfunction "1_1") (pintype "bidirectional"))
      (node (ref "C97") (pin "1") (pinfunction "1_1") (pintype "passive"))
      (node (ref "J0") (pin "13") (pinfunction "USB_VBUS_13") (pintype "bidirectional"))
      (node (ref "S13") (pin "6") (pinfunction "OUT_6") (pintype "bidirectional"))
      (node (ref "S13") (pin "7") (pinfunction "OUT_7") (pintype "bidirectional"))
    )
    (net (code "62") (name "MOD0_USB_~{EN}") (class "Default")
      (node (ref "S13") (pin "4") (pinfunction "~{EN}_4") (pintype "bidirectional"))
      (node (ref "S7") (pin "4") (pinfunction "Z_4") (pintype "bidirectional"))
      (node (ref "U20") (pin "8") (pinfunction "~{OE}_8") (pintype "bidirectional"))
    )
    (net (code "63") (name "MOD0_VCCIO") (class "Default")
      (node (ref "C39") (pin "1") (pinfunction "1_1") (pintype "bidirectional"))
      (node (ref "C45") (pin "1") (pinfunction "1_1") (pintype "bidirectional"))
      (node (ref "C82") (pin "1") (pinfunction "1_1") (pintype "bidirectional"))
      (node (ref "J0") (pin "4") (pinfunction "VCCIO_4") (pintype "bidirectional"))
      (node (ref "R34") (pin "1") (pinfunction "1_1") (pintype "passive"))
      (node (ref "R35") (pin "1") (pinfunction "1_1") (pintype "passive"))
      (node (ref "U14") (pin "8") (pinfunction "VCC_B_8") (pintype "bidirectional"))
      (node (ref "U2") (pin "8") (pinfunction "VCC_B_8") (pintype "bidirectional"))
      (node (ref "U8") (pin "8") (pinfunction "VCC_B_8") (pintype "bidirectional"))
    )
    (net (code "64") (name "MOD1_5V") (class "Default")
      (node (ref "C22") (pin "1") (pinfunction "1_1") (pintype "bidirectional"))
      (node (ref "J1") (pin "2") (pinfunction "5V_2") (pintype "bidirectional"))
      (node (ref "S2") (pin "1") (pinfunction "VLOAD_1") (pintype "bidirectional"))
    )
    (net (code "65") (name "MOD1_5V_METERED") (class "Default")
      (node (ref "C71") (pin "1") (pinfunction "1_1") (pintype "bidirectional"))
      (node (ref "C91") (pin "1") (pinfunction "1_1") (pintype "bidirectional"))
      (node (ref "J4") (pin "8") (pinfunction "VCC_MOD1_8") (pintype "power_in"))
      (node (ref "S14") (pin "2") (pinfunction "IN_2") (pintype "bidirectional"))
      (node (ref "S14") (pin "3") (pinfunction "IN_3") (pintype "bidirectional"))
      (node (ref "S2") (pin "3") (pinfunction "VSUPP_3") (pintype "bidirectional"))
      (node (ref "TP17") (pin "TESTPOINT") (pinfunction "TESTPOINT_TESTPOINT") (pintype "bidirectional"))
    )
    (net (code "66") (name "MOD1_D+_HUB-SW") (class "Default")
      (node (ref "D1") (pin "8") (pinfunction "A_8") (pintype "bidirectional"))
      (node (ref "R3") (pin "2") (pinfunction "2_2") (pintype "passive"))
      (node (ref "R55") (pin "2") (pinfunction "2_2") (pintype "passive"))
      (node (ref "U21") (pin "3") (pinfunction "D+_3") (pintype "bidirectional"))
    )
    (net (code "67") (name "MOD1_D-_HUB-SW") (class "Default")
      (node (ref "D1") (pin "6") (pinfunction "B_6") (pintype "bidirectional"))
      (node (ref "R4") (pin "2") (pinfunction "2_2") (pintype "passive"))
      (node (ref "R56") (pin "2") (pinfunction "2_2") (pintype "passive"))
      (node (ref "U21") (pin "5") (pinfunction "D-_5") (pintype "bidirectional"))
    )
    (net (code "68") (name "MOD1_IN") (class "Default")
      (node (ref "J1") (pin "10") (pinfunction "MOD_IN_10") (pintype "bidirectional"))
      (node (ref "U9") (pin "7") (pinfunction "B1_7") (pintype "bidirectional"))
    )
    (net (code "69") (name "MOD1_ISO_I2C") (class "Default")
      (node (ref "LED1005") (pin "A") (pinfunction "ANODE_A") (pintype "bidirectional"))
      (node (ref "R71") (pin "2") (pinfunction "2_2") (pintype "passive"))
      (node (ref "TP1005") (pin "TESTPOINT") (pinfunction "TESTPOINT_TESTPOINT") (pintype "bidirectional"))
      (node (ref "U27") (pin "10") (pinfunction "P1_10") (pintype "bidirectional"))
      (node (ref "U3") (pin "5") (pinfunction "OE_5") (pintype "bidirectional"))
    )
    (net (code "70") (name "MOD1_ISO_POWER") (class "Default")
      (node (ref "LED1004") (pin "A") (pinfunction "ANODE_A") (pintype "bidirectional"))
      (node (ref "R70") (pin "2") (pinfunction "2_2") (pintype "passive"))
      (node (ref "S2") (pin "4") (pinfunction "EN_4") (pintype "bidirectional"))
      (node (ref "TP1004") (pin "TESTPOINT") (pinfunction "TESTPOINT_TESTPOINT") (pintype "bidirectional"))
      (node (ref "U27") (pin "9") (pinfunction "P0_9") (pintype "bidirectional"))
    )
    (net (code "71") (name "MOD1_ISO_USB") (class "Default")
      (node (ref "LED1006") (pin "A") (pinfunction "ANODE_A") (pintype "bidirectional"))
      (node (ref "R72") (pin "2") (pinfunction "2_2") (pintype "passive"))
      (node (ref "S8") (pin "6") (pinfunction "S_6") (pintype "bidirectional"))
      (node (ref "TP1006") (pin "TESTPOINT") (pinfunction "TESTPOINT_TESTPOINT") (pintype "bidirectional"))
      (node (ref "U27") (pin "11") (pinfunction "P2_11") (pintype "bidirectional"))
    )
    (net (code "72") (name "MOD1_OUT") (class "Default")
      (node (ref "J1") (pin "8") (pinfunction "MOD_OUT_8") (pintype "bidirectional"))
      (node (ref "U15") (pin "7") (pinfunction "B1_7") (pintype "bidirectional"))
    )
    (net (code "73") (name "MOD1_PPS") (class "Default")
      (node (ref "J1") (pin "7") (pinfunction "PPS_7") (pintype "bidirectional"))
      (node (ref "U9") (pin "6") (pinfunction "B2_6") (pintype "bidirectional"))
    )
    (net (code "74") (name "MOD1_SCL") (class "Default")
      (node (ref "J1") (pin "5") (pinfunction "SCL_5") (pintype "bidirectional"))
      (node (ref "R37") (pin "2") (pinfunction "2_2") (pintype "passive"))
      (node (ref "U3") (pin "6") (pinfunction "B1_6") (pintype "bidirectional"))
    )
    (net (code "75") (name "MOD1_SDA") (class "Default")
      (node (ref "J1") (pin "6") (pinfunction "SDA_6") (pintype "bidirectional"))
      (node (ref "R36") (pin "2") (pinfunction "2_2") (pintype "passive"))
      (node (ref "U3") (pin "7") (pinfunction "B0_7") (pintype "bidirectional"))
    )
    (net (code "76") (name "MOD1_USB+") (class "Default")
      (node (ref "J1") (pin "11") (pinfunction "USB_D+_11") (pintype "bidirectional"))
      (node (ref "U21") (pin "1") (pinfunction "D1+_1") (pintype "bidirectional"))
    )
    (net (code "77") (name "MOD1_USB-") (class "Default")
      (node (ref "J1") (pin "12") (pinfunction "USB_D-_12") (pintype "bidirectional"))
      (node (ref "U21") (pin "7") (pinfunction "D1-_7") (pintype "bidirectional"))
    )
    (net (code "78") (name "MOD1_USB_VBUS") (class "Default")
      (node (ref "C59") (pin "1") (pinfunction "1_1") (pintype "bidirectional"))
      (node (ref "C98") (pin "1") (pinfunction "1_1") (pintype "passive"))
      (node (ref "J1") (pin "13") (pinfunction "USB_VBUS_13") (pintype "bidirectional"))
      (node (ref "S14") (pin "6") (pinfunction "OUT_6") (pintype "bidirectional"))
      (node (ref "S14") (pin "7") (pinfunction "OUT_7") (pintype "bidirectional"))
    )
    (net (code "79") (name "MOD1_USB_~{EN}") (class "Default")
      (node (ref "S14") (pin "4") (pinfunction "~{EN}_4") (pintype "bidirectional"))
      (node (ref "S8") (pin "4") (pinfunction "Z_4") (pintype "bidirectional"))
      (node (ref "U21") (pin "8") (pinfunction "~{OE}_8") (pintype "bidirectional"))
    )
    (net (code "80") (name "MOD1_VCCIO") (class "Default")
      (node (ref "C40") (pin "1") (pinfunction "1_1") (pintype "bidirectional"))
      (node (ref "C46") (pin "1") (pinfunction "1_1") (pintype "bidirectional"))
      (node (ref "C83") (pin "1") (pinfunction "1_1") (pintype "bidirectional"))
      (node (ref "J1") (pin "4") (pinfunction "VCCIO_4") (pintype "bidirectional"))
      (node (ref "R36") (pin "1") (pinfunction "1_1") (pintype "passive"))
      (node (ref "R37") (pin "1") (pinfunction "1_1") (pintype "passive"))
      (node (ref "U15") (pin "8") (pinfunction "VCC_B_8") (pintype "bidirectional"))
      (node (ref "U3") (pin "8") (pinfunction "VCC_B_8") (pintype "bidirectional"))
      (node (ref "U9") (pin "8") (pinfunction "VCC_B_8") (pintype "bidirectional"))
    )
    (net (code "81") (name "MOD2_5V") (class "Default")
      (node (ref "C23") (pin "1") (pinfunction "1_1") (pintype "bidirectional"))
      (node (ref "J2") (pin "2") (pinfunction "5V_2") (pintype "bidirectional"))
      (node (ref "S3") (pin "1") (pinfunction "VLOAD_1") (pintype "bidirectional"))
    )
    (net (code "82") (name "MOD2_5V_METERED") (class "Default")
      (node (ref "C72") (pin "1") (pinfunction "1_1") (pintype "bidirectional"))
      (node (ref "C92") (pin "1") (pinfunction "1_1") (pintype "bidirectional"))
      (node (ref "J4") (pin "9") (pinfunction "VCC_MOD2_9") (pintype "power_in"))
      (node (ref "S15") (pin "2") (pinfunction "IN_2") (pintype "bidirectional"))
      (node (ref "S15") (pin "3") (pinfunction "IN_3") (pintype "bidirectional"))
      (node (ref "S3") (pin "3") (pinfunction "VSUPP_3") (pintype "bidirectional"))
      (node (ref "TP18") (pin "TESTPOINT") (pinfunction "TESTPOINT_TESTPOINT") (pintype "bidirectional"))
    )
    (net (code "83") (name "MOD2_D+_HUB-SW") (class "Default")
      (node (ref "D2") (pin "8") (pinfunction "A_8") (pintype "bidirectional"))
      (node (ref "R5") (pin "2") (pinfunction "2_2") (pintype "passive"))
      (node (ref "R57") (pin "2") (pinfunction "2_2") (pintype "passive"))
      (node (ref "U22") (pin "3") (pinfunction "D+_3") (pintype "bidirectional"))
    )
    (net (code "84") (name "MOD2_D-_HUB-SW") (class "Default")
      (node (ref "D2") (pin "6") (pinfunction "B_6") (pintype "bidirectional"))
      (node (ref "R58") (pin "2") (pinfunction "2_2") (pintype "passive"))
      (node (ref "R6") (pin "2") (pinfunction "2_2") (pintype "passive"))
      (node (ref "U22") (pin "5") (pinfunction "D-_5") (pintype "bidirectional"))
    )
    (net (code "85") (name "MOD2_IN") (class "Default")
      (node (ref "J2") (pin "10") (pinfunction "MOD_IN_10") (pintype "bidirectional"))
      (node (ref "U10") (pin "7") (pinfunction "B1_7") (pintype "bidirectional"))
    )
    (net (code "86") (name "MOD2_ISO_I2C") (class "Default")
      (node (ref "R1008") (pin "2") (pinfunction "2_2") (pintype "passive"))
      (node (ref "R74") (pin "2") (pinfunction "2_2") (pintype "passive"))
      (node (ref "TP1008") (pin "TESTPOINT") (pinfunction "TESTPOINT_TESTPOINT") (pintype "bidirectional"))
      (node (ref "U28") (pin "10") (pinfunction "P1_10") (pintype "bidirectional"))
      (node (ref "U4") (pin "5") (pinfunction "OE_5") (pintype "bidirectional"))
    )
    (net (code "87") (name "MOD2_ISO_POWER") (class "Default")
      (node (ref "R1007") (pin "2") (pinfunction "2_2") (pintype "passive"))
      (node (ref "R73") (pin "2") (pinfunction "2_2") (pintype "passive"))
      (node (ref "S3") (pin "4") (pinfunction "EN_4") (pintype "bidirectional"))
      (node (ref "TP1007") (pin "TESTPOINT") (pinfunction "TESTPOINT_TESTPOINT") (pintype "bidirectional"))
      (node (ref "U28") (pin "9") (pinfunction "P0_9") (pintype "bidirectional"))
    )
    (net (code "88") (name "MOD2_ISO_USB") (class "Default")
      (node (ref "R1009") (pin "2") (pinfunction "2_2") (pintype "passive"))
      (node (ref "R75") (pin "2") (pinfunction "2_2") (pintype "passive"))
      (node (ref "S9") (pin "6") (pinfunction "S_6") (pintype "bidirectional"))
      (node (ref "TP1009") (pin "TESTPOINT") (pinfunction "TESTPOINT_TESTPOINT") (pintype "bidirectional"))
      (node (ref "U28") (pin "11") (pinfunction "P2_11") (pintype "bidirectional"))
    )
    (net (code "89") (name "MOD2_OUT") (class "Default")
      (node (ref "J2") (pin "8") (pinfunction "MOD_OUT_8") (pintype "bidirectional"))
      (node (ref "U16") (pin "7") (pinfunction "B1_7") (pintype "bidirectional"))
    )
    (net (code "90") (name "MOD2_PPS") (class "Default")
      (node (ref "J2") (pin "7") (pinfunction "PPS_7") (pintype "bidirectional"))
      (node (ref "U10") (pin "6") (pinfunction "B2_6") (pintype "bidirectional"))
    )
    (net (code "91") (name "MOD2_SCL") (class "Default")
      (node (ref "J2") (pin "5") (pinfunction "SCL_5") (pintype "bidirectional"))
      (node (ref "R39") (pin "2") (pinfunction "2_2") (pintype "passive"))
      (node (ref "U4") (pin "6") (pinfunction "B1_6") (pintype "bidirectional"))
    )
    (net (code "92") (name "MOD2_SDA") (class "Default")
      (node (ref "J2") (pin "6") (pinfunction "SDA_6") (pintype "bidirectional"))
      (node (ref "R38") (pin "2") (pinfunction "2_2") (pintype "passive"))
      (node (ref "U4") (pin "7") (pinfunction "B0_7") (pintype "bidirectional"))
    )
    (net (code "93") (name "MOD2_USB+") (class "Default")
      (node (ref "J2") (pin "11") (pinfunction "USB_D+_11") (pintype "bidirectional"))
      (node (ref "U22") (pin "1") (pinfunction "D1+_1") (pintype "bidirectional"))
    )
    (net (code "94") (name "MOD2_USB-") (class "Default")
      (node (ref "J2") (pin "12") (pinfunction "USB_D-_12") (pintype "bidirectional"))
      (node (ref "U22") (pin "7") (pinfunction "D1-_7") (pintype "bidirectional"))
    )
    (net (code "95") (name "MOD2_USB_VBUS") (class "Default")
      (node (ref "C60") (pin "1") (pinfunction "1_1") (pintype "bidirectional"))
      (node (ref "C99") (pin "1") (pinfunction "1_1") (pintype "passive"))
      (node (ref "J2") (pin "13") (pinfunction "USB_VBUS_13") (pintype "bidirectional"))
      (node (ref "S15") (pin "6") (pinfunction "OUT_6") (pintype "bidirectional"))
      (node (ref "S15") (pin "7") (pinfunction "OUT_7") (pintype "bidirectional"))
    )
    (net (code "96") (name "MOD2_USB_~{EN}") (class "Default")
      (node (ref "S15") (pin "4") (pinfunction "~{EN}_4") (pintype "bidirectional"))
      (node (ref "S9") (pin "4") (pinfunction "Z_4") (pintype "bidirectional"))
      (node (ref "U22") (pin "8") (pinfunction "~{OE}_8") (pintype "bidirectional"))
    )
    (net (code "97") (name "MOD2_VCCIO") (class "Default")
      (node (ref "C41") (pin "1") (pinfunction "1_1") (pintype "bidirectional"))
      (node (ref "C47") (pin "1") (pinfunction "1_1") (pintype "bidirectional"))
      (node (ref "C84") (pin "1") (pinfunction "1_1") (pintype "bidirectional"))
      (node (ref "J2") (pin "4") (pinfunction "VCCIO_4") (pintype "bidirectional"))
      (node (ref "R38") (pin "1") (pinfunction "1_1") (pintype "passive"))
      (node (ref "R39") (pin "1") (pinfunction "1_1") (pintype "passive"))
      (node (ref "U10") (pin "8") (pinfunction "VCC_B_8") (pintype "bidirectional"))
      (node (ref "U16") (pin "8") (pinfunction "VCC_B_8") (pintype "bidirectional"))
      (node (ref "U4") (pin "8") (pinfunction "VCC_B_8") (pintype "bidirectional"))
    )
    (net (code "98") (name "MOD5_5V") (class "Default")
      (node (ref "C24") (pin "1") (pinfunction "1_1") (pintype "bidirectional"))
      (node (ref "J5") (pin "2") (pinfunction "5V_2") (pintype "bidirectional"))
      (node (ref "S4") (pin "1") (pinfunction "VLOAD_1") (pintype "bidirectional"))
    )
    (net (code "99") (name "MOD5_5V_METERED") (class "Default")
      (node (ref "C73") (pin "1") (pinfunction "1_1") (pintype "bidirectional"))
      (node (ref "C93") (pin "1") (pinfunction "1_1") (pintype "bidirectional"))
      (node (ref "J4") (pin "10") (pinfunction "VCC_MOD5_10") (pintype "power_in"))
      (node (ref "S16") (pin "2") (pinfunction "IN_2") (pintype "bidirectional"))
      (node (ref "S16") (pin "3") (pinfunction "IN_3") (pintype "bidirectional"))
      (node (ref "S4") (pin "3") (pinfunction "VSUPP_3") (pintype "bidirectional"))
      (node (ref "TP19") (pin "TESTPOINT") (pinfunction "TESTPOINT_TESTPOINT") (pintype "bidirectional"))
    )
    (net (code "100") (name "MOD5_D+_HUB-SW") (class "Default")
      (node (ref "D3") (pin "2") (pinfunction "C_2") (pintype "bidirectional"))
      (node (ref "R59") (pin "2") (pinfunction "2_2") (pintype "passive"))
      (node (ref "R7") (pin "2") (pinfunction "2_2") (pintype "passive"))
      (node (ref "U23") (pin "3") (pinfunction "D+_3") (pintype "bidirectional"))
    )
    (net (code "101") (name "MOD5_D-_HUB-SW") (class "Default")
      (node (ref "D3") (pin "4") (pinfunction "D_4") (pintype "bidirectional"))
      (node (ref "R60") (pin "2") (pinfunction "2_2") (pintype "passive"))
      (node (ref "R8") (pin "2") (pinfunction "2_2") (pintype "passive"))
      (node (ref "U23") (pin "5") (pinfunction "D-_5") (pintype "bidirectional"))
    )
    (net (code "102") (name "MOD5_IN") (class "Default")
      (node (ref "J5") (pin "10") (pinfunction "MOD_IN_10") (pintype "bidirectional"))
      (node (ref "U11") (pin "7") (pinfunction "B1_7") (pintype "bidirectional"))
    )
    (net (code "103") (name "MOD5_ISO_I2C") (class "Default")
      (node (ref "LED1011") (pin "A") (pinfunction "ANODE_A") (pintype "bidirectional"))
      (node (ref "R77") (pin "2") (pinfunction "2_2") (pintype "passive"))
      (node (ref "TP1011") (pin "TESTPOINT") (pinfunction "TESTPOINT_TESTPOINT") (pintype "bidirectional"))
      (node (ref "U29") (pin "10") (pinfunction "P1_10") (pintype "bidirectional"))
      (node (ref "U5") (pin "5") (pinfunction "OE_5") (pintype "bidirectional"))
    )
    (net (code "104") (name "MOD5_ISO_POWER") (class "Default")
      (node (ref "LED1010") (pin "A") (pinfunction "ANODE_A") (pintype "bidirectional"))
      (node (ref "R76") (pin "2") (pinfunction "2_2") (pintype "passive"))
      (node (ref "S4") (pin "4") (pinfunction "EN_4") (pintype "bidirectional"))
      (node (ref "TP1010") (pin "TESTPOINT") (pinfunction "TESTPOINT_TESTPOINT") (pintype "bidirectional"))
      (node (ref "U29") (pin "9") (pinfunction "P0_9") (pintype "bidirectional"))
    )
    (net (code "105") (name "MOD5_ISO_USB") (class "Default")
      (node (ref "LED1012") (pin "A") (pinfunction "ANODE_A") (pintype "bidirectional"))
      (node (ref "R78") (pin "2") (pinfunction "2_2") (pintype "passive"))
      (node (ref "S10") (pin "6") (pinfunction "S_6") (pintype "bidirectional"))
      (node (ref "TP1012") (pin "TESTPOINT") (pinfunction "TESTPOINT_TESTPOINT") (pintype "bidirectional"))
      (node (ref "U29") (pin "11") (pinfunction "P2_11") (pintype "bidirectional"))
    )
    (net (code "106") (name "MOD5_OUT") (class "Default")
      (node (ref "J5") (pin "8") (pinfunction "MOD_OUT_8") (pintype "bidirectional"))
      (node (ref "U17") (pin "7") (pinfunction "B1_7") (pintype "bidirectional"))
    )
    (net (code "107") (name "MOD5_PPS") (class "Default")
      (node (ref "J5") (pin "7") (pinfunction "PPS_7") (pintype "bidirectional"))
      (node (ref "U11") (pin "6") (pinfunction "B2_6") (pintype "bidirectional"))
    )
    (net (code "108") (name "MOD5_SCL") (class "Default")
      (node (ref "J5") (pin "5") (pinfunction "SCL_5") (pintype "bidirectional"))
      (node (ref "R41") (pin "2") (pinfunction "2_2") (pintype "passive"))
      (node (ref "U5") (pin "6") (pinfunction "B1_6") (pintype "bidirectional"))
    )
    (net (code "109") (name "MOD5_SDA") (class "Default")
      (node (ref "J5") (pin "6") (pinfunction "SDA_6") (pintype "bidirectional"))
      (node (ref "R40") (pin "2") (pinfunction "2_2") (pintype "passive"))
      (node (ref "U5") (pin "7") (pinfunction "B0_7") (pintype "bidirectional"))
    )
    (net (code "110") (name "MOD5_USB+") (class "Default")
      (node (ref "J5") (pin "11") (pinfunction "USB_D+_11") (pintype "bidirectional"))
      (node (ref "U23") (pin "1") (pinfunction "D1+_1") (pintype "bidirectional"))
    )
    (net (code "111") (name "MOD5_USB-") (class "Default")
      (node (ref "J5") (pin "12") (pinfunction "USB_D-_12") (pintype "bidirectional"))
      (node (ref "U23") (pin "7") (pinfunction "D1-_7") (pintype "bidirectional"))
    )
    (net (code "112") (name "MOD5_USB_VBUS") (class "Default")
      (node (ref "C100") (pin "1") (pinfunction "1_1") (pintype "passive"))
      (node (ref "C61") (pin "1") (pinfunction "1_1") (pintype "bidirectional"))
      (node (ref "J5") (pin "13") (pinfunction "USB_VBUS_13") (pintype "bidirectional"))
      (node (ref "S16") (pin "6") (pinfunction "OUT_6") (pintype "bidirectional"))
      (node (ref "S16") (pin "7") (pinfunction "OUT_7") (pintype "bidirectional"))
    )
    (net (code "113") (name "MOD5_USB_~{EN}") (class "Default")
      (node (ref "S10") (pin "4") (pinfunction "Z_4") (pintype "bidirectional"))
      (node (ref "S16") (pin "4") (pinfunction "~{EN}_4") (pintype "bidirectional"))
      (node (ref "U23") (pin "8") (pinfunction "~{OE}_8") (pintype "bidirectional"))
    )
    (net (code "114") (name "MOD5_VCCIO") (class "Default")
      (node (ref "C42") (pin "1") (pinfunction "1_1") (pintype "bidirectional"))
      (node (ref "C48") (pin "1") (pinfunction "1_1") (pintype "bidirectional"))
      (node (ref "C85") (pin "1") (pinfunction "1_1") (pintype "bidirectional"))
      (node (ref "J5") (pin "4") (pinfunction "VCCIO_4") (pintype "bidirectional"))
      (node (ref "R40") (pin "1") (pinfunction "1_1") (pintype "passive"))
      (node (ref "R41") (pin "1") (pinfunction "1_1") (pintype "passive"))
      (node (ref "U11") (pin "8") (pinfunction "VCC_B_8") (pintype "bidirectional"))
      (node (ref "U17") (pin "8") (pinfunction "VCC_B_8") (pintype "bidirectional"))
      (node (ref "U5") (pin "8") (pinfunction "VCC_B_8") (pintype "bidirectional"))
    )
    (net (code "115") (name "MOD6_5V") (class "Default")
      (node (ref "C25") (pin "1") (pinfunction "1_1") (pintype "bidirectional"))
      (node (ref "J6") (pin "2") (pinfunction "5V_2") (pintype "bidirectional"))
      (node (ref "S5") (pin "1") (pinfunction "VLOAD_1") (pintype "bidirectional"))
    )
    (net (code "116") (name "MOD6_5V_METERED") (class "Default")
      (node (ref "C74") (pin "1") (pinfunction "1_1") (pintype "bidirectional"))
      (node (ref "C94") (pin "1") (pinfunction "1_1") (pintype "bidirectional"))
      (node (ref "J4") (pin "11") (pinfunction "VCC_MOD6_11") (pintype "power_in"))
      (node (ref "S17") (pin "2") (pinfunction "IN_2") (pintype "bidirectional"))
      (node (ref "S17") (pin "3") (pinfunction "IN_3") (pintype "bidirectional"))
      (node (ref "S5") (pin "3") (pinfunction "VSUPP_3") (pintype "bidirectional"))
      (node (ref "TP20") (pin "TESTPOINT") (pinfunction "TESTPOINT_TESTPOINT") (pintype "bidirectional"))
    )
    (net (code "117") (name "MOD6_D+_HUB-SW") (class "Default")
      (node (ref "D4") (pin "8") (pinfunction "A_8") (pintype "bidirectional"))
      (node (ref "R61") (pin "2") (pinfunction "2_2") (pintype "passive"))
      (node (ref "R9") (pin "2") (pinfunction "2_2") (pintype "passive"))
      (node (ref "U24") (pin "3") (pinfunction "D+_3") (pintype "bidirectional"))
    )
    (net (code "118") (name "MOD6_D-_HUB-SW") (class "Default")
      (node (ref "D4") (pin "6") (pinfunction "B_6") (pintype "bidirectional"))
      (node (ref "R10") (pin "2") (pinfunction "2_2") (pintype "passive"))
      (node (ref "R62") (pin "2") (pinfunction "2_2") (pintype "passive"))
      (node (ref "U24") (pin "5") (pinfunction "D-_5") (pintype "bidirectional"))
    )
    (net (code "119") (name "MOD6_IN") (class "Default")
      (node (ref "J6") (pin "10") (pinfunction "MOD_IN_10") (pintype "bidirectional"))
      (node (ref "U12") (pin "7") (pinfunction "B1_7") (pintype "bidirectional"))
    )
    (net (code "120") (name "MOD6_ISO_I2C") (class "Default")
      (node (ref "R1014") (pin "2") (pinfunction "2_2") (pintype "passive"))
      (node (ref "R80") (pin "2") (pinfunction "2_2") (pintype "passive"))
      (node (ref "TP1014") (pin "TESTPOINT") (pinfunction "TESTPOINT_TESTPOINT") (pintype "bidirectional"))
      (node (ref "U30") (pin "10") (pinfunction "P1_10") (pintype "bidirectional"))
      (node (ref "U6") (pin "5") (pinfunction "OE_5") (pintype "bidirectional"))
    )
    (net (code "121") (name "MOD6_ISO_POWER") (class "Default")
      (node (ref "R1013") (pin "2") (pinfunction "2_2") (pintype "passive"))
      (node (ref "R79") (pin "2") (pinfunction "2_2") (pintype "passive"))
      (node (ref "S5") (pin "4") (pinfunction "EN_4") (pintype "bidirectional"))
      (node (ref "TP1013") (pin "TESTPOINT") (pinfunction "TESTPOINT_TESTPOINT") (pintype "bidirectional"))
      (node (ref "U30") (pin "9") (pinfunction "P0_9") (pintype "bidirectional"))
    )
    (net (code "122") (name "MOD6_ISO_USB") (class "Default")
      (node (ref "R1015") (pin "2") (pinfunction "2_2") (pintype "passive"))
      (node (ref "R81") (pin "2") (pinfunction "2_2") (pintype "passive"))
      (node (ref "S11") (pin "6") (pinfunction "S_6") (pintype "bidirectional"))
      (node (ref "TP1015") (pin "TESTPOINT") (pinfunction "TESTPOINT_TESTPOINT") (pintype "bidirectional"))
      (node (ref "U30") (pin "11") (pinfunction "P2_11") (pintype "bidirectional"))
    )
    (net (code "123") (name "MOD6_OUT") (class "Default")
      (node (ref "J6") (pin "8") (pinfunction "MOD_OUT_8") (pintype "bidirectional"))
      (node (ref "U18") (pin "7") (pinfunction "B1_7") (pintype "bidirectional"))
    )
    (net (code "124") (name "MOD6_PPS") (class "Default")
      (node (ref "J6") (pin "7") (pinfunction "PPS_7") (pintype "bidirectional"))
      (node (ref "U12") (pin "6") (pinfunction "B2_6") (pintype "bidirectional"))
    )
    (net (code "125") (name "MOD6_SCL") (class "Default")
      (node (ref "J6") (pin "5") (pinfunction "SCL_5") (pintype "bidirectional"))
      (node (ref "R43") (pin "2") (pinfunction "2_2") (pintype "passive"))
      (node (ref "U6") (pin "6") (pinfunction "B1_6") (pintype "bidirectional"))
    )
    (net (code "126") (name "MOD6_SDA") (class "Default")
      (node (ref "J6") (pin "6") (pinfunction "SDA_6") (pintype "bidirectional"))
      (node (ref "R42") (pin "2") (pinfunction "2_2") (pintype "passive"))
      (node (ref "U6") (pin "7") (pinfunction "B0_7") (pintype "bidirectional"))
    )
    (net (code "127") (name "MOD6_USB+") (class "Default")
      (node (ref "J6") (pin "11") (pinfunction "USB_D+_11") (pintype "bidirectional"))
      (node (ref "U24") (pin "1") (pinfunction "D1+_1") (pintype "bidirectional"))
    )
    (net (code "128") (name "MOD6_USB-") (class "Default")
      (node (ref "J6") (pin "12") (pinfunction "USB_D-_12") (pintype "bidirectional"))
      (node (ref "U24") (pin "7") (pinfunction "D1-_7") (pintype "bidirectional"))
    )
    (net (code "129") (name "MOD6_USB_VBUS") (class "Default")
      (node (ref "C101") (pin "1") (pinfunction "1_1") (pintype "passive"))
      (node (ref "C62") (pin "1") (pinfunction "1_1") (pintype "bidirectional"))
      (node (ref "J6") (pin "13") (pinfunction "USB_VBUS_13") (pintype "bidirectional"))
      (node (ref "S17") (pin "6") (pinfunction "OUT_6") (pintype "bidirectional"))
      (node (ref "S17") (pin "7") (pinfunction "OUT_7") (pintype "bidirectional"))
    )
    (net (code "130") (name "MOD6_USB_~{EN}") (class "Default")
      (node (ref "S11") (pin "4") (pinfunction "Z_4") (pintype "bidirectional"))
      (node (ref "S17") (pin "4") (pinfunction "~{EN}_4") (pintype "bidirectional"))
      (node (ref "U24") (pin "8") (pinfunction "~{OE}_8") (pintype "bidirectional"))
    )
    (net (code "131") (name "MOD6_VCCIO") (class "Default")
      (node (ref "C43") (pin "1") (pinfunction "1_1") (pintype "bidirectional"))
      (node (ref "C49") (pin "1") (pinfunction "1_1") (pintype "bidirectional"))
      (node (ref "C86") (pin "1") (pinfunction "1_1") (pintype "bidirectional"))
      (node (ref "J6") (pin "4") (pinfunction "VCCIO_4") (pintype "bidirectional"))
      (node (ref "R42") (pin "1") (pinfunction "1_1") (pintype "passive"))
      (node (ref "R43") (pin "1") (pinfunction "1_1") (pintype "passive"))
      (node (ref "U12") (pin "8") (pinfunction "VCC_B_8") (pintype "bidirectional"))
      (node (ref "U18") (pin "8") (pinfunction "VCC_B_8") (pintype "bidirectional"))
      (node (ref "U6") (pin "8") (pinfunction "VCC_B_8") (pintype "bidirectional"))
    )
    (net (code "132") (name "MOD7_5V") (class "Default")
      (node (ref "C26") (pin "1") (pinfunction "1_1") (pintype "bidirectional"))
      (node (ref "J7") (pin "2") (pinfunction "5V_2") (pintype "bidirectional"))
      (node (ref "S6") (pin "1") (pinfunction "VLOAD_1") (pintype "bidirectional"))
    )
    (net (code "133") (name "MOD7_5V_METERED") (class "Default")
      (node (ref "C75") (pin "1") (pinfunction "1_1") (pintype "bidirectional"))
      (node (ref "C95") (pin "1") (pinfunction "1_1") (pintype "bidirectional"))
      (node (ref "J4") (pin "12") (pinfunction "VCC_MOD7_12") (pintype "power_in"))
      (node (ref "S18") (pin "2") (pinfunction "IN_2") (pintype "bidirectional"))
      (node (ref "S18") (pin "3") (pinfunction "IN_3") (pintype "bidirectional"))
      (node (ref "S6") (pin "3") (pinfunction "VSUPP_3") (pintype "bidirectional"))
      (node (ref "TP21") (pin "TESTPOINT") (pinfunction "TESTPOINT_TESTPOINT") (pintype "bidirectional"))
    )
    (net (code "134") (name "MOD7_D+_HUB-SW") (class "Default")
      (node (ref "D4") (pin "4") (pinfunction "D_4") (pintype "bidirectional"))
      (node (ref "R11") (pin "2") (pinfunction "2_2") (pintype "passive"))
      (node (ref "R63") (pin "2") (pinfunction "2_2") (pintype "passive"))
      (node (ref "U25") (pin "3") (pinfunction "D+_3") (pintype "bidirectional"))
    )
    (net (code "135") (name "MOD7_D-_HUB-SW") (class "Default")
      (node (ref "D4") (pin "2") (pinfunction "C_2") (pintype "bidirectional"))
      (node (ref "R12") (pin "2") (pinfunction "2_2") (pintype "passive"))
      (node (ref "R64") (pin "2") (pinfunction "2_2") (pintype "passive"))
      (node (ref "U25") (pin "5") (pinfunction "D-_5") (pintype "bidirectional"))
    )
    (net (code "136") (name "MOD7_IN") (class "Default")
      (node (ref "J7") (pin "10") (pinfunction "MOD_IN_10") (pintype "bidirectional"))
      (node (ref "U13") (pin "7") (pinfunction "B1_7") (pintype "bidirectional"))
    )
    (net (code "137") (name "MOD7_ISO_I2C") (class "Default")
      (node (ref "LED1017") (pin "A") (pinfunction "ANODE_A") (pintype "bidirectional"))
      (node (ref "R83") (pin "2") (pinfunction "2_2") (pintype "passive"))
      (node (ref "TP1017") (pin "TESTPOINT") (pinfunction "TESTPOINT_TESTPOINT") (pintype "bidirectional"))
      (node (ref "U31") (pin "10") (pinfunction "P1_10") (pintype "bidirectional"))
      (node (ref "U7") (pin "5") (pinfunction "OE_5") (pintype "bidirectional"))
    )
    (net (code "138") (name "MOD7_ISO_POWER") (class "Default")
      (node (ref "LED1016") (pin "A") (pinfunction "ANODE_A") (pintype "bidirectional"))
      (node (ref "R82") (pin "2") (pinfunction "2_2") (pintype "passive"))
      (node (ref "S6") (pin "4") (pinfunction "EN_4") (pintype "bidirectional"))
      (node (ref "TP1016") (pin "TESTPOINT") (pinfunction "TESTPOINT_TESTPOINT") (pintype "bidirectional"))
      (node (ref "U31") (pin "9") (pinfunction "P0_9") (pintype "bidirectional"))
    )
    (net (code "139") (name "MOD7_ISO_USB") (class "Default")
      (node (ref "LED1018") (pin "A") (pinfunction "ANODE_A") (pintype "bidirectional"))
      (node (ref "R84") (pin "2") (pinfunction "2_2") (pintype "passive"))
      (node (ref "S12") (pin "6") (pinfunction "S_6") (pintype "bidirectional"))
      (node (ref "TP1018") (pin "TESTPOINT") (pinfunction "TESTPOINT_TESTPOINT") (pintype "bidirectional"))
      (node (ref "U31") (pin "11") (pinfunction "P2_11") (pintype "bidirectional"))
    )
    (net (code "140") (name "MOD7_OUT") (class "Default")
      (node (ref "J7") (pin "8") (pinfunction "MOD_OUT_8") (pintype "bidirectional"))
      (node (ref "U19") (pin "7") (pinfunction "B1_7") (pintype "bidirectional"))
    )
    (net (code "141") (name "MOD7_PPS") (class "Default")
      (node (ref "J7") (pin "7") (pinfunction "PPS_7") (pintype "bidirectional"))
      (node (ref "U13") (pin "6") (pinfunction "B2_6") (pintype "bidirectional"))
    )
    (net (code "142") (name "MOD7_SCL") (class "Default")
      (node (ref "J7") (pin "5") (pinfunction "SCL_5") (pintype "bidirectional"))
      (node (ref "R45") (pin "2") (pinfunction "2_2") (pintype "passive"))
      (node (ref "U7") (pin "6") (pinfunction "B1_6") (pintype "bidirectional"))
    )
    (net (code "143") (name "MOD7_SDA") (class "Default")
      (node (ref "J7") (pin "6") (pinfunction "SDA_6") (pintype "bidirectional"))
      (node (ref "R44") (pin "2") (pinfunction "2_2") (pintype "passive"))
      (node (ref "U7") (pin "7") (pinfunction "B0_7") (pintype "bidirectional"))
    )
    (net (code "144") (name "MOD7_USB+") (class "Default")
      (node (ref "J7") (pin "11") (pinfunction "USB_D+_11") (pintype "bidirectional"))
      (node (ref "U25") (pin "1") (pinfunction "D1+_1") (pintype "bidirectional"))
    )
    (net (code "145") (name "MOD7_USB-") (class "Default")
      (node (ref "J7") (pin "12") (pinfunction "USB_D-_12") (pintype "bidirectional"))
      (node (ref "U25") (pin "7") (pinfunction "D1-_7") (pintype "bidirectional"))
    )
    (net (code "146") (name "MOD7_USB_VBUS") (class "Default")
      (node (ref "C102") (pin "1") (pinfunction "1_1") (pintype "passive"))
      (node (ref "C63") (pin "1") (pinfunction "1_1") (pintype "bidirectional"))
      (node (ref "J7") (pin "13") (pinfunction "USB_VBUS_13") (pintype "bidirectional"))
      (node (ref "S18") (pin "6") (pinfunction "OUT_6") (pintype "bidirectional"))
      (node (ref "S18") (pin "7") (pinfunction "OUT_7") (pintype "bidirectional"))
    )
    (net (code "147") (name "MOD7_USB_~{EN}") (class "Default")
      (node (ref "S12") (pin "4") (pinfunction "Z_4") (pintype "bidirectional"))
      (node (ref "S18") (pin "4") (pinfunction "~{EN}_4") (pintype "bidirectional"))
      (node (ref "U25") (pin "8") (pinfunction "~{OE}_8") (pintype "bidirectional"))
    )
    (net (code "148") (name "MOD7_VCCIO") (class "Default")
      (node (ref "C44") (pin "1") (pinfunction "1_1") (pintype "bidirectional"))
      (node (ref "C50") (pin "1") (pinfunction "1_1") (pintype "bidirectional"))
      (node (ref "C87") (pin "1") (pinfunction "1_1") (pintype "bidirectional"))
      (node (ref "J7") (pin "4") (pinfunction "VCCIO_4") (pintype "bidirectional"))
      (node (ref "R44") (pin "1") (pinfunction "1_1") (pintype "passive"))
      (node (ref "R45") (pin "1") (pinfunction "1_1") (pintype "passive"))
      (node (ref "U13") (pin "8") (pinfunction "VCC_B_8") (pintype "bidirectional"))
      (node (ref "U19") (pin "8") (pinfunction "VCC_B_8") (pintype "bidirectional"))
      (node (ref "U7") (pin "8") (pinfunction "VCC_B_8") (pintype "bidirectional"))
    )
    (net (code "149") (name "MOD_SCL") (class "Default")
      (node (ref "J3") (pin "24") (pinfunction "MODULES_SCL_24") (pintype "bidirectional"))
      (node (ref "R50") (pin "1") (pinfunction "1_1") (pintype "passive"))
      (node (ref "TP6") (pin "TESTPOINT") (pinfunction "TESTPOINT_TESTPOINT") (pintype "bidirectional"))
      (node (ref "U2") (pin "3") (pinfunction "A1_3") (pintype "bidirectional"))
      (node (ref "U3") (pin "3") (pinfunction "A1_3") (pintype "bidirectional"))
      (node (ref "U4") (pin "3") (pinfunction "A1_3") (pintype "bidirectional"))
      (node (ref "U5") (pin "3") (pinfunction "A1_3") (pintype "bidirectional"))
      (node (ref "U6") (pin "3") (pinfunction "A1_3") (pintype "bidirectional"))
      (node (ref "U7") (pin "3") (pinfunction "A1_3") (pintype "bidirectional"))
    )
    (net (code "150") (name "MOD_SDA") (class "Default")
      (node (ref "J3") (pin "23") (pinfunction "MODULES_SDA_23") (pintype "bidirectional"))
      (node (ref "R49") (pin "1") (pinfunction "1_1") (pintype "passive"))
      (node (ref "TP5") (pin "TESTPOINT") (pinfunction "TESTPOINT_TESTPOINT") (pintype "bidirectional"))
      (node (ref "U2") (pin "2") (pinfunction "A0_2") (pintype "bidirectional"))
      (node (ref "U3") (pin "2") (pinfunction "A0_2") (pintype "bidirectional"))
      (node (ref "U4") (pin "2") (pinfunction "A0_2") (pintype "bidirectional"))
      (node (ref "U5") (pin "2") (pinfunction "A0_2") (pintype "bidirectional"))
      (node (ref "U6") (pin "2") (pinfunction "A0_2") (pintype "bidirectional"))
      (node (ref "U7") (pin "2") (pinfunction "A0_2") (pintype "bidirectional"))
    )
    (net (code "151") (name "Net-(C2-Pad2)") (class "Default")
      (node (ref "C2") (pin "2") (pinfunction "2_2") (pintype "bidirectional"))
      (node (ref "R26") (pin "1") (pinfunction "1_1") (pintype "passive"))
      (node (ref "Y1") (pin "1") (pinfunction "1_1") (pintype "bidirectional"))
    )
    (net (code "152") (name "Net-(LED1001-ANODE)") (class "Default")
      (node (ref "LED1001") (pin "A") (pinfunction "ANODE_A") (pintype "bidirectional"))
      (node (ref "R1001") (pin "1") (pinfunction "1_1") (pintype "passive"))
    )
    (net (code "153") (name "Net-(LED1002-ANODE)") (class "Default")
      (node (ref "LED1002") (pin "A") (pinfunction "ANODE_A") (pintype "bidirectional"))
      (node (ref "R1002") (pin "1") (pinfunction "1_1") (pintype "passive"))
    )
    (net (code "154") (name "Net-(LED1003-ANODE)") (class "Default")
      (node (ref "LED1003") (pin "A") (pinfunction "ANODE_A") (pintype "bidirectional"))
      (node (ref "R1003") (pin "1") (pinfunction "1_1") (pintype "passive"))
    )
    (net (code "155") (name "Net-(LED1004-CATHODE)") (class "Default")
      (node (ref "LED1004") (pin "C") (pinfunction "CATHODE_C") (pintype "bidirectional"))
      (node (ref "R1004") (pin "2") (pinfunction "2_2") (pintype "passive"))
    )
    (net (code "156") (name "Net-(LED1005-CATHODE)") (class "Default")
      (node (ref "LED1005") (pin "C") (pinfunction "CATHODE_C") (pintype "bidirectional"))
      (node (ref "R1005") (pin "2") (pinfunction "2_2") (pintype "passive"))
    )
    (net (code "157") (name "Net-(LED1006-CATHODE)") (class "Default")
      (node (ref "LED1006") (pin "C") (pinfunction "CATHODE_C") (pintype "bidirectional"))
      (node (ref "R1006") (pin "2") (pinfunction "2_2") (pintype "passive"))
    )
    (net (code "158") (name "Net-(LED1007-ANODE)") (class "Default")
      (node (ref "LED1007") (pin "A") (pinfunction "ANODE_A") (pintype "bidirectional"))
      (node (ref "R1007") (pin "1") (pinfunction "1_1") (pintype "passive"))
    )
    (net (code "159") (name "Net-(LED1008-ANODE)") (class "Default")
      (node (ref "LED1008") (pin "A") (pinfunction "ANODE_A") (pintype "bidirectional"))
      (node (ref "R1008") (pin "1") (pinfunction "1_1") (pintype "passive"))
    )
    (net (code "160") (name "Net-(LED1009-ANODE)") (class "Default")
      (node (ref "LED1009") (pin "A") (pinfunction "ANODE_A") (pintype "bidirectional"))
      (node (ref "R1009") (pin "1") (pinfunction "1_1") (pintype "passive"))
    )
    (net (code "161") (name "Net-(LED1010-CATHODE)") (class "Default")
      (node (ref "LED1010") (pin "C") (pinfunction "CATHODE_C") (pintype "bidirectional"))
      (node (ref "R1010") (pin "2") (pinfunction "2_2") (pintype "passive"))
    )
    (net (code "162") (name "Net-(LED1011-CATHODE)") (class "Default")
      (node (ref "LED1011") (pin "C") (pinfunction "CATHODE_C") (pintype "bidirectional"))
      (node (ref "R1011") (pin "2") (pinfunction "2_2") (pintype "passive"))
    )
    (net (code "163") (name "Net-(LED1012-CATHODE)") (class "Default")
      (node (ref "LED1012") (pin "C") (pinfunction "CATHODE_C") (pintype "bidirectional"))
      (node (ref "R1012") (pin "2") (pinfunction "2_2") (pintype "passive"))
    )
    (net (code "164") (name "Net-(LED1013-ANODE)") (class "Default")
      (node (ref "LED1013") (pin "A") (pinfunction "ANODE_A") (pintype "bidirectional"))
      (node (ref "R1013") (pin "1") (pinfunction "1_1") (pintype "passive"))
    )
    (net (code "165") (name "Net-(LED1014-ANODE)") (class "Default")
      (node (ref "LED1014") (pin "A") (pinfunction "ANODE_A") (pintype "bidirectional"))
      (node (ref "R1014") (pin "1") (pinfunction "1_1") (pintype "passive"))
    )
    (net (code "166") (name "Net-(LED1015-ANODE)") (class "Default")
      (node (ref "LED1015") (pin "A") (pinfunction "ANODE_A") (pintype "bidirectional"))
      (node (ref "R1015") (pin "1") (pinfunction "1_1") (pintype "passive"))
    )
    (net (code "167") (name "Net-(LED1016-CATHODE)") (class "Default")
      (node (ref "LED1016") (pin "C") (pinfunction "CATHODE_C") (pintype "bidirectional"))
      (node (ref "R1016") (pin "2") (pinfunction "2_2") (pintype "passive"))
    )
    (net (code "168") (name "Net-(LED1017-CATHODE)") (class "Default")
      (node (ref "LED1017") (pin "C") (pinfunction "CATHODE_C") (pintype "bidirectional"))
      (node (ref "R1017") (pin "2") (pinfunction "2_2") (pintype "passive"))
    )
    (net (code "169") (name "Net-(LED1018-CATHODE)") (class "Default")
      (node (ref "LED1018") (pin "C") (pinfunction "CATHODE_C") (pintype "bidirectional"))
      (node (ref "R1018") (pin "2") (pinfunction "2_2") (pintype "passive"))
    )
    (net (code "170") (name "Net-(U1-DP0PUR)") (class "Default")
      (node (ref "R25") (pin "2") (pinfunction "2_2") (pintype "passive"))
      (node (ref "U1") (pin "2") (pinfunction "DP0PUR_2") (pintype "bidirectional"))
    )
    (net (code "171") (name "Net-(U1-XTAL1)") (class "Default")
      (node (ref "C1") (pin "2") (pinfunction "2_2") (pintype "bidirectional"))
      (node (ref "U1") (pin "45") (pinfunction "XTAL1_45") (pintype "bidirectional"))
      (node (ref "Y1") (pin "3") (pinfunction "2_3") (pintype "bidirectional"))
    )
    (net (code "172") (name "Net-(U1-XTAL2)") (class "Default")
      (node (ref "R26") (pin "2") (pinfunction "2_2") (pintype "passive"))
      (node (ref "U1") (pin "44") (pinfunction "XTAL2_44") (pintype "bidirectional"))
    )
    (net (code "173") (name "Net-(U20-D2+)") (class "Default")
      (node (ref "R13") (pin "1") (pinfunction "1_1") (pintype "passive"))
      (node (ref "U20") (pin "2") (pinfunction "D2+_2") (pintype "bidirectional"))
    )
    (net (code "174") (name "Net-(U20-D2-)") (class "Default")
      (node (ref "R14") (pin "1") (pinfunction "1_1") (pintype "passive"))
      (node (ref "U20") (pin "6") (pinfunction "D2-_6") (pintype "bidirectional"))
    )
    (net (code "175") (name "Net-(U21-D2+)") (class "Default")
      (node (ref "R15") (pin "1") (pinfunction "1_1") (pintype "passive"))
      (node (ref "U21") (pin "2") (pinfunction "D2+_2") (pintype "bidirectional"))
    )
    (net (code "176") (name "Net-(U21-D2-)") (class "Default")
      (node (ref "R16") (pin "1") (pinfunction "1_1") (pintype "passive"))
      (node (ref "U21") (pin "6") (pinfunction "D2-_6") (pintype "bidirectional"))
    )
    (net (code "177") (name "Net-(U22-D2+)") (class "Default")
      (node (ref "R17") (pin "1") (pinfunction "1_1") (pintype "passive"))
      (node (ref "U22") (pin "2") (pinfunction "D2+_2") (pintype "bidirectional"))
    )
    (net (code "178") (name "Net-(U22-D2-)") (class "Default")
      (node (ref "R18") (pin "1") (pinfunction "1_1") (pintype "passive"))
      (node (ref "U22") (pin "6") (pinfunction "D2-_6") (pintype "bidirectional"))
    )
    (net (code "179") (name "Net-(U23-D2+)") (class "Default")
      (node (ref "R19") (pin "1") (pinfunction "1_1") (pintype "passive"))
      (node (ref "U23") (pin "2") (pinfunction "D2+_2") (pintype "bidirectional"))
    )
    (net (code "180") (name "Net-(U23-D2-)") (class "Default")
      (node (ref "R20") (pin "1") (pinfunction "1_1") (pintype "passive"))
      (node (ref "U23") (pin "6") (pinfunction "D2-_6") (pintype "bidirectional"))
    )
    (net (code "181") (name "Net-(U24-D2+)") (class "Default")
      (node (ref "R21") (pin "1") (pinfunction "1_1") (pintype "passive"))
      (node (ref "U24") (pin "2") (pinfunction "D2+_2") (pintype "bidirectional"))
    )
    (net (code "182") (name "Net-(U24-D2-)") (class "Default")
      (node (ref "R22") (pin "1") (pinfunction "1_1") (pintype "passive"))
      (node (ref "U24") (pin "6") (pinfunction "D2-_6") (pintype "bidirectional"))
    )
    (net (code "183") (name "Net-(U25-D2+)") (class "Default")
      (node (ref "R23") (pin "1") (pinfunction "1_1") (pintype "passive"))
      (node (ref "U25") (pin "2") (pinfunction "D2+_2") (pintype "bidirectional"))
    )
    (net (code "184") (name "Net-(U25-D2-)") (class "Default")
      (node (ref "R24") (pin "1") (pinfunction "1_1") (pintype "passive"))
      (node (ref "U25") (pin "6") (pinfunction "D2-_6") (pintype "bidirectional"))
    )
    (net (code "185") (name "Net-(U34-~{WC})") (class "Default")
      (node (ref "SJ1") (pin "2") (pinfunction "2_2") (pintype "passive"))
      (node (ref "U34") (pin "7") (pinfunction "~{WC}_7") (pintype "bidirectional"))
    )
    (net (code "186") (name "PPS") (class "Default")
      (node (ref "J3") (pin "25") (pinfunction "PPS_25") (pintype "bidirectional"))
      (node (ref "TP10") (pin "TESTPOINT") (pinfunction "TESTPOINT_TESTPOINT") (pintype "bidirectional"))
      (node (ref "U10") (pin "3") (pinfunction "A2_3") (pintype "bidirectional"))
      (node (ref "U11") (pin "3") (pinfunction "A2_3") (pintype "bidirectional"))
      (node (ref "U12") (pin "3") (pinfunction "A2_3") (pintype "bidirectional"))
      (node (ref "U13") (pin "3") (pinfunction "A2_3") (pintype "bidirectional"))
      (node (ref "U8") (pin "3") (pinfunction "A2_3") (pintype "bidirectional"))
      (node (ref "U9") (pin "3") (pinfunction "A2_3") (pintype "bidirectional"))
    )
    (net (code "187") (name "SMBCLK") (class "Default")
      (node (ref "J3") (pin "5") (pinfunction "SMBCLK_5") (pintype "bidirectional"))
      (node (ref "J4") (pin "5") (pinfunction "SMBCLK_5") (pintype "open_collector"))
      (node (ref "R47") (pin "1") (pinfunction "1_1") (pintype "passive"))
      (node (ref "TP2") (pin "TESTPOINT") (pinfunction "TESTPOINT_TESTPOINT") (pintype "bidirectional"))
      (node (ref "U26") (pin "19") (pinfunction "SCL_19") (pintype "bidirectional"))
      (node (ref "U27") (pin "19") (pinfunction "SCL_19") (pintype "bidirectional"))
      (node (ref "U28") (pin "19") (pinfunction "SCL_19") (pintype "bidirectional"))
      (node (ref "U29") (pin "19") (pinfunction "SCL_19") (pintype "bidirectional"))
      (node (ref "U30") (pin "19") (pinfunction "SCL_19") (pintype "bidirectional"))
      (node (ref "U31") (pin "19") (pinfunction "SCL_19") (pintype "bidirectional"))
      (node (ref "U32") (pin "19") (pinfunction "SCL_19") (pintype "bidirectional"))
      (node (ref "U34") (pin "6") (pinfunction "SCL_6") (pintype "bidirectional"))
    )
    (net (code "188") (name "SMBDATA") (class "Default")
      (node (ref "J3") (pin "3") (pinfunction "SMBDATA_3") (pintype "bidirectional"))
      (node (ref "J4") (pin "3") (pinfunction "SMBDATA_3") (pintype "open_collector"))
      (node (ref "R46") (pin "1") (pinfunction "1_1") (pintype "passive"))
      (node (ref "TP1") (pin "TESTPOINT") (pinfunction "TESTPOINT_TESTPOINT") (pintype "bidirectional"))
      (node (ref "U26") (pin "20") (pinfunction "SDA_20") (pintype "bidirectional"))
      (node (ref "U27") (pin "20") (pinfunction "SDA_20") (pintype "bidirectional"))
      (node (ref "U28") (pin "20") (pinfunction "SDA_20") (pintype "bidirectional"))
      (node (ref "U29") (pin "20") (pinfunction "SDA_20") (pintype "bidirectional"))
      (node (ref "U30") (pin "20") (pinfunction "SDA_20") (pintype "bidirectional"))
      (node (ref "U31") (pin "20") (pinfunction "SDA_20") (pintype "bidirectional"))
      (node (ref "U32") (pin "20") (pinfunction "SDA_20") (pintype "bidirectional"))
      (node (ref "U34") (pin "5") (pinfunction "SDA_5") (pintype "bidirectional"))
    )
    (net (code "189") (name "USB_SUSPEND_STATUS") (class "Default")
      (node (ref "TP31") (pin "TESTPOINT") (pinfunction "TESTPOINT_TESTPOINT") (pintype "bidirectional"))
      (node (ref "U1") (pin "1") (pinfunction "SUSPND_1") (pintype "bidirectional"))
    )
    (net (code "190") (name "VBATT+") (class "Default")
      (node (ref "J4") (pin "17") (pinfunction "VBATT+_17") (pintype "power_in"))
      (node (ref "J9") (pin "1") (pinfunction "1_1") (pintype "bidirectional"))
      (node (ref "TP14") (pin "TESTPOINT") (pinfunction "TESTPOINT_TESTPOINT") (pintype "bidirectional"))
    )
    (net (code "191") (name "VBATT-") (class "Default")
      (node (ref "J4") (pin "18") (pinfunction "VBATT-_18") (pintype "power_in"))
      (node (ref "J9") (pin "2") (pinfunction "2_2") (pintype "bidirectional"))
      (node (ref "TP15") (pin "TESTPOINT") (pinfunction "TESTPOINT_TESTPOINT") (pintype "bidirectional"))
    )
    (net (code "192") (name "VCC_BACKPLANE") (class "Default")
      (node (ref "C15") (pin "1") (pinfunction "1_1") (pintype "bidirectional"))
      (node (ref "C16") (pin "1") (pinfunction "1_1") (pintype "bidirectional"))
      (node (ref "C17") (pin "1") (pinfunction "1_1") (pintype "bidirectional"))
      (node (ref "C18") (pin "1") (pinfunction "1_1") (pintype "bidirectional"))
      (node (ref "C19") (pin "1") (pinfunction "1_1") (pintype "bidirectional"))
      (node (ref "C20") (pin "1") (pinfunction "1_1") (pintype "bidirectional"))
      (node (ref "C27") (pin "1") (pinfunction "1_1") (pintype "bidirectional"))
      (node (ref "C28") (pin "1") (pinfunction "1_1") (pintype "bidirectional"))
      (node (ref "C29") (pin "1") (pinfunction "1_1") (pintype "bidirectional"))
      (node (ref "C30") (pin "1") (pinfunction "1_1") (pintype "bidirectional"))
      (node (ref "C31") (pin "1") (pinfunction "1_1") (pintype "bidirectional"))
      (node (ref "C32") (pin "1") (pinfunction "1_1") (pintype "bidirectional"))
      (node (ref "C33") (pin "1") (pinfunction "1_1") (pintype "bidirectional"))
      (node (ref "C34") (pin "1") (pinfunction "1_1") (pintype "bidirectional"))
      (node (ref "C35") (pin "1") (pinfunction "1_1") (pintype "bidirectional"))
      (node (ref "C36") (pin "1") (pinfunction "1_1") (pintype "bidirectional"))
      (node (ref "C37") (pin "1") (pinfunction "1_1") (pintype "bidirectional"))
      (node (ref "C38") (pin "1") (pinfunction "1_1") (pintype "bidirectional"))
      (node (ref "C51") (pin "2") (pinfunction "2_2") (pintype "bidirectional"))
      (node (ref "C52") (pin "1") (pinfunction "1_1") (pintype "bidirectional"))
      (node (ref "C53") (pin "1") (pinfunction "1_1") (pintype "bidirectional"))
      (node (ref "C54") (pin "1") (pinfunction "1_1") (pintype "bidirectional"))
      (node (ref "C55") (pin "1") (pinfunction "1_1") (pintype "bidirectional"))
      (node (ref "C56") (pin "1") (pinfunction "1_1") (pintype "bidirectional"))
      (node (ref "C57") (pin "1") (pinfunction "1_1") (pintype "bidirectional"))
      (node (ref "C64") (pin "1") (pinfunction "1_1") (pintype "bidirectional"))
      (node (ref "C65") (pin "1") (pinfunction "1_1") (pintype "bidirectional"))
      (node (ref "C66") (pin "1") (pinfunction "1_1") (pintype "bidirectional"))
      (node (ref "C67") (pin "1") (pinfunction "1_1") (pintype "bidirectional"))
      (node (ref "C68") (pin "1") (pinfunction "1_1") (pintype "bidirectional"))
      (node (ref "C69") (pin "1") (pinfunction "1_1") (pintype "bidirectional"))
      (node (ref "C76") (pin "2") (pinfunction "2_2") (pintype "bidirectional"))
      (node (ref "C77") (pin "2") (pinfunction "2_2") (pintype "bidirectional"))
      (node (ref "C78") (pin "2") (pinfunction "2_2") (pintype "bidirectional"))
      (node (ref "C79") (pin "2") (pinfunction "2_2") (pintype "bidirectional"))
      (node (ref "C80") (pin "2") (pinfunction "2_2") (pintype "bidirectional"))
      (node (ref "C81") (pin "2") (pinfunction "2_2") (pintype "bidirectional"))
      (node (ref "C88") (pin "1") (pinfunction "1_1") (pintype "bidirectional"))
      (node (ref "C89") (pin "1") (pinfunction "1_1") (pintype "bidirectional"))
      (node (ref "C96") (pin "2") (pinfunction "2_2") (pintype "bidirectional"))
      (node (ref "J4") (pin "13") (pinfunction "VCC_BACKPLANE_13") (pintype "power_in"))
      (node (ref "R27") (pin "1") (pinfunction "1_1") (pintype "passive"))
      (node (ref "R28") (pin "2") (pinfunction "2_2") (pintype "passive"))
      (node (ref "R29") (pin "2") (pinfunction "2_2") (pintype "passive"))
      (node (ref "R30") (pin "2") (pinfunction "2_2") (pintype "passive"))
      (node (ref "R31") (pin "2") (pinfunction "2_2") (pintype "passive"))
      (node (ref "R32") (pin "2") (pinfunction "2_2") (pintype "passive"))
      (node (ref "R33") (pin "2") (pinfunction "2_2") (pintype "passive"))
      (node (ref "R46") (pin "2") (pinfunction "2_2") (pintype "passive"))
      (node (ref "R47") (pin "2") (pinfunction "2_2") (pintype "passive"))
      (node (ref "R48") (pin "2") (pinfunction "2_2") (pintype "passive"))
      (node (ref "R49") (pin "2") (pinfunction "2_2") (pintype "passive"))
      (node (ref "R50") (pin "2") (pinfunction "2_2") (pintype "passive"))
      (node (ref "R51") (pin "2") (pinfunction "2_2") (pintype "passive"))
      (node (ref "R52") (pin "2") (pinfunction "2_2") (pintype "passive"))
      (node (ref "S10") (pin "3") (pinfunction "I0_3") (pintype "bidirectional"))
      (node (ref "S10") (pin "5") (pinfunction "VCC_5") (pintype "bidirectional"))
      (node (ref "S11") (pin "3") (pinfunction "I0_3") (pintype "bidirectional"))
      (node (ref "S11") (pin "5") (pinfunction "VCC_5") (pintype "bidirectional"))
      (node (ref "S12") (pin "3") (pinfunction "I0_3") (pintype "bidirectional"))
      (node (ref "S12") (pin "5") (pinfunction "VCC_5") (pintype "bidirectional"))
      (node (ref "S7") (pin "3") (pinfunction "I0_3") (pintype "bidirectional"))
      (node (ref "S7") (pin "5") (pinfunction "VCC_5") (pintype "bidirectional"))
      (node (ref "S8") (pin "3") (pinfunction "I0_3") (pintype "bidirectional"))
      (node (ref "S8") (pin "5") (pinfunction "VCC_5") (pintype "bidirectional"))
      (node (ref "S9") (pin "3") (pinfunction "I0_3") (pintype "bidirectional"))
      (node (ref "S9") (pin "5") (pinfunction "VCC_5") (pintype "bidirectional"))
      (node (ref "SJ1") (pin "1") (pinfunction "1_1") (pintype "passive"))
      (node (ref "TP24") (pin "TESTPOINT") (pinfunction "TESTPOINT_TESTPOINT") (pintype "bidirectional"))
      (node (ref "TP8") (pin "TESTPOINT") (pinfunction "TESTPOINT_TESTPOINT") (pintype "bidirectional"))
      (node (ref "U1") (pin "46") (pinfunction "VCC_46") (pintype "bidirectional"))
      (node (ref "U1") (pin "47") (pinfunction "~{EXTMEM}_47") (pintype "bidirectional"))
      (node (ref "U1") (pin "8") (pinfunction "EEDATA/~{GANGED}_8") (pintype "bidirectional"))
      (node (ref "U1") (pin "9") (pinfunction "VCC_9") (pintype "bidirectional"))
      (node (ref "U10") (pin "1") (pinfunction "VCC_A_1") (pintype "bidirectional"))
      (node (ref "U10") (pin "5") (pinfunction "DIR_5") (pintype "bidirectional"))
      (node (ref "U11") (pin "1") (pinfunction "VCC_A_1") (pintype "bidirectional"))
      (node (ref "U11") (pin "5") (pinfunction "DIR_5") (pintype "bidirectional"))
      (node (ref "U12") (pin "1") (pinfunction "VCC_A_1") (pintype "bidirectional"))
      (node (ref "U12") (pin "5") (pinfunction "DIR_5") (pintype "bidirectional"))
      (node (ref "U13") (pin "1") (pinfunction "VCC_A_1") (pintype "bidirectional"))
      (node (ref "U13") (pin "5") (pinfunction "DIR_5") (pintype "bidirectional"))
      (node (ref "U14") (pin "1") (pinfunction "VCC_A_1") (pintype "bidirectional"))
      (node (ref "U15") (pin "1") (pinfunction "VCC_A_1") (pintype "bidirectional"))
      (node (ref "U16") (pin "1") (pinfunction "VCC_A_1") (pintype "bidirectional"))
      (node (ref "U17") (pin "1") (pinfunction "VCC_A_1") (pintype "bidirectional"))
      (node (ref "U18") (pin "1") (pinfunction "VCC_A_1") (pintype "bidirectional"))
      (node (ref "U19") (pin "1") (pinfunction "VCC_A_1") (pintype "bidirectional"))
      (node (ref "U2") (pin "1") (pinfunction "VCC_A_1") (pintype "bidirectional"))
      (node (ref "U20") (pin "9") (pinfunction "VCC_9") (pintype "bidirectional"))
      (node (ref "U21") (pin "9") (pinfunction "VCC_9") (pintype "bidirectional"))
      (node (ref "U22") (pin "9") (pinfunction "VCC_9") (pintype "bidirectional"))
      (node (ref "U23") (pin "9") (pinfunction "VCC_9") (pintype "bidirectional"))
      (node (ref "U24") (pin "9") (pinfunction "VCC_9") (pintype "bidirectional"))
      (node (ref "U25") (pin "9") (pinfunction "VCC_9") (pintype "bidirectional"))
      (node (ref "U26") (pin "18") (pinfunction "VCC_18") (pintype "bidirectional"))
      (node (ref "U27") (pin "18") (pinfunction "VCC_18") (pintype "bidirectional"))
      (node (ref "U27") (pin "3") (pinfunction "A0_3") (pintype "bidirectional"))
      (node (ref "U28") (pin "18") (pinfunction "VCC_18") (pintype "bidirectional"))
      (node (ref "U28") (pin "2") (pinfunction "A1_2") (pintype "bidirectional"))
      (node (ref "U29") (pin "1") (pinfunction "A2_1") (pintype "bidirectional"))
      (node (ref "U29") (pin "18") (pinfunction "VCC_18") (pintype "bidirectional"))
      (node (ref "U29") (pin "3") (pinfunction "A0_3") (pintype "bidirectional"))
      (node (ref "U3") (pin "1") (pinfunction "VCC_A_1") (pintype "bidirectional"))
      (node (ref "U30") (pin "1") (pinfunction "A2_1") (pintype "bidirectional"))
      (node (ref "U30") (pin "18") (pinfunction "VCC_18") (pintype "bidirectional"))
      (node (ref "U30") (pin "2") (pinfunction "A1_2") (pintype "bidirectional"))
      (node (ref "U31") (pin "1") (pinfunction "A2_1") (pintype "bidirectional"))
      (node (ref "U31") (pin "18") (pinfunction "VCC_18") (pintype "bidirectional"))
      (node (ref "U31") (pin "2") (pinfunction "A1_2") (pintype "bidirectional"))
      (node (ref "U31") (pin "3") (pinfunction "A0_3") (pintype "bidirectional"))
      (node (ref "U32") (pin "18") (pinfunction "VCC_18") (pintype "bidirectional"))
      (node (ref "U32") (pin "2") (pinfunction "A1_2") (pintype "bidirectional"))
      (node (ref "U32") (pin "3") (pinfunction "A0_3") (pintype "bidirectional"))
      (node (ref "U33") (pin "2") (pinfunction "VCC_2") (pintype "bidirectional"))
      (node (ref "U34") (pin "1") (pinfunction "E0_1") (pintype "bidirectional"))
      (node (ref "U34") (pin "8") (pinfunction "VCC_8") (pintype "bidirectional"))
      (node (ref "U4") (pin "1") (pinfunction "VCC_A_1") (pintype "bidirectional"))
      (node (ref "U5") (pin "1") (pinfunction "VCC_A_1") (pintype "bidirectional"))
      (node (ref "U6") (pin "1") (pinfunction "VCC_A_1") (pintype "bidirectional"))
      (node (ref "U7") (pin "1") (pinfunction "VCC_A_1") (pintype "bidirectional"))
      (node (ref "U8") (pin "1") (pinfunction "VCC_A_1") (pintype "bidirectional"))
      (node (ref "U8") (pin "5") (pinfunction "DIR_5") (pintype "bidirectional"))
      (node (ref "U9") (pin "1") (pinfunction "VCC_A_1") (pintype "bidirectional"))
      (node (ref "U9") (pin "5") (pinfunction "DIR_5") (pintype "bidirectional"))
    )
    (net (code "193") (name "VCC_CONTROLLER") (class "Default")
      (node (ref "J3") (pin "2") (pinfunction "VCC_CONTROLLER_2") (pintype "bidirectional"))
      (node (ref "J4") (pin "2") (pinfunction "VCC_CONTROLLER_2") (pintype "power_in"))
      (node (ref "TP22") (pin "TESTPOINT") (pinfunction "TESTPOINT_TESTPOINT") (pintype "bidirectional"))
    )
    (net (code "194") (name "VCC_LINUX") (class "Default")
      (node (ref "J3") (pin "4") (pinfunction "VCC_LINUX_4") (pintype "bidirectional"))
      (node (ref "J4") (pin "4") (pinfunction "VCC_LINUX_4") (pintype "power_in"))
      (node (ref "TP23") (pin "TESTPOINT") (pinfunction "TESTPOINT_TESTPOINT") (pintype "bidirectional"))
    )
    (net (code "195") (name "VSOL+") (class "Default")
      (node (ref "J4") (pin "19") (pinfunction "VSOL+_19") (pintype "power_in"))
      (node (ref "J8") (pin "1") (pinfunction "1_1") (pintype "bidirectional"))
      (node (ref "TP12") (pin "TESTPOINT") (pinfunction "TESTPOINT_TESTPOINT") (pintype "bidirectional"))
    )
    (net (code "196") (name "VSOL-") (class "Default")
      (node (ref "J4") (pin "20") (pinfunction "VSOL-_20") (pintype "power_in"))
      (node (ref "J8") (pin "2") (pinfunction "2_2") (pintype "bidirectional"))
      (node (ref "TP13") (pin "TESTPOINT") (pinfunction "TESTPOINT_TESTPOINT") (pintype "bidirectional"))
    )
    (net (code "197") (name "unconnected-(D2-C-Pad2)") (class "Default")
      (node (ref "D2") (pin "2") (pinfunction "C_2") (pintype "bidirectional"))
    )
    (net (code "198") (name "unconnected-(D2-D-Pad4)") (class "Default")
      (node (ref "D2") (pin "4") (pinfunction "D_4") (pintype "bidirectional"))
    )
    (net (code "199") (name "unconnected-(D3-A-Pad8)") (class "Default")
      (node (ref "D3") (pin "8") (pinfunction "A_8") (pintype "bidirectional"))
    )
    (net (code "200") (name "unconnected-(D3-B-Pad6)") (class "Default")
      (node (ref "D3") (pin "6") (pinfunction "B_6") (pintype "bidirectional"))
    )
    (net (code "201") (name "unconnected-(U1-EECLK-Pad7)") (class "Default")
      (node (ref "U1") (pin "7") (pinfunction "EECLK_7") (pintype "bidirectional"))
    )
    (net (code "202") (name "unconnected-(U14-A2-Pad3)") (class "Default")
      (node (ref "U14") (pin "3") (pinfunction "A2_3") (pintype "bidirectional"))
    )
    (net (code "203") (name "unconnected-(U14-B2-Pad6)") (class "Default")
      (node (ref "U14") (pin "6") (pinfunction "B2_6") (pintype "bidirectional"))
    )
    (net (code "204") (name "unconnected-(U15-A2-Pad3)") (class "Default")
      (node (ref "U15") (pin "3") (pinfunction "A2_3") (pintype "bidirectional"))
    )
    (net (code "205") (name "unconnected-(U15-B2-Pad6)") (class "Default")
      (node (ref "U15") (pin "6") (pinfunction "B2_6") (pintype "bidirectional"))
    )
    (net (code "206") (name "unconnected-(U16-A2-Pad3)") (class "Default")
      (node (ref "U16") (pin "3") (pinfunction "A2_3") (pintype "bidirectional"))
    )
    (net (code "207") (name "unconnected-(U16-B2-Pad6)") (class "Default")
      (node (ref "U16") (pin "6") (pinfunction "B2_6") (pintype "bidirectional"))
    )
    (net (code "208") (name "unconnected-(U17-A2-Pad3)") (class "Default")
      (node (ref "U17") (pin "3") (pinfunction "A2_3") (pintype "bidirectional"))
    )
    (net (code "209") (name "unconnected-(U17-B2-Pad6)") (class "Default")
      (node (ref "U17") (pin "6") (pinfunction "B2_6") (pintype "bidirectional"))
    )
    (net (code "210") (name "unconnected-(U18-A2-Pad3)") (class "Default")
      (node (ref "U18") (pin "3") (pinfunction "A2_3") (pintype "bidirectional"))
    )
    (net (code "211") (name "unconnected-(U18-B2-Pad6)") (class "Default")
      (node (ref "U18") (pin "6") (pinfunction "B2_6") (pintype "bidirectional"))
    )
    (net (code "212") (name "unconnected-(U18-DIR-Pad5)") (class "Default")
      (node (ref "U18") (pin "5") (pinfunction "DIR_5") (pintype "bidirectional"))
    )
    (net (code "213") (name "unconnected-(U19-A2-Pad3)") (class "Default")
      (node (ref "U19") (pin "3") (pinfunction "A2_3") (pintype "bidirectional"))
    )
    (net (code "214") (name "unconnected-(U19-B2-Pad6)") (class "Default")
      (node (ref "U19") (pin "6") (pinfunction "B2_6") (pintype "bidirectional"))
    )
    (net (code "215") (name "unconnected-(U26-INT-Pad7)") (class "Default")
      (node (ref "U26") (pin "7") (pinfunction "INT_7") (pintype "bidirectional"))
    )
    (net (code "216") (name "unconnected-(U26-P3-Pad12)") (class "Default")
      (node (ref "U26") (pin "12") (pinfunction "P3_12") (pintype "bidirectional"))
    )
    (net (code "217") (name "unconnected-(U26-P4-Pad13)") (class "Default")
      (node (ref "U26") (pin "13") (pinfunction "P4_13") (pintype "bidirectional"))
    )
    (net (code "218") (name "unconnected-(U26-P5-Pad14)") (class "Default")
      (node (ref "U26") (pin "14") (pinfunction "P5_14") (pintype "bidirectional"))
    )
    (net (code "219") (name "unconnected-(U26-P6-Pad15)") (class "Default")
      (node (ref "U26") (pin "15") (pinfunction "P6_15") (pintype "bidirectional"))
    )
    (net (code "220") (name "unconnected-(U26-P7-Pad16)") (class "Default")
      (node (ref "U26") (pin "16") (pinfunction "P7_16") (pintype "bidirectional"))
    )
    (net (code "221") (name "unconnected-(U27-INT-Pad7)") (class "Default")
      (node (ref "U27") (pin "7") (pinfunction "INT_7") (pintype "bidirectional"))
    )
    (net (code "222") (name "unconnected-(U27-P3-Pad12)") (class "Default")
      (node (ref "U27") (pin "12") (pinfunction "P3_12") (pintype "bidirectional"))
    )
    (net (code "223") (name "unconnected-(U27-P4-Pad13)") (class "Default")
      (node (ref "U27") (pin "13") (pinfunction "P4_13") (pintype "bidirectional"))
    )
    (net (code "224") (name "unconnected-(U27-P5-Pad14)") (class "Default")
      (node (ref "U27") (pin "14") (pinfunction "P5_14") (pintype "bidirectional"))
    )
    (net (code "225") (name "unconnected-(U27-P6-Pad15)") (class "Default")
      (node (ref "U27") (pin "15") (pinfunction "P6_15") (pintype "bidirectional"))
    )
    (net (code "226") (name "unconnected-(U27-P7-Pad16)") (class "Default")
      (node (ref "U27") (pin "16") (pinfunction "P7_16") (pintype "bidirectional"))
    )
    (net (code "227") (name "unconnected-(U28-INT-Pad7)") (class "Default")
      (node (ref "U28") (pin "7") (pinfunction "INT_7") (pintype "bidirectional"))
    )
    (net (code "228") (name "unconnected-(U28-P3-Pad12)") (class "Default")
      (node (ref "U28") (pin "12") (pinfunction "P3_12") (pintype "bidirectional"))
    )
    (net (code "229") (name "unconnected-(U28-P4-Pad13)") (class "Default")
      (node (ref "U28") (pin "13") (pinfunction "P4_13") (pintype "bidirectional"))
    )
    (net (code "230") (name "unconnected-(U28-P5-Pad14)") (class "Default")
      (node (ref "U28") (pin "14") (pinfunction "P5_14") (pintype "bidirectional"))
    )
    (net (code "231") (name "unconnected-(U28-P6-Pad15)") (class "Default")
      (node (ref "U28") (pin "15") (pinfunction "P6_15") (pintype "bidirectional"))
    )
    (net (code "232") (name "unconnected-(U28-P7-Pad16)") (class "Default")
      (node (ref "U28") (pin "16") (pinfunction "P7_16") (pintype "bidirectional"))
    )
    (net (code "233") (name "unconnected-(U29-INT-Pad7)") (class "Default")
      (node (ref "U29") (pin "7") (pinfunction "INT_7") (pintype "bidirectional"))
    )
    (net (code "234") (name "unconnected-(U29-P3-Pad12)") (class "Default")
      (node (ref "U29") (pin "12") (pinfunction "P3_12") (pintype "bidirectional"))
    )
    (net (code "235") (name "unconnected-(U29-P4-Pad13)") (class "Default")
      (node (ref "U29") (pin "13") (pinfunction "P4_13") (pintype "bidirectional"))
    )
    (net (code "236") (name "unconnected-(U29-P5-Pad14)") (class "Default")
      (node (ref "U29") (pin "14") (pinfunction "P5_14") (pintype "bidirectional"))
    )
    (net (code "237") (name "unconnected-(U29-P6-Pad15)") (class "Default")
      (node (ref "U29") (pin "15") (pinfunction "P6_15") (pintype "bidirectional"))
    )
    (net (code "238") (name "unconnected-(U29-P7-Pad16)") (class "Default")
      (node (ref "U29") (pin "16") (pinfunction "P7_16") (pintype "bidirectional"))
    )
    (net (code "239") (name "unconnected-(U30-INT-Pad7)") (class "Default")
      (node (ref "U30") (pin "7") (pinfunction "INT_7") (pintype "bidirectional"))
    )
    (net (code "240") (name "unconnected-(U30-P3-Pad12)") (class "Default")
      (node (ref "U30") (pin "12") (pinfunction "P3_12") (pintype "bidirectional"))
    )
    (net (code "241") (name "unconnected-(U30-P4-Pad13)") (class "Default")
      (node (ref "U30") (pin "13") (pinfunction "P4_13") (pintype "bidirectional"))
    )
    (net (code "242") (name "unconnected-(U30-P5-Pad14)") (class "Default")
      (node (ref "U30") (pin "14") (pinfunction "P5_14") (pintype "bidirectional"))
    )
    (net (code "243") (name "unconnected-(U30-P6-Pad15)") (class "Default")
      (node (ref "U30") (pin "15") (pinfunction "P6_15") (pintype "bidirectional"))
    )
    (net (code "244") (name "unconnected-(U30-P7-Pad16)") (class "Default")
      (node (ref "U30") (pin "16") (pinfunction "P7_16") (pintype "bidirectional"))
    )
    (net (code "245") (name "unconnected-(U31-INT-Pad7)") (class "Default")
      (node (ref "U31") (pin "7") (pinfunction "INT_7") (pintype "bidirectional"))
    )
    (net (code "246") (name "unconnected-(U31-P3-Pad12)") (class "Default")
      (node (ref "U31") (pin "12") (pinfunction "P3_12") (pintype "bidirectional"))
    )
    (net (code "247") (name "unconnected-(U31-P4-Pad13)") (class "Default")
      (node (ref "U31") (pin "13") (pinfunction "P4_13") (pintype "bidirectional"))
    )
    (net (code "248") (name "unconnected-(U31-P5-Pad14)") (class "Default")
      (node (ref "U31") (pin "14") (pinfunction "P5_14") (pintype "bidirectional"))
    )
    (net (code "249") (name "unconnected-(U31-P6-Pad15)") (class "Default")
      (node (ref "U31") (pin "15") (pinfunction "P6_15") (pintype "bidirectional"))
    )
    (net (code "250") (name "unconnected-(U31-P7-Pad16)") (class "Default")
      (node (ref "U31") (pin "16") (pinfunction "P7_16") (pintype "bidirectional"))
    )
    (net (code "251") (name "unconnected-(U32-INT-Pad7)") (class "Default")
      (node (ref "U32") (pin "7") (pinfunction "INT_7") (pintype "bidirectional"))
    )
    (net (code "252") (name "~{BACKPLANE_RESET}") (class "Default")
      (node (ref "J3") (pin "22") (pinfunction "~{BACKPLANE_RESET}_22") (pintype "bidirectional"))
      (node (ref "R27") (pin "2") (pinfunction "2_2") (pintype "passive"))
      (node (ref "TP9") (pin "TESTPOINT") (pinfunction "TESTPOINT_TESTPOINT") (pintype "bidirectional"))
      (node (ref "U26") (pin "4") (pinfunction "~{RESET}_4") (pintype "bidirectional"))
      (node (ref "U27") (pin "4") (pinfunction "~{RESET}_4") (pintype "bidirectional"))
      (node (ref "U28") (pin "4") (pinfunction "~{RESET}_4") (pintype "bidirectional"))
      (node (ref "U29") (pin "4") (pinfunction "~{RESET}_4") (pintype "bidirectional"))
      (node (ref "U30") (pin "4") (pinfunction "~{RESET}_4") (pintype "bidirectional"))
      (node (ref "U31") (pin "4") (pinfunction "~{RESET}_4") (pintype "bidirectional"))
      (node (ref "U32") (pin "4") (pinfunction "~{RESET}_4") (pintype "bidirectional"))
    )
    (net (code "253") (name "~{SMBALERT}") (class "Default")
      (node (ref "J3") (pin "6") (pinfunction "~{SMBALERT}_6") (pintype "bidirectional"))
      (node (ref "J4") (pin "6") (pinfunction "~{SMBALERT}_6") (pintype "bidirectional"))
      (node (ref "R48") (pin "1") (pinfunction "1_1") (pintype "passive"))
      (node (ref "TP3") (pin "TESTPOINT") (pinfunction "TESTPOINT_TESTPOINT") (pintype "bidirectional"))
    )
    (net (code "254") (name "~{USB_RESET}") (class "Default")
      (node (ref "R52") (pin "1") (pinfunction "1_1") (pintype "passive"))
      (node (ref "U1") (pin "6") (pinfunction "~{RESET}_6") (pintype "bidirectional"))
      (node (ref "U32") (pin "9") (pinfunction "P0_9") (pintype "bidirectional"))
      (node (ref "U33") (pin "1") (pinfunction "~{RST}_1") (pintype "bidirectional"))
    )
    (net (code "255") (name "~{WATCHDOG}") (class "Default")
      (node (ref "J3") (pin "7") (pinfunction "~{WATCHDOG}_7") (pintype "bidirectional"))
      (node (ref "J4") (pin "16") (pinfunction "WDI_16") (pintype "power_in"))
    )
  )
)
